# Hammer.net
KiCad netlist of a schematic drawn in Altium Designer
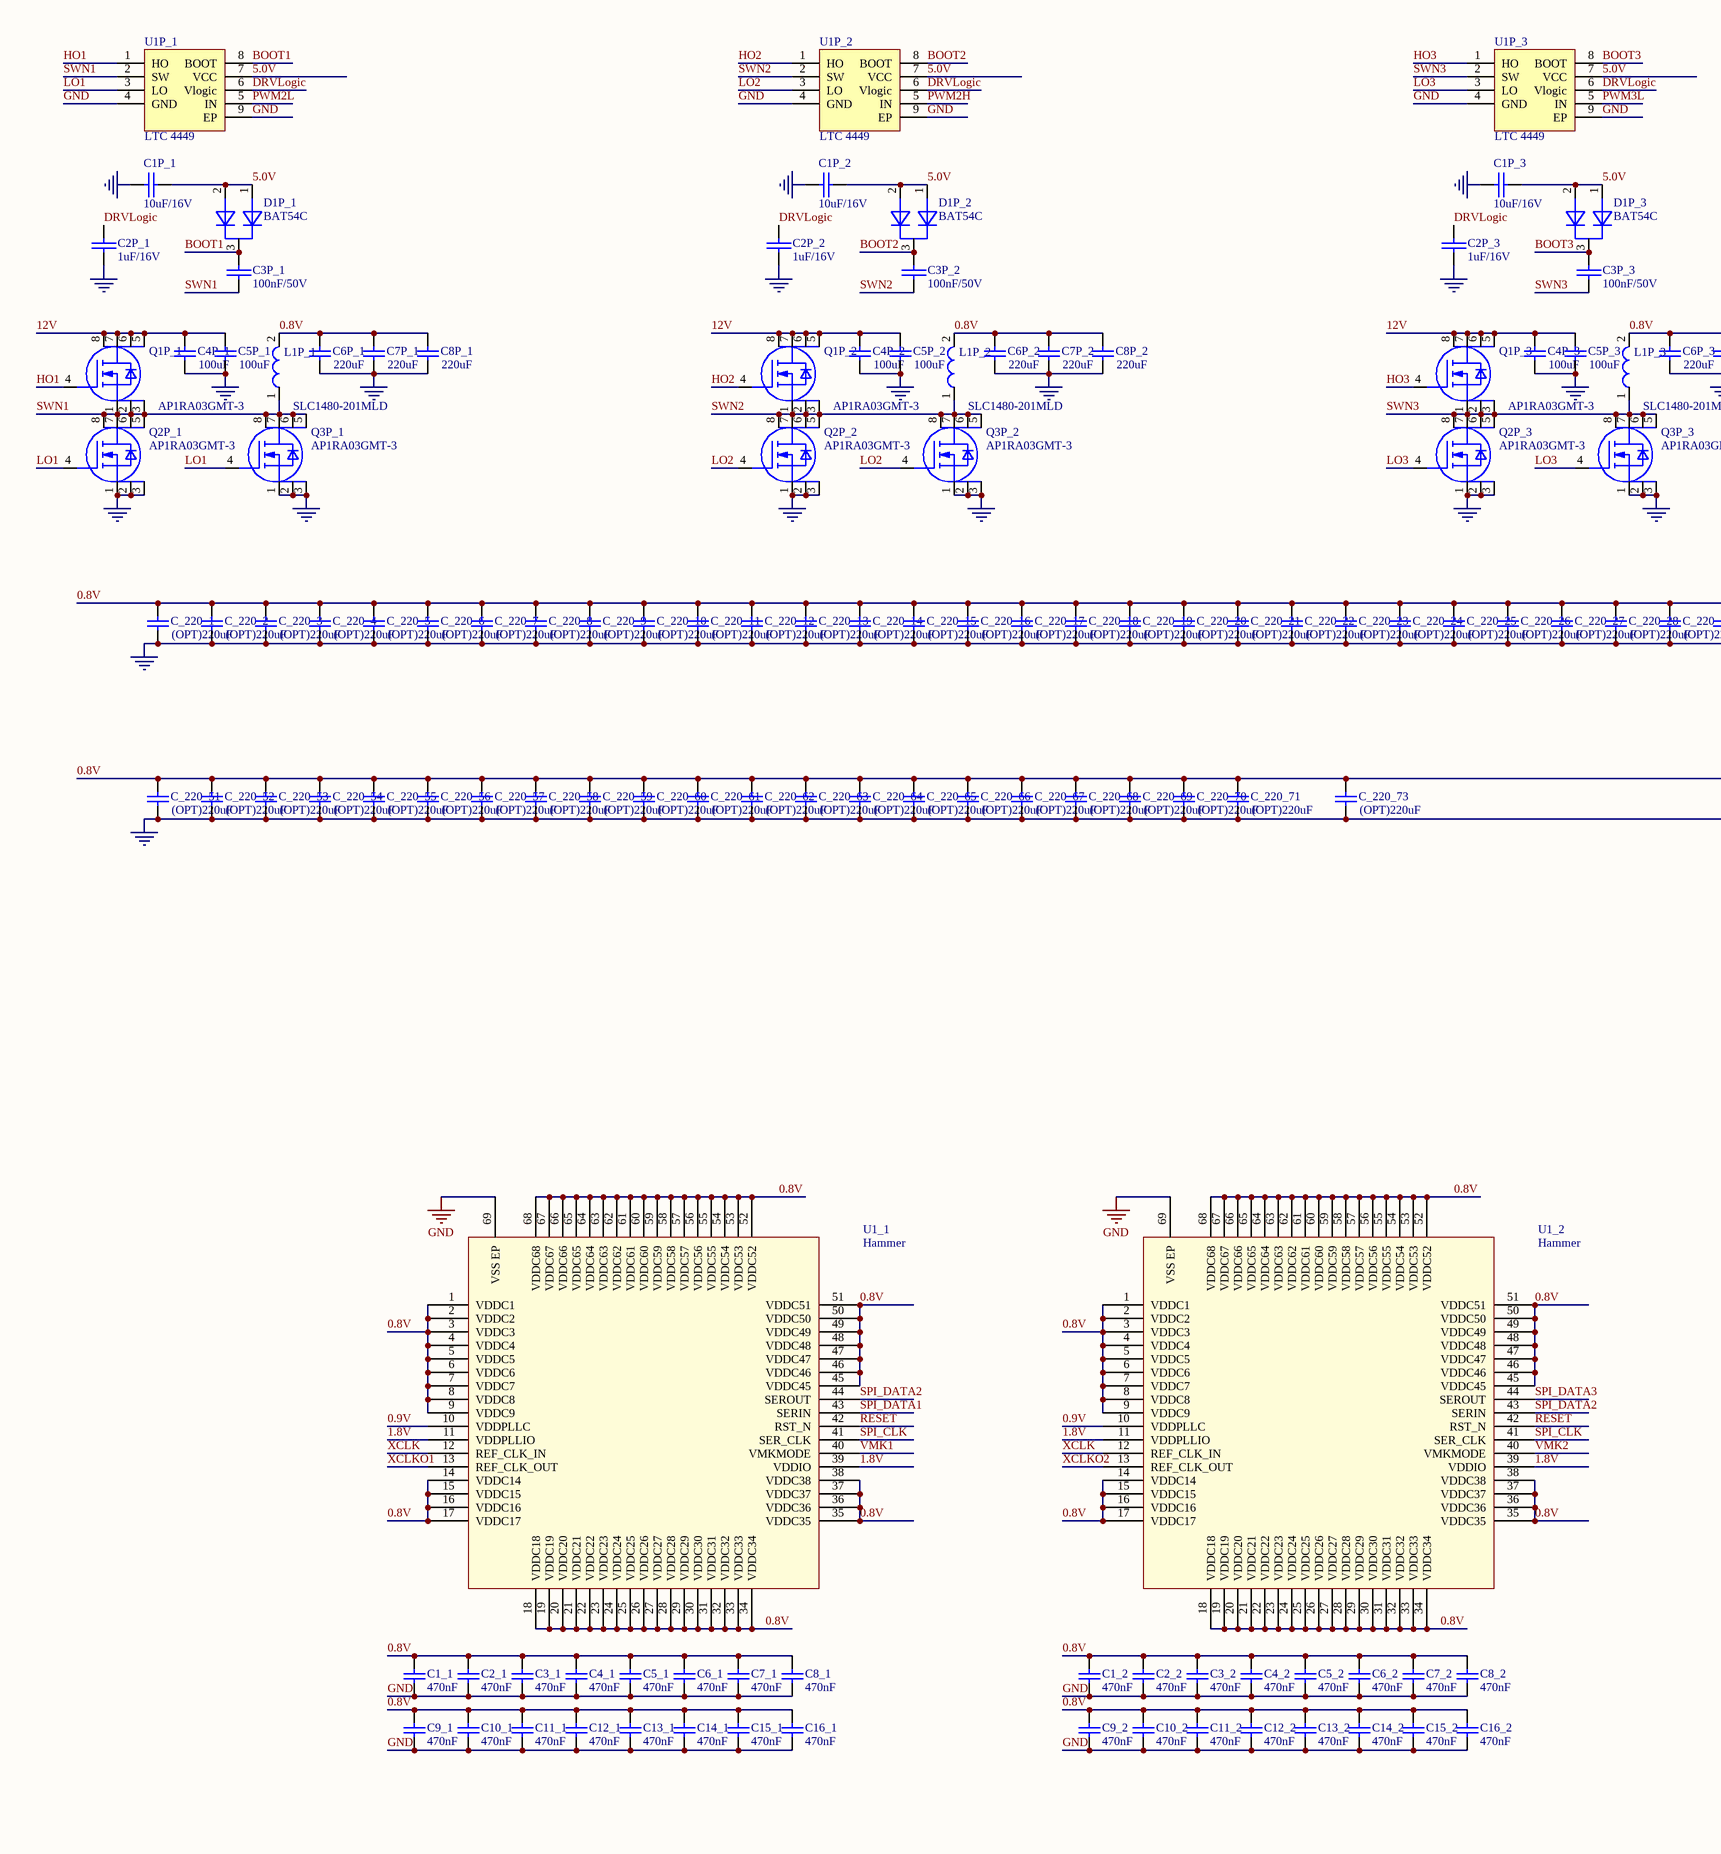
[diagram p0: Hammer.SchDoc, top left]
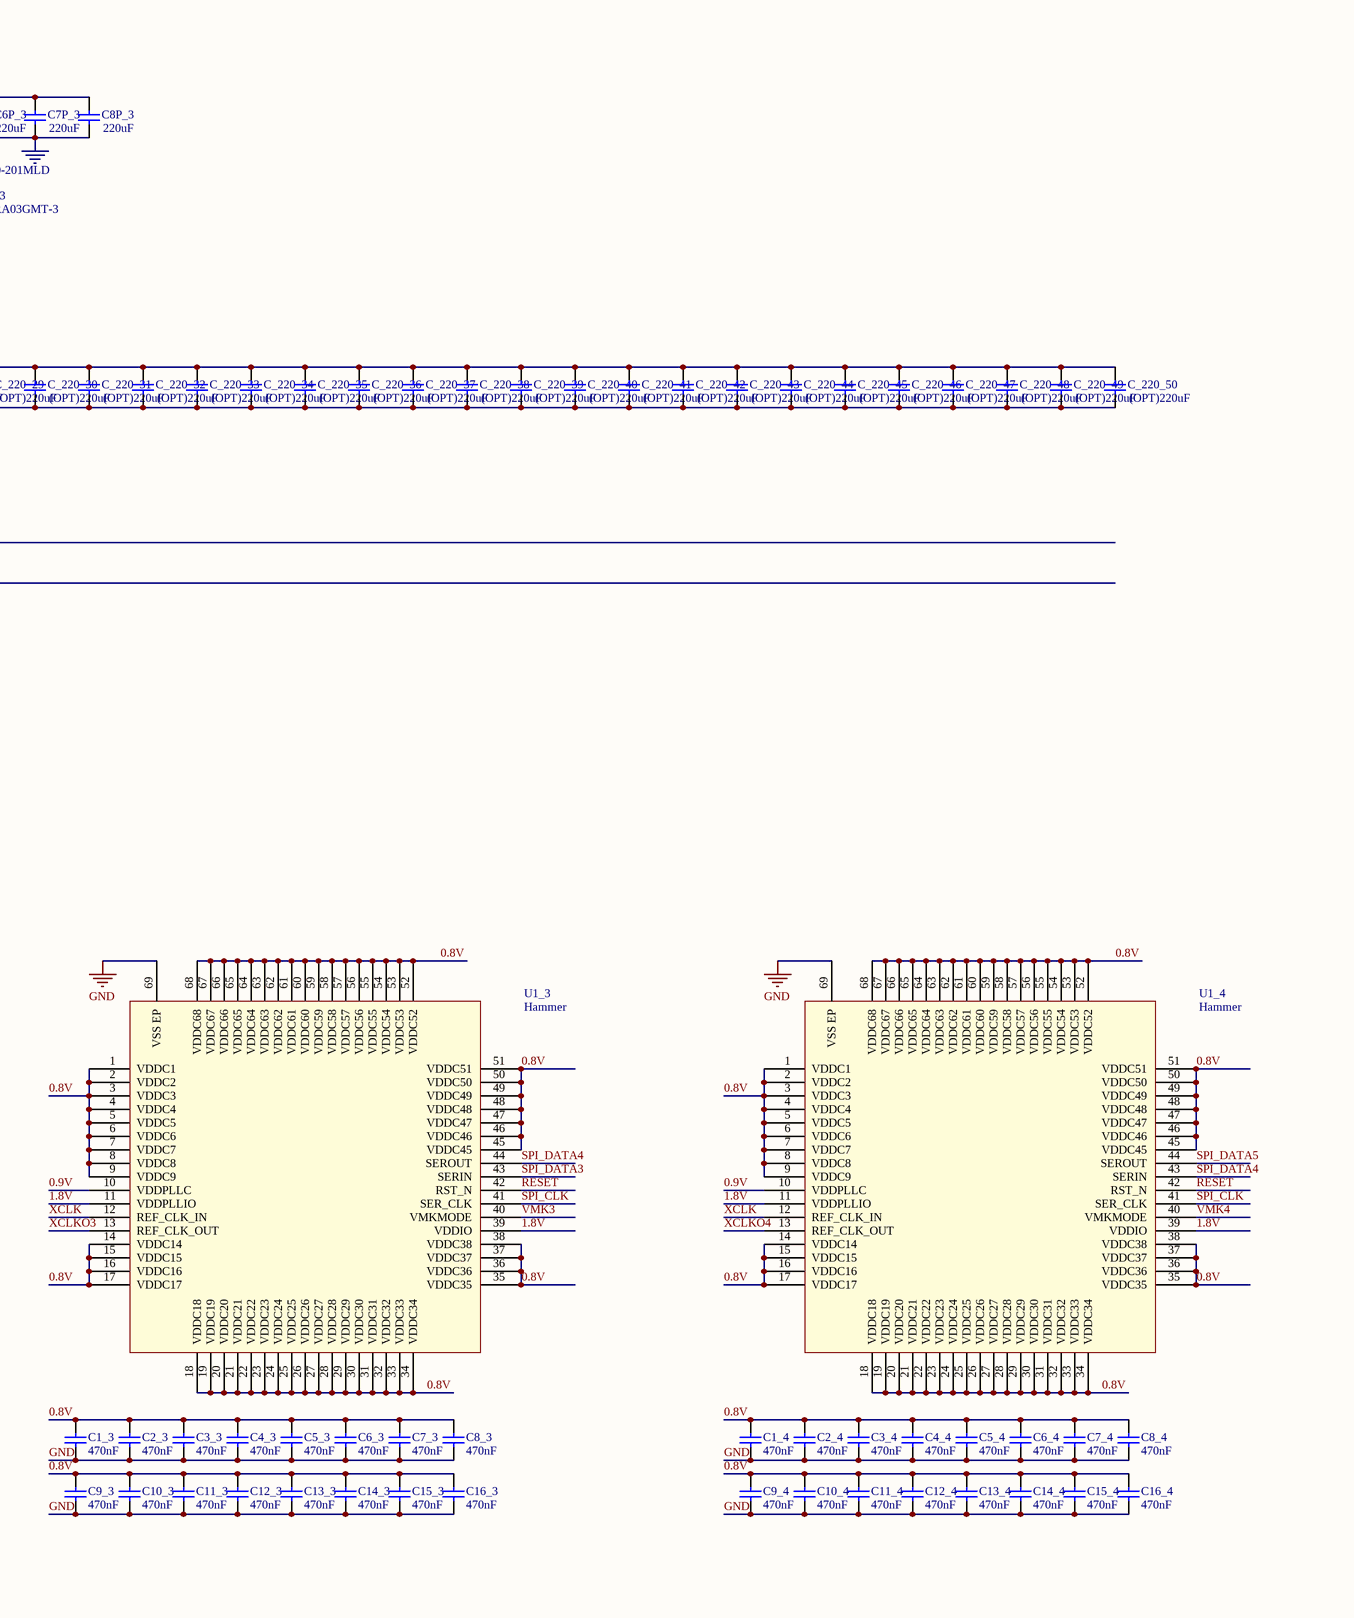
[diagram p1: Hammer.SchDoc, top middle]
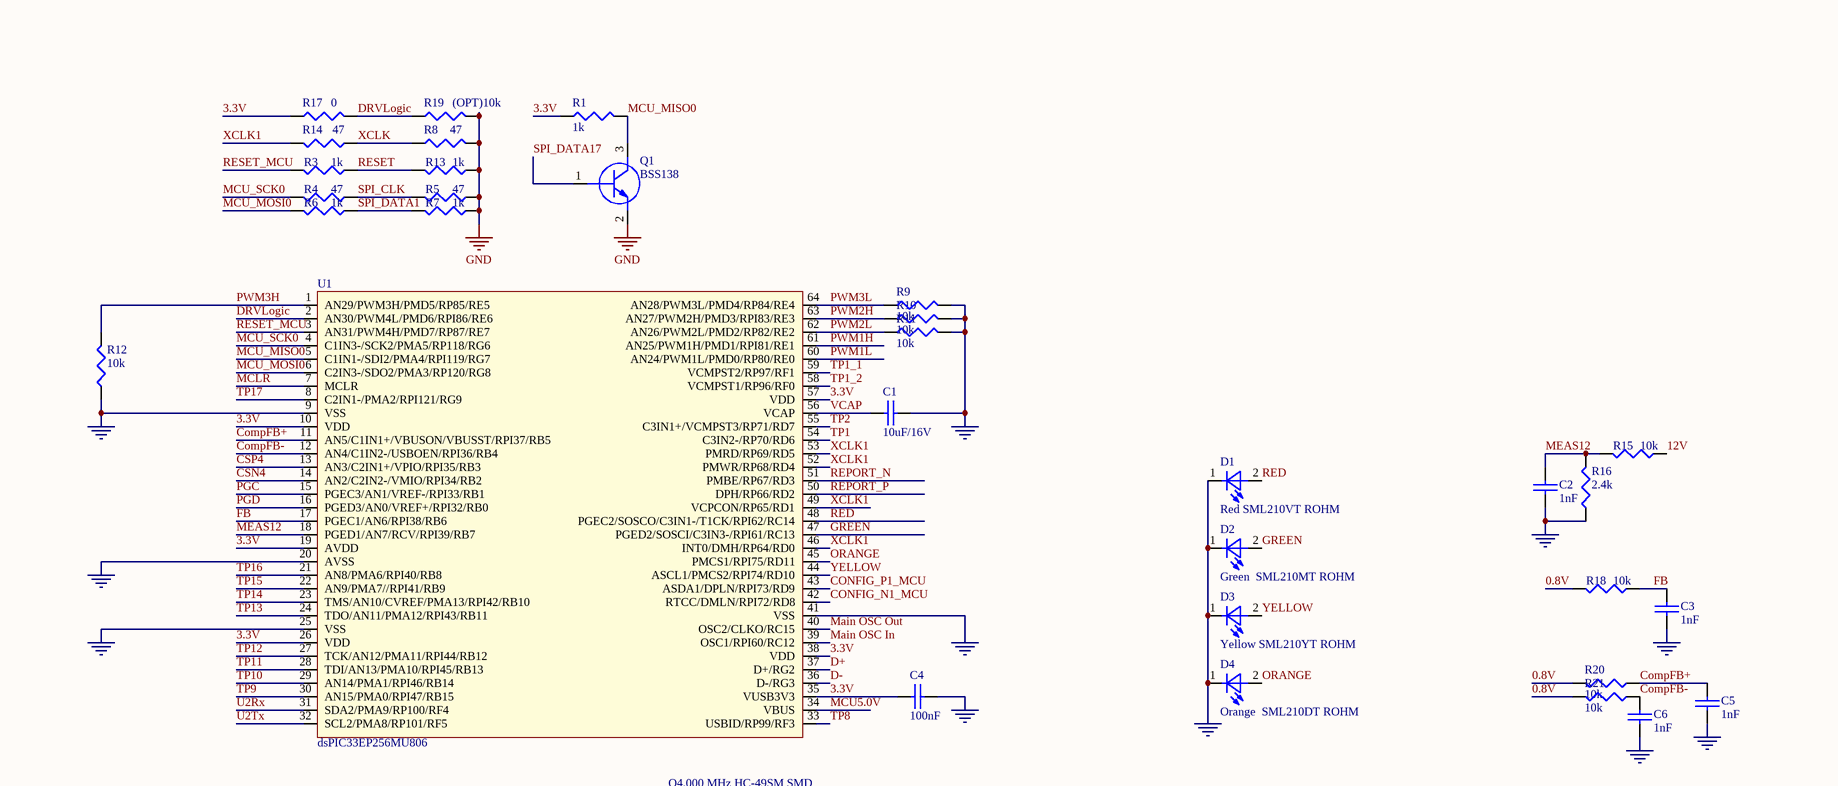
[diagram p2: Hammer.SchDoc, top right]
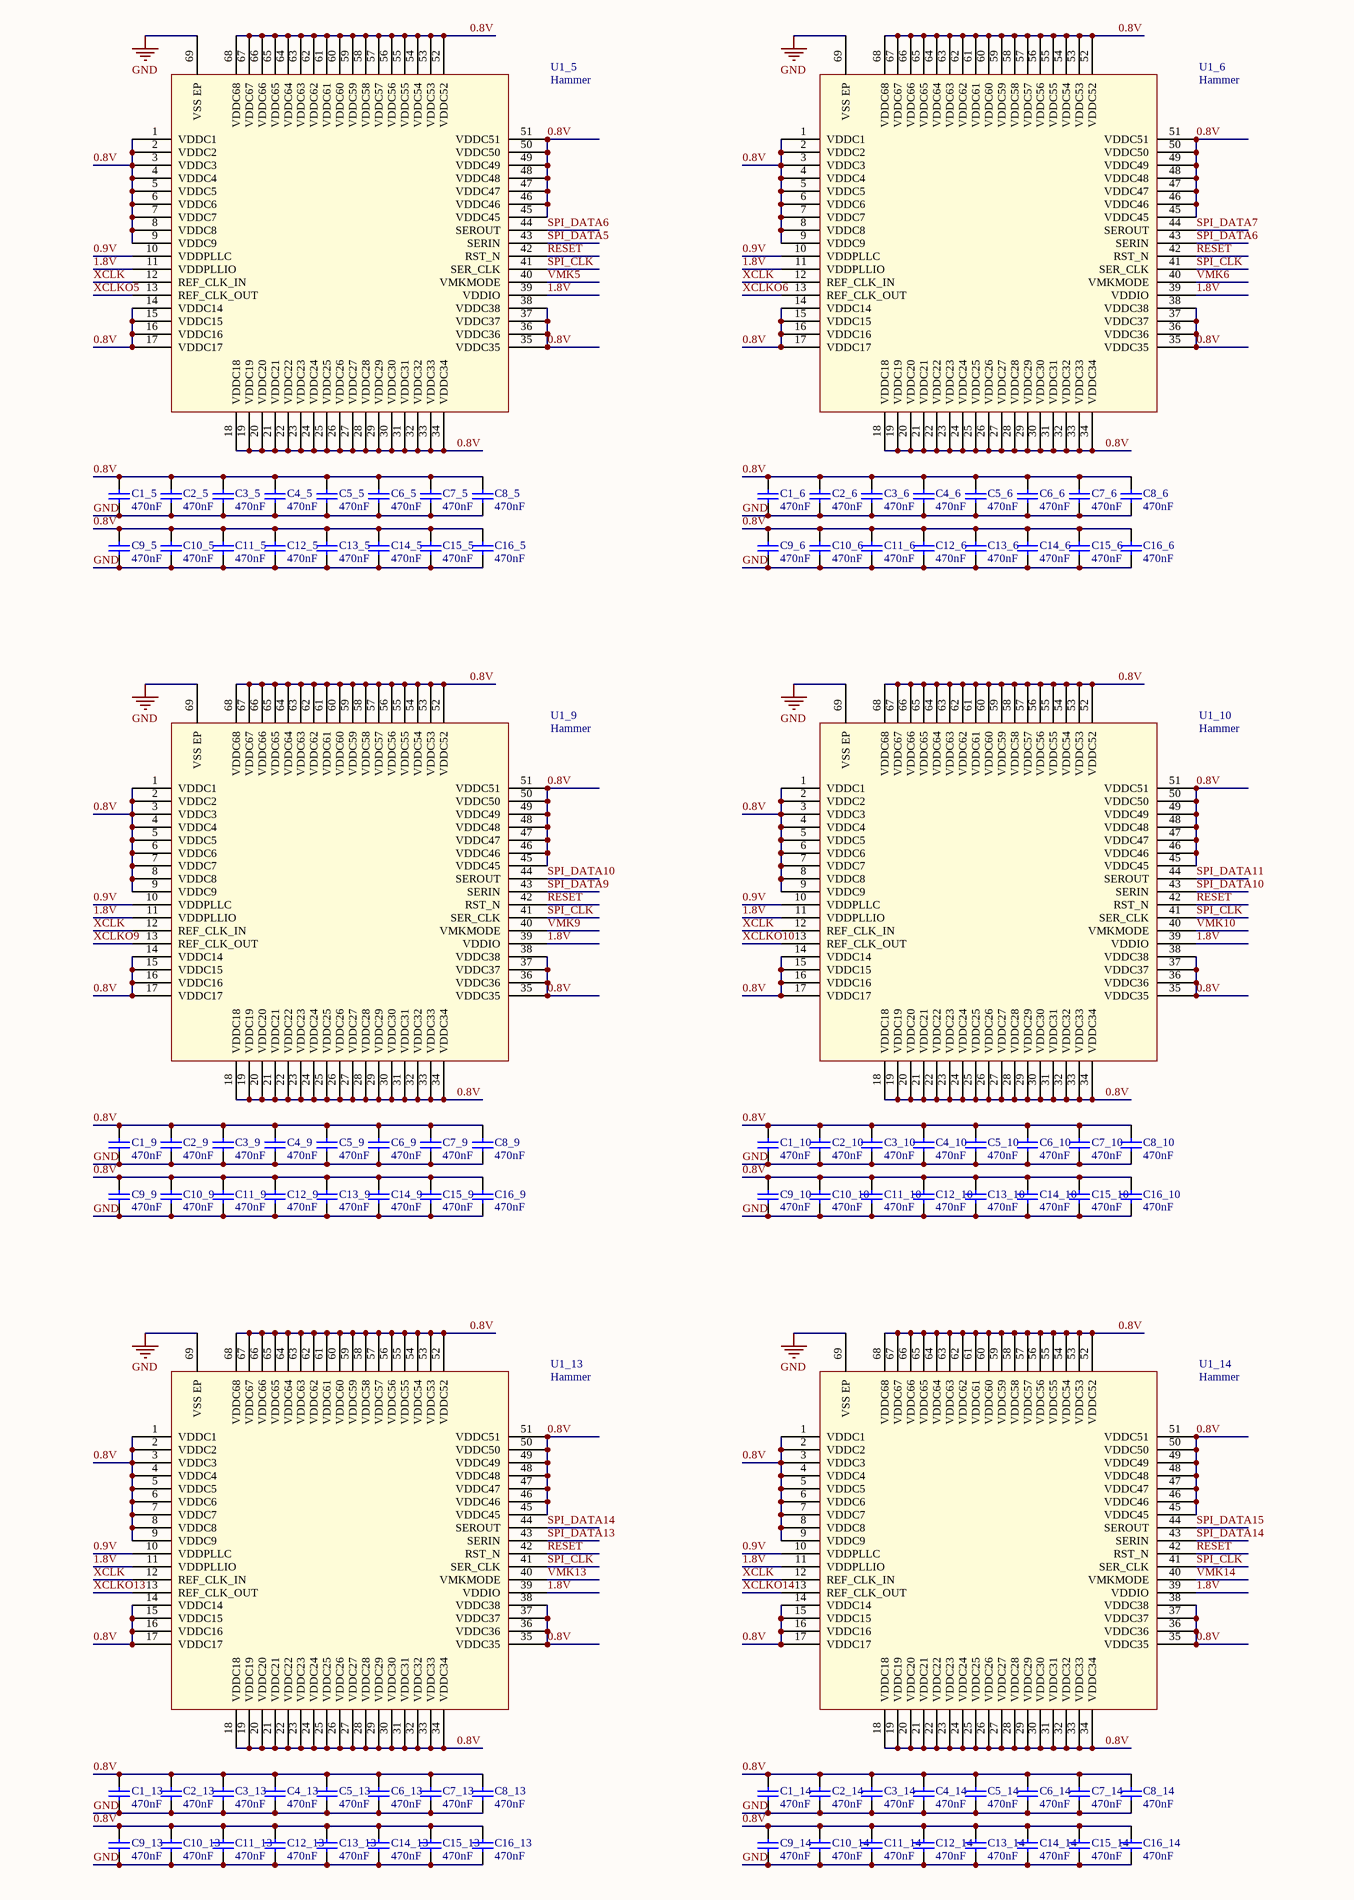
[diagram p3: Hammer.SchDoc, bottom left]
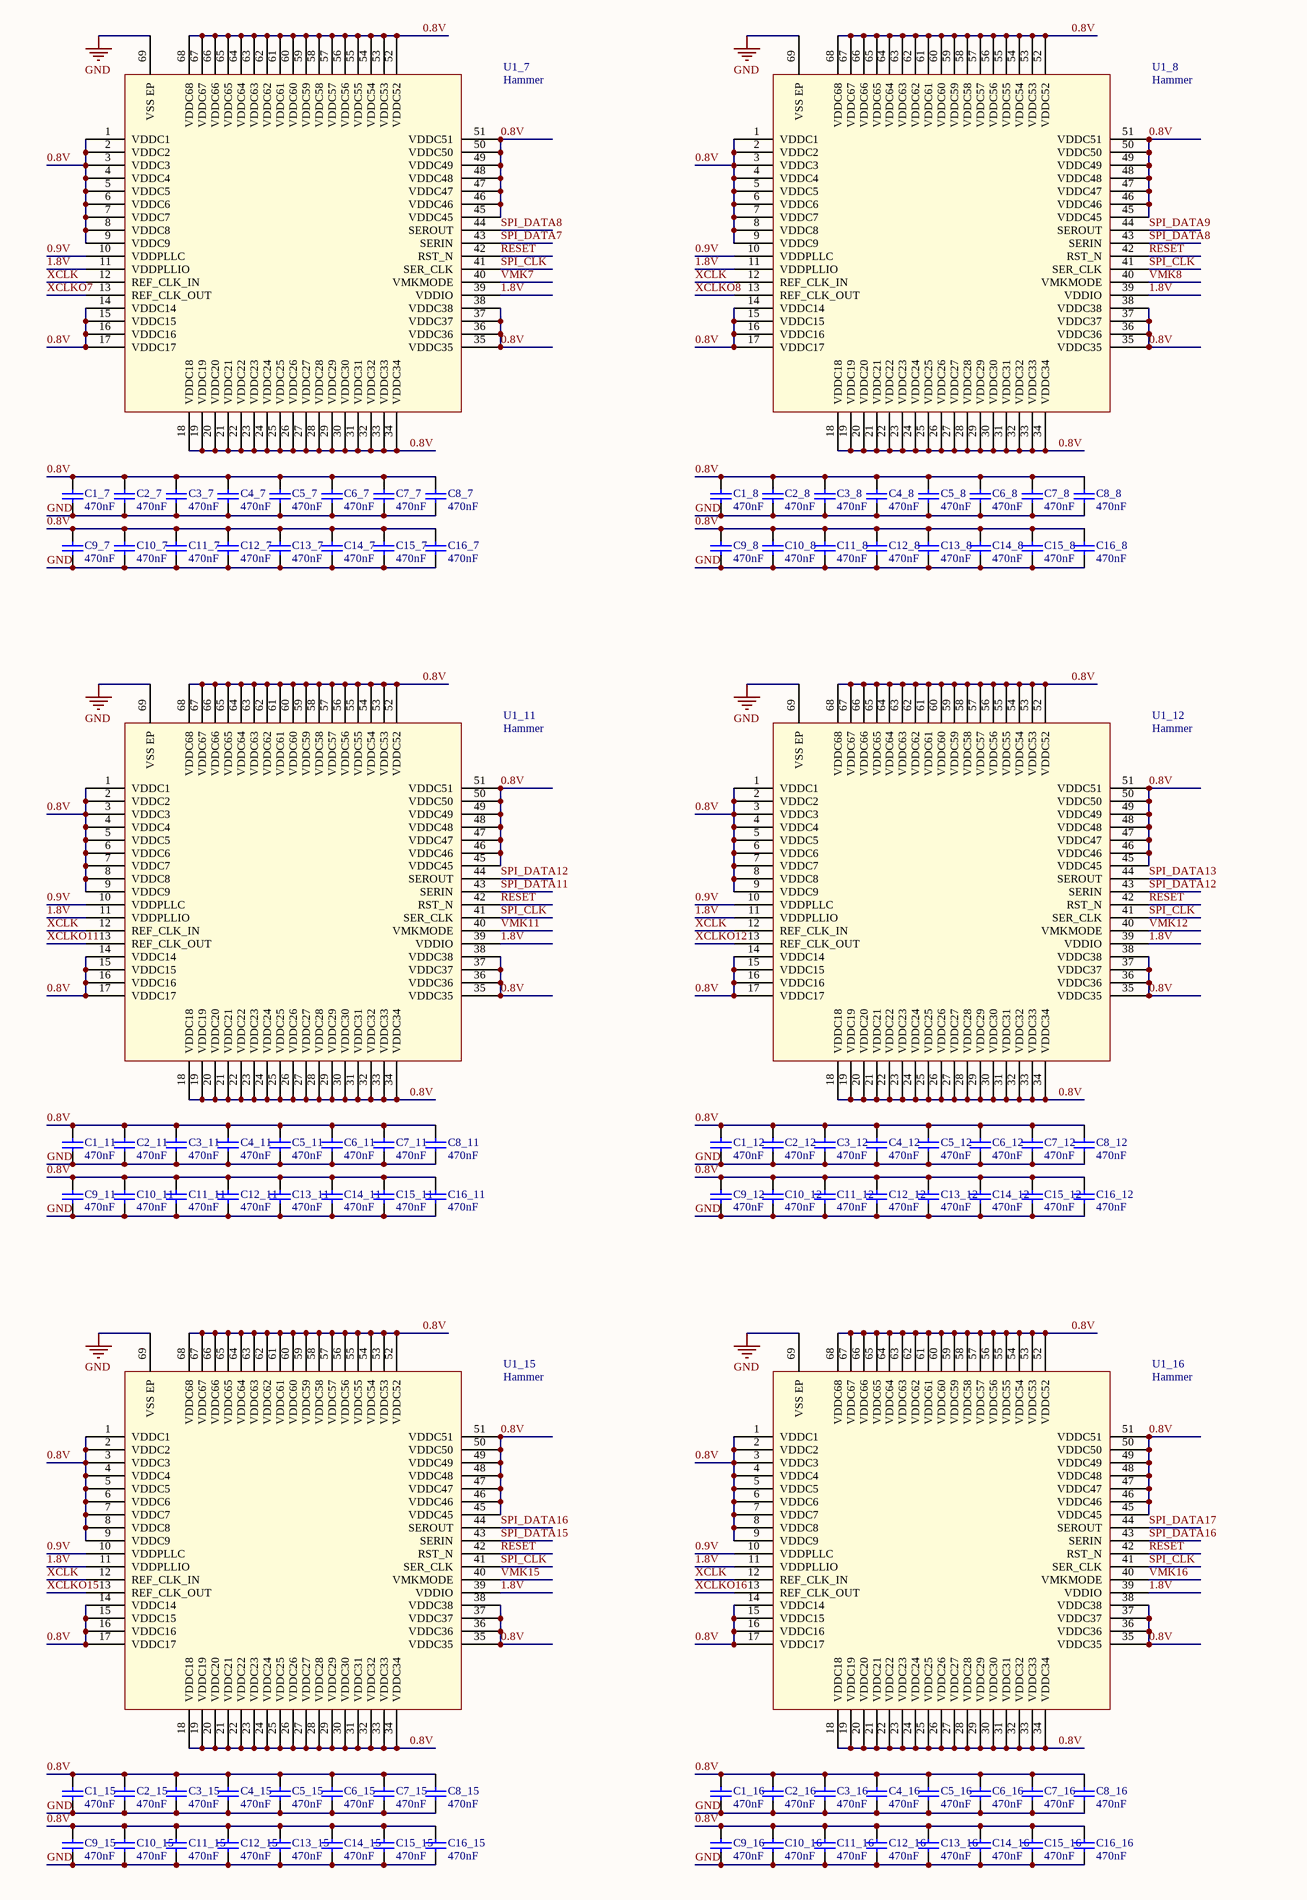
[diagram p4: Hammer.SchDoc, bottom middle]
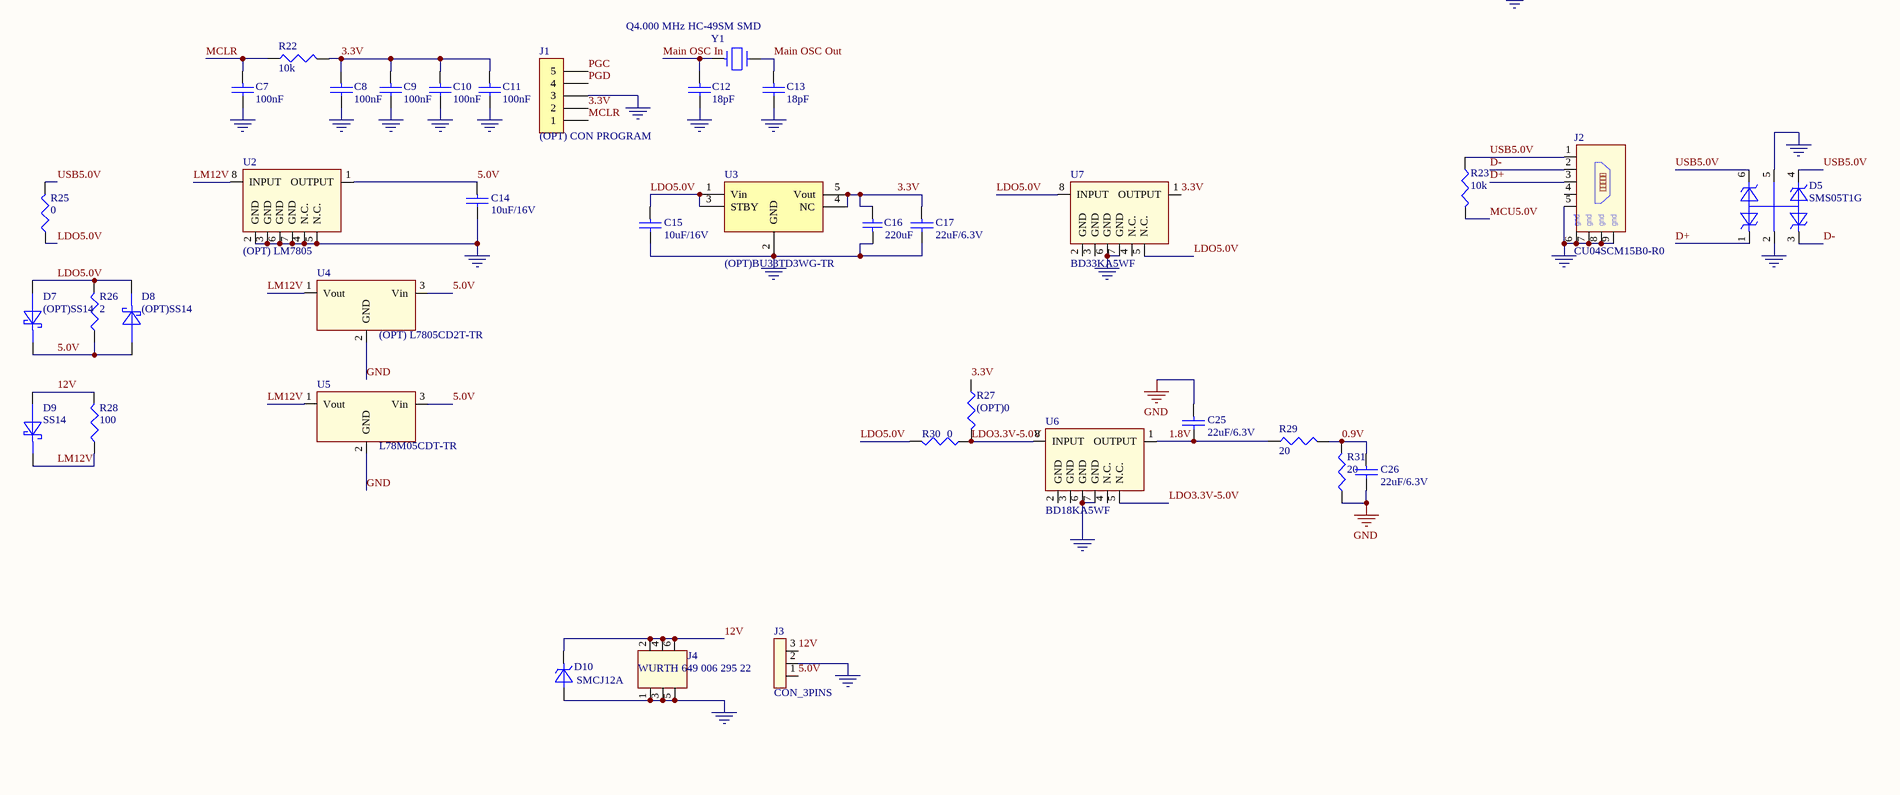
[diagram p5: Hammer.SchDoc, bottom right]

(export (version "E")
  (design (tool "Eeschema 10.0.6"))
  (components
    (comp (ref "C1")
      (value "10uF/16V")
      (footprint "SMD_0805_CAPC2012X145N")
      (description "Capacitor")
      (libsource (lib "*") (part "CAP"))
    )
    (comp (ref "C1P_1")
      (value "10uF/16V")
      (footprint "SMD_0805_CAPC2012X145N")
      (description "Capacitor")
      (libsource (lib "*") (part "CAP"))
    )
    (comp (ref "C1P_2")
      (value "10uF/16V")
      (footprint "SMD_0805_CAPC2012X145N")
      (description "Capacitor")
      (libsource (lib "*") (part "CAP"))
    )
    (comp (ref "C1P_3")
      (value "10uF/16V")
      (footprint "SMD_0805_CAPC2012X145N")
      (description "Capacitor")
      (libsource (lib "*") (part "CAP"))
    )
    (comp (ref "C1_1")
      (value "470nF")
      (footprint "SMD_0603_CAPC1608X80N")
      (description "Capacitor (Semiconductor SIM Model)")
      (fields (field (name "PUBLISHER") "Altium Limited"))
      (libsource (lib "Miscellaneous Devices") (part "Cap Semi"))
    )
    (comp (ref "C1_2")
      (value "470nF")
      (footprint "SMD_0603_CAPC1608X80N")
      (description "Capacitor (Semiconductor SIM Model)")
      (fields (field (name "PUBLISHER") "Altium Limited"))
      (libsource (lib "Miscellaneous Devices") (part "Cap Semi"))
    )
    (comp (ref "C1_3")
      (value "470nF")
      (footprint "SMD_0603_CAPC1608X80N")
      (description "Capacitor (Semiconductor SIM Model)")
      (fields (field (name "PUBLISHER") "Altium Limited"))
      (libsource (lib "Miscellaneous Devices") (part "Cap Semi"))
    )
    (comp (ref "C1_4")
      (value "470nF")
      (footprint "SMD_0603_CAPC1608X80N")
      (description "Capacitor (Semiconductor SIM Model)")
      (fields (field (name "PUBLISHER") "Altium Limited"))
      (libsource (lib "Miscellaneous Devices") (part "Cap Semi"))
    )
    (comp (ref "C1_5")
      (value "470nF")
      (footprint "SMD_0603_CAPC1608X80N")
      (description "Capacitor (Semiconductor SIM Model)")
      (fields (field (name "PUBLISHER") "Altium Limited"))
      (libsource (lib "Miscellaneous Devices") (part "Cap Semi"))
    )
    (comp (ref "C1_6")
      (value "470nF")
      (footprint "SMD_0603_CAPC1608X80N")
      (description "Capacitor (Semiconductor SIM Model)")
      (fields (field (name "PUBLISHER") "Altium Limited"))
      (libsource (lib "Miscellaneous Devices") (part "Cap Semi"))
    )
    (comp (ref "C1_7")
      (value "470nF")
      (footprint "SMD_0603_CAPC1608X80N")
      (description "Capacitor (Semiconductor SIM Model)")
      (fields (field (name "PUBLISHER") "Altium Limited"))
      (libsource (lib "Miscellaneous Devices") (part "Cap Semi"))
    )
    (comp (ref "C1_8")
      (value "470nF")
      (footprint "SMD_0603_CAPC1608X80N")
      (description "Capacitor (Semiconductor SIM Model)")
      (fields (field (name "PUBLISHER") "Altium Limited"))
      (libsource (lib "Miscellaneous Devices") (part "Cap Semi"))
    )
    (comp (ref "C1_9")
      (value "470nF")
      (footprint "SMD_0603_CAPC1608X80N")
      (description "Capacitor (Semiconductor SIM Model)")
      (fields (field (name "PUBLISHER") "Altium Limited"))
      (libsource (lib "Miscellaneous Devices") (part "Cap Semi"))
    )
    (comp (ref "C1_10")
      (value "470nF")
      (footprint "SMD_0603_CAPC1608X80N")
      (description "Capacitor (Semiconductor SIM Model)")
      (fields (field (name "PUBLISHER") "Altium Limited"))
      (libsource (lib "Miscellaneous Devices") (part "Cap Semi"))
    )
    (comp (ref "C1_11")
      (value "470nF")
      (footprint "SMD_0603_CAPC1608X80N")
      (description "Capacitor (Semiconductor SIM Model)")
      (fields (field (name "PUBLISHER") "Altium Limited"))
      (libsource (lib "Miscellaneous Devices") (part "Cap Semi"))
    )
    (comp (ref "C1_12")
      (value "470nF")
      (footprint "SMD_0603_CAPC1608X80N")
      (description "Capacitor (Semiconductor SIM Model)")
      (fields (field (name "PUBLISHER") "Altium Limited"))
      (libsource (lib "Miscellaneous Devices") (part "Cap Semi"))
    )
    (comp (ref "C1_13")
      (value "470nF")
      (footprint "SMD_0603_CAPC1608X80N")
      (description "Capacitor (Semiconductor SIM Model)")
      (fields (field (name "PUBLISHER") "Altium Limited"))
      (libsource (lib "Miscellaneous Devices") (part "Cap Semi"))
    )
    (comp (ref "C1_14")
      (value "470nF")
      (footprint "SMD_0603_CAPC1608X80N")
      (description "Capacitor (Semiconductor SIM Model)")
      (fields (field (name "PUBLISHER") "Altium Limited"))
      (libsource (lib "Miscellaneous Devices") (part "Cap Semi"))
    )
    (comp (ref "C1_15")
      (value "470nF")
      (footprint "SMD_0603_CAPC1608X80N")
      (description "Capacitor (Semiconductor SIM Model)")
      (fields (field (name "PUBLISHER") "Altium Limited"))
      (libsource (lib "Miscellaneous Devices") (part "Cap Semi"))
    )
    (comp (ref "C1_16")
      (value "470nF")
      (footprint "SMD_0603_CAPC1608X80N")
      (description "Capacitor (Semiconductor SIM Model)")
      (fields (field (name "PUBLISHER") "Altium Limited"))
      (libsource (lib "Miscellaneous Devices") (part "Cap Semi"))
    )
    (comp (ref "C2")
      (value "1nF")
      (footprint "SMD_0603_CAPC1608X80N")
      (description "Capacitor")
      (libsource (lib "*") (part "CAP"))
    )
    (comp (ref "C2P_1")
      (value "1uF/16V")
      (footprint "SMD_0805_CAPC2012X145N")
      (description "Capacitor")
      (libsource (lib "*") (part "CAP"))
    )
    (comp (ref "C2P_2")
      (value "1uF/16V")
      (footprint "SMD_0805_CAPC2012X145N")
      (description "Capacitor")
      (libsource (lib "*") (part "CAP"))
    )
    (comp (ref "C2P_3")
      (value "1uF/16V")
      (footprint "SMD_0805_CAPC2012X145N")
      (description "Capacitor")
      (libsource (lib "*") (part "CAP"))
    )
    (comp (ref "C2_1")
      (value "470nF")
      (footprint "SMD_0603_CAPC1608X80N")
      (description "Capacitor (Semiconductor SIM Model)")
      (fields (field (name "PUBLISHER") "Altium Limited"))
      (libsource (lib "Miscellaneous Devices") (part "Cap Semi"))
    )
    (comp (ref "C2_2")
      (value "470nF")
      (footprint "SMD_0603_CAPC1608X80N")
      (description "Capacitor (Semiconductor SIM Model)")
      (fields (field (name "PUBLISHER") "Altium Limited"))
      (libsource (lib "Miscellaneous Devices") (part "Cap Semi"))
    )
    (comp (ref "C2_3")
      (value "470nF")
      (footprint "SMD_0603_CAPC1608X80N")
      (description "Capacitor (Semiconductor SIM Model)")
      (fields (field (name "PUBLISHER") "Altium Limited"))
      (libsource (lib "Miscellaneous Devices") (part "Cap Semi"))
    )
    (comp (ref "C2_4")
      (value "470nF")
      (footprint "SMD_0603_CAPC1608X80N")
      (description "Capacitor (Semiconductor SIM Model)")
      (fields (field (name "PUBLISHER") "Altium Limited"))
      (libsource (lib "Miscellaneous Devices") (part "Cap Semi"))
    )
    (comp (ref "C2_5")
      (value "470nF")
      (footprint "SMD_0603_CAPC1608X80N")
      (description "Capacitor (Semiconductor SIM Model)")
      (fields (field (name "PUBLISHER") "Altium Limited"))
      (libsource (lib "Miscellaneous Devices") (part "Cap Semi"))
    )
    (comp (ref "C2_6")
      (value "470nF")
      (footprint "SMD_0603_CAPC1608X80N")
      (description "Capacitor (Semiconductor SIM Model)")
      (fields (field (name "PUBLISHER") "Altium Limited"))
      (libsource (lib "Miscellaneous Devices") (part "Cap Semi"))
    )
    (comp (ref "C2_7")
      (value "470nF")
      (footprint "SMD_0603_CAPC1608X80N")
      (description "Capacitor (Semiconductor SIM Model)")
      (fields (field (name "PUBLISHER") "Altium Limited"))
      (libsource (lib "Miscellaneous Devices") (part "Cap Semi"))
    )
    (comp (ref "C2_8")
      (value "470nF")
      (footprint "SMD_0603_CAPC1608X80N")
      (description "Capacitor (Semiconductor SIM Model)")
      (fields (field (name "PUBLISHER") "Altium Limited"))
      (libsource (lib "Miscellaneous Devices") (part "Cap Semi"))
    )
    (comp (ref "C2_9")
      (value "470nF")
      (footprint "SMD_0603_CAPC1608X80N")
      (description "Capacitor (Semiconductor SIM Model)")
      (fields (field (name "PUBLISHER") "Altium Limited"))
      (libsource (lib "Miscellaneous Devices") (part "Cap Semi"))
    )
    (comp (ref "C2_10")
      (value "470nF")
      (footprint "SMD_0603_CAPC1608X80N")
      (description "Capacitor (Semiconductor SIM Model)")
      (fields (field (name "PUBLISHER") "Altium Limited"))
      (libsource (lib "Miscellaneous Devices") (part "Cap Semi"))
    )
    (comp (ref "C2_11")
      (value "470nF")
      (footprint "SMD_0603_CAPC1608X80N")
      (description "Capacitor (Semiconductor SIM Model)")
      (fields (field (name "PUBLISHER") "Altium Limited"))
      (libsource (lib "Miscellaneous Devices") (part "Cap Semi"))
    )
    (comp (ref "C2_12")
      (value "470nF")
      (footprint "SMD_0603_CAPC1608X80N")
      (description "Capacitor (Semiconductor SIM Model)")
      (fields (field (name "PUBLISHER") "Altium Limited"))
      (libsource (lib "Miscellaneous Devices") (part "Cap Semi"))
    )
    (comp (ref "C2_13")
      (value "470nF")
      (footprint "SMD_0603_CAPC1608X80N")
      (description "Capacitor (Semiconductor SIM Model)")
      (fields (field (name "PUBLISHER") "Altium Limited"))
      (libsource (lib "Miscellaneous Devices") (part "Cap Semi"))
    )
    (comp (ref "C2_14")
      (value "470nF")
      (footprint "SMD_0603_CAPC1608X80N")
      (description "Capacitor (Semiconductor SIM Model)")
      (fields (field (name "PUBLISHER") "Altium Limited"))
      (libsource (lib "Miscellaneous Devices") (part "Cap Semi"))
    )
    (comp (ref "C2_15")
      (value "470nF")
      (footprint "SMD_0603_CAPC1608X80N")
      (description "Capacitor (Semiconductor SIM Model)")
      (fields (field (name "PUBLISHER") "Altium Limited"))
      (libsource (lib "Miscellaneous Devices") (part "Cap Semi"))
    )
    (comp (ref "C2_16")
      (value "470nF")
      (footprint "SMD_0603_CAPC1608X80N")
      (description "Capacitor (Semiconductor SIM Model)")
      (fields (field (name "PUBLISHER") "Altium Limited"))
      (libsource (lib "Miscellaneous Devices") (part "Cap Semi"))
    )
    (comp (ref "C3")
      (value "1nF")
      (footprint "SMD_0603_CAPC1608X80N")
      (description "Capacitor")
      (libsource (lib "*") (part "CAP"))
    )
    (comp (ref "C3P_1")
      (value "100nF/50V")
      (footprint "SMD_0805_CAPC2012X145N")
      (description "Capacitor")
      (libsource (lib "*") (part "CAP"))
    )
    (comp (ref "C3P_2")
      (value "100nF/50V")
      (footprint "SMD_0805_CAPC2012X145N")
      (description "Capacitor")
      (libsource (lib "*") (part "CAP"))
    )
    (comp (ref "C3P_3")
      (value "100nF/50V")
      (footprint "SMD_0805_CAPC2012X145N")
      (description "Capacitor")
      (libsource (lib "*") (part "CAP"))
    )
    (comp (ref "C3_1")
      (value "470nF")
      (footprint "SMD_0603_CAPC1608X80N")
      (description "Capacitor (Semiconductor SIM Model)")
      (fields (field (name "PUBLISHER") "Altium Limited"))
      (libsource (lib "Miscellaneous Devices") (part "Cap Semi"))
    )
    (comp (ref "C3_2")
      (value "470nF")
      (footprint "SMD_0603_CAPC1608X80N")
      (description "Capacitor (Semiconductor SIM Model)")
      (fields (field (name "PUBLISHER") "Altium Limited"))
      (libsource (lib "Miscellaneous Devices") (part "Cap Semi"))
    )
    (comp (ref "C3_3")
      (value "470nF")
      (footprint "SMD_0603_CAPC1608X80N")
      (description "Capacitor (Semiconductor SIM Model)")
      (fields (field (name "PUBLISHER") "Altium Limited"))
      (libsource (lib "Miscellaneous Devices") (part "Cap Semi"))
    )
    (comp (ref "C3_4")
      (value "470nF")
      (footprint "SMD_0603_CAPC1608X80N")
      (description "Capacitor (Semiconductor SIM Model)")
      (fields (field (name "PUBLISHER") "Altium Limited"))
      (libsource (lib "Miscellaneous Devices") (part "Cap Semi"))
    )
    (comp (ref "C3_5")
      (value "470nF")
      (footprint "SMD_0603_CAPC1608X80N")
      (description "Capacitor (Semiconductor SIM Model)")
      (fields (field (name "PUBLISHER") "Altium Limited"))
      (libsource (lib "Miscellaneous Devices") (part "Cap Semi"))
    )
    (comp (ref "C3_6")
      (value "470nF")
      (footprint "SMD_0603_CAPC1608X80N")
      (description "Capacitor (Semiconductor SIM Model)")
      (fields (field (name "PUBLISHER") "Altium Limited"))
      (libsource (lib "Miscellaneous Devices") (part "Cap Semi"))
    )
    (comp (ref "C3_7")
      (value "470nF")
      (footprint "SMD_0603_CAPC1608X80N")
      (description "Capacitor (Semiconductor SIM Model)")
      (fields (field (name "PUBLISHER") "Altium Limited"))
      (libsource (lib "Miscellaneous Devices") (part "Cap Semi"))
    )
    (comp (ref "C3_8")
      (value "470nF")
      (footprint "SMD_0603_CAPC1608X80N")
      (description "Capacitor (Semiconductor SIM Model)")
      (fields (field (name "PUBLISHER") "Altium Limited"))
      (libsource (lib "Miscellaneous Devices") (part "Cap Semi"))
    )
    (comp (ref "C3_9")
      (value "470nF")
      (footprint "SMD_0603_CAPC1608X80N")
      (description "Capacitor (Semiconductor SIM Model)")
      (fields (field (name "PUBLISHER") "Altium Limited"))
      (libsource (lib "Miscellaneous Devices") (part "Cap Semi"))
    )
    (comp (ref "C3_10")
      (value "470nF")
      (footprint "SMD_0603_CAPC1608X80N")
      (description "Capacitor (Semiconductor SIM Model)")
      (fields (field (name "PUBLISHER") "Altium Limited"))
      (libsource (lib "Miscellaneous Devices") (part "Cap Semi"))
    )
    (comp (ref "C3_11")
      (value "470nF")
      (footprint "SMD_0603_CAPC1608X80N")
      (description "Capacitor (Semiconductor SIM Model)")
      (fields (field (name "PUBLISHER") "Altium Limited"))
      (libsource (lib "Miscellaneous Devices") (part "Cap Semi"))
    )
    (comp (ref "C3_12")
      (value "470nF")
      (footprint "SMD_0603_CAPC1608X80N")
      (description "Capacitor (Semiconductor SIM Model)")
      (fields (field (name "PUBLISHER") "Altium Limited"))
      (libsource (lib "Miscellaneous Devices") (part "Cap Semi"))
    )
    (comp (ref "C3_13")
      (value "470nF")
      (footprint "SMD_0603_CAPC1608X80N")
      (description "Capacitor (Semiconductor SIM Model)")
      (fields (field (name "PUBLISHER") "Altium Limited"))
      (libsource (lib "Miscellaneous Devices") (part "Cap Semi"))
    )
    (comp (ref "C3_14")
      (value "470nF")
      (footprint "SMD_0603_CAPC1608X80N")
      (description "Capacitor (Semiconductor SIM Model)")
      (fields (field (name "PUBLISHER") "Altium Limited"))
      (libsource (lib "Miscellaneous Devices") (part "Cap Semi"))
    )
    (comp (ref "C3_15")
      (value "470nF")
      (footprint "SMD_0603_CAPC1608X80N")
      (description "Capacitor (Semiconductor SIM Model)")
      (fields (field (name "PUBLISHER") "Altium Limited"))
      (libsource (lib "Miscellaneous Devices") (part "Cap Semi"))
    )
    (comp (ref "C3_16")
      (value "470nF")
      (footprint "SMD_0603_CAPC1608X80N")
      (description "Capacitor (Semiconductor SIM Model)")
      (fields (field (name "PUBLISHER") "Altium Limited"))
      (libsource (lib "Miscellaneous Devices") (part "Cap Semi"))
    )
    (comp (ref "C4")
      (value "100nF")
      (footprint "SMD_0603_CAPC1608X80N")
      (description "Capacitor")
      (libsource (lib "*") (part "CAP"))
    )
    (comp (ref "C4P_1")
      (value "100uF")
      (footprint "SMD_1210_CAPC3225X279N")
      (description "CL32A227MQVNNNE 220UF 6.3V 20% X5R 1210")
      (fields (field (name "PUBLISHER") "Altium Limited"))
      (libsource (lib "Miscellaneous Devices") (part "Cap Semi"))
    )
    (comp (ref "C4P_2")
      (value "100uF")
      (footprint "SMD_1210_CAPC3225X279N")
      (description "CL32A227MQVNNNE 220UF 6.3V 20% X5R 1210")
      (fields (field (name "PUBLISHER") "Altium Limited"))
      (libsource (lib "Miscellaneous Devices") (part "Cap Semi"))
    )
    (comp (ref "C4P_3")
      (value "100uF")
      (footprint "SMD_1210_CAPC3225X279N")
      (description "CL32A227MQVNNNE 220UF 6.3V 20% X5R 1210")
      (fields (field (name "PUBLISHER") "Altium Limited"))
      (libsource (lib "Miscellaneous Devices") (part "Cap Semi"))
    )
    (comp (ref "C4_1")
      (value "470nF")
      (footprint "SMD_0603_CAPC1608X80N")
      (description "Capacitor (Semiconductor SIM Model)")
      (fields (field (name "PUBLISHER") "Altium Limited"))
      (libsource (lib "Miscellaneous Devices") (part "Cap Semi"))
    )
    (comp (ref "C4_2")
      (value "470nF")
      (footprint "SMD_0603_CAPC1608X80N")
      (description "Capacitor (Semiconductor SIM Model)")
      (fields (field (name "PUBLISHER") "Altium Limited"))
      (libsource (lib "Miscellaneous Devices") (part "Cap Semi"))
    )
    (comp (ref "C4_3")
      (value "470nF")
      (footprint "SMD_0603_CAPC1608X80N")
      (description "Capacitor (Semiconductor SIM Model)")
      (fields (field (name "PUBLISHER") "Altium Limited"))
      (libsource (lib "Miscellaneous Devices") (part "Cap Semi"))
    )
    (comp (ref "C4_4")
      (value "470nF")
      (footprint "SMD_0603_CAPC1608X80N")
      (description "Capacitor (Semiconductor SIM Model)")
      (fields (field (name "PUBLISHER") "Altium Limited"))
      (libsource (lib "Miscellaneous Devices") (part "Cap Semi"))
    )
    (comp (ref "C4_5")
      (value "470nF")
      (footprint "SMD_0603_CAPC1608X80N")
      (description "Capacitor (Semiconductor SIM Model)")
      (fields (field (name "PUBLISHER") "Altium Limited"))
      (libsource (lib "Miscellaneous Devices") (part "Cap Semi"))
    )
    (comp (ref "C4_6")
      (value "470nF")
      (footprint "SMD_0603_CAPC1608X80N")
      (description "Capacitor (Semiconductor SIM Model)")
      (fields (field (name "PUBLISHER") "Altium Limited"))
      (libsource (lib "Miscellaneous Devices") (part "Cap Semi"))
    )
    (comp (ref "C4_7")
      (value "470nF")
      (footprint "SMD_0603_CAPC1608X80N")
      (description "Capacitor (Semiconductor SIM Model)")
      (fields (field (name "PUBLISHER") "Altium Limited"))
      (libsource (lib "Miscellaneous Devices") (part "Cap Semi"))
    )
    (comp (ref "C4_8")
      (value "470nF")
      (footprint "SMD_0603_CAPC1608X80N")
      (description "Capacitor (Semiconductor SIM Model)")
      (fields (field (name "PUBLISHER") "Altium Limited"))
      (libsource (lib "Miscellaneous Devices") (part "Cap Semi"))
    )
    (comp (ref "C4_9")
      (value "470nF")
      (footprint "SMD_0603_CAPC1608X80N")
      (description "Capacitor (Semiconductor SIM Model)")
      (fields (field (name "PUBLISHER") "Altium Limited"))
      (libsource (lib "Miscellaneous Devices") (part "Cap Semi"))
    )
    (comp (ref "C4_10")
      (value "470nF")
      (footprint "SMD_0603_CAPC1608X80N")
      (description "Capacitor (Semiconductor SIM Model)")
      (fields (field (name "PUBLISHER") "Altium Limited"))
      (libsource (lib "Miscellaneous Devices") (part "Cap Semi"))
    )
    (comp (ref "C4_11")
      (value "470nF")
      (footprint "SMD_0603_CAPC1608X80N")
      (description "Capacitor (Semiconductor SIM Model)")
      (fields (field (name "PUBLISHER") "Altium Limited"))
      (libsource (lib "Miscellaneous Devices") (part "Cap Semi"))
    )
    (comp (ref "C4_12")
      (value "470nF")
      (footprint "SMD_0603_CAPC1608X80N")
      (description "Capacitor (Semiconductor SIM Model)")
      (fields (field (name "PUBLISHER") "Altium Limited"))
      (libsource (lib "Miscellaneous Devices") (part "Cap Semi"))
    )
    (comp (ref "C4_13")
      (value "470nF")
      (footprint "SMD_0603_CAPC1608X80N")
      (description "Capacitor (Semiconductor SIM Model)")
      (fields (field (name "PUBLISHER") "Altium Limited"))
      (libsource (lib "Miscellaneous Devices") (part "Cap Semi"))
    )
    (comp (ref "C4_14")
      (value "470nF")
      (footprint "SMD_0603_CAPC1608X80N")
      (description "Capacitor (Semiconductor SIM Model)")
      (fields (field (name "PUBLISHER") "Altium Limited"))
      (libsource (lib "Miscellaneous Devices") (part "Cap Semi"))
    )
    (comp (ref "C4_15")
      (value "470nF")
      (footprint "SMD_0603_CAPC1608X80N")
      (description "Capacitor (Semiconductor SIM Model)")
      (fields (field (name "PUBLISHER") "Altium Limited"))
      (libsource (lib "Miscellaneous Devices") (part "Cap Semi"))
    )
    (comp (ref "C4_16")
      (value "470nF")
      (footprint "SMD_0603_CAPC1608X80N")
      (description "Capacitor (Semiconductor SIM Model)")
      (fields (field (name "PUBLISHER") "Altium Limited"))
      (libsource (lib "Miscellaneous Devices") (part "Cap Semi"))
    )
    (comp (ref "C5")
      (value "1nF")
      (footprint "SMD_0603_CAPC1608X80N")
      (description "Capacitor")
      (libsource (lib "*") (part "CAP"))
    )
    (comp (ref "C5P_1")
      (value "100uF")
      (footprint "SMD_1210_CAPC3225X279N")
      (description "CL32A227MQVNNNE 220UF 6.3V 20% X5R 1210")
      (fields (field (name "PUBLISHER") "Altium Limited"))
      (libsource (lib "Miscellaneous Devices") (part "Cap Semi"))
    )
    (comp (ref "C5P_2")
      (value "100uF")
      (footprint "SMD_1210_CAPC3225X279N")
      (description "CL32A227MQVNNNE 220UF 6.3V 20% X5R 1210")
      (fields (field (name "PUBLISHER") "Altium Limited"))
      (libsource (lib "Miscellaneous Devices") (part "Cap Semi"))
    )
    (comp (ref "C5P_3")
      (value "100uF")
      (footprint "SMD_1210_CAPC3225X279N")
      (description "CL32A227MQVNNNE 220UF 6.3V 20% X5R 1210")
      (fields (field (name "PUBLISHER") "Altium Limited"))
      (libsource (lib "Miscellaneous Devices") (part "Cap Semi"))
    )
    (comp (ref "C5_1")
      (value "470nF")
      (footprint "SMD_0603_CAPC1608X80N")
      (description "Capacitor (Semiconductor SIM Model)")
      (fields (field (name "PUBLISHER") "Altium Limited"))
      (libsource (lib "Miscellaneous Devices") (part "Cap Semi"))
    )
    (comp (ref "C5_2")
      (value "470nF")
      (footprint "SMD_0603_CAPC1608X80N")
      (description "Capacitor (Semiconductor SIM Model)")
      (fields (field (name "PUBLISHER") "Altium Limited"))
      (libsource (lib "Miscellaneous Devices") (part "Cap Semi"))
    )
    (comp (ref "C5_3")
      (value "470nF")
      (footprint "SMD_0603_CAPC1608X80N")
      (description "Capacitor (Semiconductor SIM Model)")
      (fields (field (name "PUBLISHER") "Altium Limited"))
      (libsource (lib "Miscellaneous Devices") (part "Cap Semi"))
    )
    (comp (ref "C5_4")
      (value "470nF")
      (footprint "SMD_0603_CAPC1608X80N")
      (description "Capacitor (Semiconductor SIM Model)")
      (fields (field (name "PUBLISHER") "Altium Limited"))
      (libsource (lib "Miscellaneous Devices") (part "Cap Semi"))
    )
    (comp (ref "C5_5")
      (value "470nF")
      (footprint "SMD_0603_CAPC1608X80N")
      (description "Capacitor (Semiconductor SIM Model)")
      (fields (field (name "PUBLISHER") "Altium Limited"))
      (libsource (lib "Miscellaneous Devices") (part "Cap Semi"))
    )
    (comp (ref "C5_6")
      (value "470nF")
      (footprint "SMD_0603_CAPC1608X80N")
      (description "Capacitor (Semiconductor SIM Model)")
      (fields (field (name "PUBLISHER") "Altium Limited"))
      (libsource (lib "Miscellaneous Devices") (part "Cap Semi"))
    )
    (comp (ref "C5_7")
      (value "470nF")
      (footprint "SMD_0603_CAPC1608X80N")
      (description "Capacitor (Semiconductor SIM Model)")
      (fields (field (name "PUBLISHER") "Altium Limited"))
      (libsource (lib "Miscellaneous Devices") (part "Cap Semi"))
    )
    (comp (ref "C5_8")
      (value "470nF")
      (footprint "SMD_0603_CAPC1608X80N")
      (description "Capacitor (Semiconductor SIM Model)")
      (fields (field (name "PUBLISHER") "Altium Limited"))
      (libsource (lib "Miscellaneous Devices") (part "Cap Semi"))
    )
    (comp (ref "C5_9")
      (value "470nF")
      (footprint "SMD_0603_CAPC1608X80N")
      (description "Capacitor (Semiconductor SIM Model)")
      (fields (field (name "PUBLISHER") "Altium Limited"))
      (libsource (lib "Miscellaneous Devices") (part "Cap Semi"))
    )
    (comp (ref "C5_10")
      (value "470nF")
      (footprint "SMD_0603_CAPC1608X80N")
      (description "Capacitor (Semiconductor SIM Model)")
      (fields (field (name "PUBLISHER") "Altium Limited"))
      (libsource (lib "Miscellaneous Devices") (part "Cap Semi"))
    )
    (comp (ref "C5_11")
      (value "470nF")
      (footprint "SMD_0603_CAPC1608X80N")
      (description "Capacitor (Semiconductor SIM Model)")
      (fields (field (name "PUBLISHER") "Altium Limited"))
      (libsource (lib "Miscellaneous Devices") (part "Cap Semi"))
    )
    (comp (ref "C5_12")
      (value "470nF")
      (footprint "SMD_0603_CAPC1608X80N")
      (description "Capacitor (Semiconductor SIM Model)")
      (fields (field (name "PUBLISHER") "Altium Limited"))
      (libsource (lib "Miscellaneous Devices") (part "Cap Semi"))
    )
    (comp (ref "C5_13")
      (value "470nF")
      (footprint "SMD_0603_CAPC1608X80N")
      (description "Capacitor (Semiconductor SIM Model)")
      (fields (field (name "PUBLISHER") "Altium Limited"))
      (libsource (lib "Miscellaneous Devices") (part "Cap Semi"))
    )
    (comp (ref "C5_14")
      (value "470nF")
      (footprint "SMD_0603_CAPC1608X80N")
      (description "Capacitor (Semiconductor SIM Model)")
      (fields (field (name "PUBLISHER") "Altium Limited"))
      (libsource (lib "Miscellaneous Devices") (part "Cap Semi"))
    )
    (comp (ref "C5_15")
      (value "470nF")
      (footprint "SMD_0603_CAPC1608X80N")
      (description "Capacitor (Semiconductor SIM Model)")
      (fields (field (name "PUBLISHER") "Altium Limited"))
      (libsource (lib "Miscellaneous Devices") (part "Cap Semi"))
    )
    (comp (ref "C5_16")
      (value "470nF")
      (footprint "SMD_0603_CAPC1608X80N")
      (description "Capacitor (Semiconductor SIM Model)")
      (fields (field (name "PUBLISHER") "Altium Limited"))
      (libsource (lib "Miscellaneous Devices") (part "Cap Semi"))
    )
    (comp (ref "C6")
      (value "1nF")
      (footprint "SMD_0603_CAPC1608X80N")
      (description "Capacitor")
      (libsource (lib "*") (part "CAP"))
    )
    (comp (ref "C6P_1")
      (value "220uF")
      (footprint "SMD_1210_CAPC3225X279N")
      (description "CL32A227MQVNNNE 220UF 6.3V 20% X5R 1210")
      (fields (field (name "PUBLISHER") "Altium Limited"))
      (libsource (lib "Miscellaneous Devices") (part "Cap Semi"))
    )
    (comp (ref "C6P_2")
      (value "220uF")
      (footprint "SMD_1210_CAPC3225X279N")
      (description "CL32A227MQVNNNE 220UF 6.3V 20% X5R 1210")
      (fields (field (name "PUBLISHER") "Altium Limited"))
      (libsource (lib "Miscellaneous Devices") (part "Cap Semi"))
    )
    (comp (ref "C6P_3")
      (value "220uF")
      (footprint "SMD_1210_CAPC3225X279N")
      (description "CL32A227MQVNNNE 220UF 6.3V 20% X5R 1210")
      (fields (field (name "PUBLISHER") "Altium Limited"))
      (libsource (lib "Miscellaneous Devices") (part "Cap Semi"))
    )
    (comp (ref "C6_1")
      (value "470nF")
      (footprint "SMD_0603_CAPC1608X80N")
      (description "Capacitor (Semiconductor SIM Model)")
      (fields (field (name "PUBLISHER") "Altium Limited"))
      (libsource (lib "Miscellaneous Devices") (part "Cap Semi"))
    )
    (comp (ref "C6_2")
      (value "470nF")
      (footprint "SMD_0603_CAPC1608X80N")
      (description "Capacitor (Semiconductor SIM Model)")
      (fields (field (name "PUBLISHER") "Altium Limited"))
      (libsource (lib "Miscellaneous Devices") (part "Cap Semi"))
    )
    (comp (ref "C6_3")
      (value "470nF")
      (footprint "SMD_0603_CAPC1608X80N")
      (description "Capacitor (Semiconductor SIM Model)")
      (fields (field (name "PUBLISHER") "Altium Limited"))
      (libsource (lib "Miscellaneous Devices") (part "Cap Semi"))
    )
    (comp (ref "C6_4")
      (value "470nF")
      (footprint "SMD_0603_CAPC1608X80N")
      (description "Capacitor (Semiconductor SIM Model)")
      (fields (field (name "PUBLISHER") "Altium Limited"))
      (libsource (lib "Miscellaneous Devices") (part "Cap Semi"))
    )
    (comp (ref "C6_5")
      (value "470nF")
      (footprint "SMD_0603_CAPC1608X80N")
      (description "Capacitor (Semiconductor SIM Model)")
      (fields (field (name "PUBLISHER") "Altium Limited"))
      (libsource (lib "Miscellaneous Devices") (part "Cap Semi"))
    )
    (comp (ref "C6_6")
      (value "470nF")
      (footprint "SMD_0603_CAPC1608X80N")
      (description "Capacitor (Semiconductor SIM Model)")
      (fields (field (name "PUBLISHER") "Altium Limited"))
      (libsource (lib "Miscellaneous Devices") (part "Cap Semi"))
    )
    (comp (ref "C6_7")
      (value "470nF")
      (footprint "SMD_0603_CAPC1608X80N")
      (description "Capacitor (Semiconductor SIM Model)")
      (fields (field (name "PUBLISHER") "Altium Limited"))
      (libsource (lib "Miscellaneous Devices") (part "Cap Semi"))
    )
    (comp (ref "C6_8")
      (value "470nF")
      (footprint "SMD_0603_CAPC1608X80N")
      (description "Capacitor (Semiconductor SIM Model)")
      (fields (field (name "PUBLISHER") "Altium Limited"))
      (libsource (lib "Miscellaneous Devices") (part "Cap Semi"))
    )
    (comp (ref "C6_9")
      (value "470nF")
      (footprint "SMD_0603_CAPC1608X80N")
      (description "Capacitor (Semiconductor SIM Model)")
      (fields (field (name "PUBLISHER") "Altium Limited"))
      (libsource (lib "Miscellaneous Devices") (part "Cap Semi"))
    )
    (comp (ref "C6_10")
      (value "470nF")
      (footprint "SMD_0603_CAPC1608X80N")
      (description "Capacitor (Semiconductor SIM Model)")
      (fields (field (name "PUBLISHER") "Altium Limited"))
      (libsource (lib "Miscellaneous Devices") (part "Cap Semi"))
    )
    (comp (ref "C6_11")
      (value "470nF")
      (footprint "SMD_0603_CAPC1608X80N")
      (description "Capacitor (Semiconductor SIM Model)")
      (fields (field (name "PUBLISHER") "Altium Limited"))
      (libsource (lib "Miscellaneous Devices") (part "Cap Semi"))
    )
    (comp (ref "C6_12")
      (value "470nF")
      (footprint "SMD_0603_CAPC1608X80N")
      (description "Capacitor (Semiconductor SIM Model)")
      (fields (field (name "PUBLISHER") "Altium Limited"))
      (libsource (lib "Miscellaneous Devices") (part "Cap Semi"))
    )
    (comp (ref "C6_13")
      (value "470nF")
      (footprint "SMD_0603_CAPC1608X80N")
      (description "Capacitor (Semiconductor SIM Model)")
      (fields (field (name "PUBLISHER") "Altium Limited"))
      (libsource (lib "Miscellaneous Devices") (part "Cap Semi"))
    )
    (comp (ref "C6_14")
      (value "470nF")
      (footprint "SMD_0603_CAPC1608X80N")
      (description "Capacitor (Semiconductor SIM Model)")
      (fields (field (name "PUBLISHER") "Altium Limited"))
      (libsource (lib "Miscellaneous Devices") (part "Cap Semi"))
    )
    (comp (ref "C6_15")
      (value "470nF")
      (footprint "SMD_0603_CAPC1608X80N")
      (description "Capacitor (Semiconductor SIM Model)")
      (fields (field (name "PUBLISHER") "Altium Limited"))
      (libsource (lib "Miscellaneous Devices") (part "Cap Semi"))
    )
    (comp (ref "C6_16")
      (value "470nF")
      (footprint "SMD_0603_CAPC1608X80N")
      (description "Capacitor (Semiconductor SIM Model)")
      (fields (field (name "PUBLISHER") "Altium Limited"))
      (libsource (lib "Miscellaneous Devices") (part "Cap Semi"))
    )
    (comp (ref "C7")
      (value "100nF")
      (footprint "SMD_0603_CAPC1608X80N")
      (description "Capacitor")
      (libsource (lib "*") (part "CAP"))
    )
    (comp (ref "C7P_1")
      (value "220uF")
      (footprint "SMD_1210_CAPC3225X279N")
      (description "CL32A227MQVNNNE 220UF 6.3V 20% X5R 1210")
      (fields (field (name "PUBLISHER") "Altium Limited"))
      (libsource (lib "Miscellaneous Devices") (part "Cap Semi"))
    )
    (comp (ref "C7P_2")
      (value "220uF")
      (footprint "SMD_1210_CAPC3225X279N")
      (description "CL32A227MQVNNNE 220UF 6.3V 20% X5R 1210")
      (fields (field (name "PUBLISHER") "Altium Limited"))
      (libsource (lib "Miscellaneous Devices") (part "Cap Semi"))
    )
    (comp (ref "C7P_3")
      (value "220uF")
      (footprint "SMD_1210_CAPC3225X279N")
      (description "CL32A227MQVNNNE 220UF 6.3V 20% X5R 1210")
      (fields (field (name "PUBLISHER") "Altium Limited"))
      (libsource (lib "Miscellaneous Devices") (part "Cap Semi"))
    )
    (comp (ref "C7_1")
      (value "470nF")
      (footprint "SMD_0603_CAPC1608X80N")
      (description "Capacitor (Semiconductor SIM Model)")
      (fields (field (name "PUBLISHER") "Altium Limited"))
      (libsource (lib "Miscellaneous Devices") (part "Cap Semi"))
    )
    (comp (ref "C7_2")
      (value "470nF")
      (footprint "SMD_0603_CAPC1608X80N")
      (description "Capacitor (Semiconductor SIM Model)")
      (fields (field (name "PUBLISHER") "Altium Limited"))
      (libsource (lib "Miscellaneous Devices") (part "Cap Semi"))
    )
    (comp (ref "C7_3")
      (value "470nF")
      (footprint "SMD_0603_CAPC1608X80N")
      (description "Capacitor (Semiconductor SIM Model)")
      (fields (field (name "PUBLISHER") "Altium Limited"))
      (libsource (lib "Miscellaneous Devices") (part "Cap Semi"))
    )
    (comp (ref "C7_4")
      (value "470nF")
      (footprint "SMD_0603_CAPC1608X80N")
      (description "Capacitor (Semiconductor SIM Model)")
      (fields (field (name "PUBLISHER") "Altium Limited"))
      (libsource (lib "Miscellaneous Devices") (part "Cap Semi"))
    )
    (comp (ref "C7_5")
      (value "470nF")
      (footprint "SMD_0603_CAPC1608X80N")
      (description "Capacitor (Semiconductor SIM Model)")
      (fields (field (name "PUBLISHER") "Altium Limited"))
      (libsource (lib "Miscellaneous Devices") (part "Cap Semi"))
    )
    (comp (ref "C7_6")
      (value "470nF")
      (footprint "SMD_0603_CAPC1608X80N")
      (description "Capacitor (Semiconductor SIM Model)")
      (fields (field (name "PUBLISHER") "Altium Limited"))
      (libsource (lib "Miscellaneous Devices") (part "Cap Semi"))
    )
    (comp (ref "C7_7")
      (value "470nF")
      (footprint "SMD_0603_CAPC1608X80N")
      (description "Capacitor (Semiconductor SIM Model)")
      (fields (field (name "PUBLISHER") "Altium Limited"))
      (libsource (lib "Miscellaneous Devices") (part "Cap Semi"))
    )
    (comp (ref "C7_8")
      (value "470nF")
      (footprint "SMD_0603_CAPC1608X80N")
      (description "Capacitor (Semiconductor SIM Model)")
      (fields (field (name "PUBLISHER") "Altium Limited"))
      (libsource (lib "Miscellaneous Devices") (part "Cap Semi"))
    )
    (comp (ref "C7_9")
      (value "470nF")
      (footprint "SMD_0603_CAPC1608X80N")
      (description "Capacitor (Semiconductor SIM Model)")
      (fields (field (name "PUBLISHER") "Altium Limited"))
      (libsource (lib "Miscellaneous Devices") (part "Cap Semi"))
    )
    (comp (ref "C7_10")
      (value "470nF")
      (footprint "SMD_0603_CAPC1608X80N")
      (description "Capacitor (Semiconductor SIM Model)")
      (fields (field (name "PUBLISHER") "Altium Limited"))
      (libsource (lib "Miscellaneous Devices") (part "Cap Semi"))
    )
    (comp (ref "C7_11")
      (value "470nF")
      (footprint "SMD_0603_CAPC1608X80N")
      (description "Capacitor (Semiconductor SIM Model)")
      (fields (field (name "PUBLISHER") "Altium Limited"))
      (libsource (lib "Miscellaneous Devices") (part "Cap Semi"))
    )
    (comp (ref "C7_12")
      (value "470nF")
      (footprint "SMD_0603_CAPC1608X80N")
      (description "Capacitor (Semiconductor SIM Model)")
      (fields (field (name "PUBLISHER") "Altium Limited"))
      (libsource (lib "Miscellaneous Devices") (part "Cap Semi"))
    )
    (comp (ref "C7_13")
      (value "470nF")
      (footprint "SMD_0603_CAPC1608X80N")
      (description "Capacitor (Semiconductor SIM Model)")
      (fields (field (name "PUBLISHER") "Altium Limited"))
      (libsource (lib "Miscellaneous Devices") (part "Cap Semi"))
    )
    (comp (ref "C7_14")
      (value "470nF")
      (footprint "SMD_0603_CAPC1608X80N")
      (description "Capacitor (Semiconductor SIM Model)")
      (fields (field (name "PUBLISHER") "Altium Limited"))
      (libsource (lib "Miscellaneous Devices") (part "Cap Semi"))
    )
    (comp (ref "C7_15")
      (value "470nF")
      (footprint "SMD_0603_CAPC1608X80N")
      (description "Capacitor (Semiconductor SIM Model)")
      (fields (field (name "PUBLISHER") "Altium Limited"))
      (libsource (lib "Miscellaneous Devices") (part "Cap Semi"))
    )
    (comp (ref "C7_16")
      (value "470nF")
      (footprint "SMD_0603_CAPC1608X80N")
      (description "Capacitor (Semiconductor SIM Model)")
      (fields (field (name "PUBLISHER") "Altium Limited"))
      (libsource (lib "Miscellaneous Devices") (part "Cap Semi"))
    )
    (comp (ref "C8")
      (value "100nF")
      (footprint "SMD_0603_CAPC1608X80N")
      (description "Capacitor")
      (libsource (lib "*") (part "CAP"))
    )
    (comp (ref "C8P_1")
      (value "220uF")
      (footprint "SMD_1210_CAPC3225X279N")
      (description "CL32A227MQVNNNE 220UF 6.3V 20% X5R 1210")
      (fields (field (name "PUBLISHER") "Altium Limited"))
      (libsource (lib "Miscellaneous Devices") (part "Cap Semi"))
    )
    (comp (ref "C8P_2")
      (value "220uF")
      (footprint "SMD_1210_CAPC3225X279N")
      (description "CL32A227MQVNNNE 220UF 6.3V 20% X5R 1210")
      (fields (field (name "PUBLISHER") "Altium Limited"))
      (libsource (lib "Miscellaneous Devices") (part "Cap Semi"))
    )
    (comp (ref "C8P_3")
      (value "220uF")
      (footprint "SMD_1210_CAPC3225X279N")
      (description "CL32A227MQVNNNE 220UF 6.3V 20% X5R 1210")
      (fields (field (name "PUBLISHER") "Altium Limited"))
      (libsource (lib "Miscellaneous Devices") (part "Cap Semi"))
    )
    (comp (ref "C8_1")
      (value "470nF")
      (footprint "SMD_0603_CAPC1608X80N")
      (description "Capacitor (Semiconductor SIM Model)")
      (fields (field (name "PUBLISHER") "Altium Limited"))
      (libsource (lib "Miscellaneous Devices") (part "Cap Semi"))
    )
    (comp (ref "C8_2")
      (value "470nF")
      (footprint "SMD_0603_CAPC1608X80N")
      (description "Capacitor (Semiconductor SIM Model)")
      (fields (field (name "PUBLISHER") "Altium Limited"))
      (libsource (lib "Miscellaneous Devices") (part "Cap Semi"))
    )
    (comp (ref "C8_3")
      (value "470nF")
      (footprint "SMD_0603_CAPC1608X80N")
      (description "Capacitor (Semiconductor SIM Model)")
      (fields (field (name "PUBLISHER") "Altium Limited"))
      (libsource (lib "Miscellaneous Devices") (part "Cap Semi"))
    )
    (comp (ref "C8_4")
      (value "470nF")
      (footprint "SMD_0603_CAPC1608X80N")
      (description "Capacitor (Semiconductor SIM Model)")
      (fields (field (name "PUBLISHER") "Altium Limited"))
      (libsource (lib "Miscellaneous Devices") (part "Cap Semi"))
    )
    (comp (ref "C8_5")
      (value "470nF")
      (footprint "SMD_0603_CAPC1608X80N")
      (description "Capacitor (Semiconductor SIM Model)")
      (fields (field (name "PUBLISHER") "Altium Limited"))
      (libsource (lib "Miscellaneous Devices") (part "Cap Semi"))
    )
    (comp (ref "C8_6")
      (value "470nF")
      (footprint "SMD_0603_CAPC1608X80N")
      (description "Capacitor (Semiconductor SIM Model)")
      (fields (field (name "PUBLISHER") "Altium Limited"))
      (libsource (lib "Miscellaneous Devices") (part "Cap Semi"))
    )
    (comp (ref "C8_7")
      (value "470nF")
      (footprint "SMD_0603_CAPC1608X80N")
      (description "Capacitor (Semiconductor SIM Model)")
      (fields (field (name "PUBLISHER") "Altium Limited"))
      (libsource (lib "Miscellaneous Devices") (part "Cap Semi"))
    )
    (comp (ref "C8_8")
      (value "470nF")
      (footprint "SMD_0603_CAPC1608X80N")
      (description "Capacitor (Semiconductor SIM Model)")
      (fields (field (name "PUBLISHER") "Altium Limited"))
      (libsource (lib "Miscellaneous Devices") (part "Cap Semi"))
    )
    (comp (ref "C8_9")
      (value "470nF")
      (footprint "SMD_0603_CAPC1608X80N")
      (description "Capacitor (Semiconductor SIM Model)")
      (fields (field (name "PUBLISHER") "Altium Limited"))
      (libsource (lib "Miscellaneous Devices") (part "Cap Semi"))
    )
    (comp (ref "C8_10")
      (value "470nF")
      (footprint "SMD_0603_CAPC1608X80N")
      (description "Capacitor (Semiconductor SIM Model)")
      (fields (field (name "PUBLISHER") "Altium Limited"))
      (libsource (lib "Miscellaneous Devices") (part "Cap Semi"))
    )
    (comp (ref "C8_11")
      (value "470nF")
      (footprint "SMD_0603_CAPC1608X80N")
      (description "Capacitor (Semiconductor SIM Model)")
      (fields (field (name "PUBLISHER") "Altium Limited"))
      (libsource (lib "Miscellaneous Devices") (part "Cap Semi"))
    )
    (comp (ref "C8_12")
      (value "470nF")
      (footprint "SMD_0603_CAPC1608X80N")
      (description "Capacitor (Semiconductor SIM Model)")
      (fields (field (name "PUBLISHER") "Altium Limited"))
      (libsource (lib "Miscellaneous Devices") (part "Cap Semi"))
    )
    (comp (ref "C8_13")
      (value "470nF")
      (footprint "SMD_0603_CAPC1608X80N")
      (description "Capacitor (Semiconductor SIM Model)")
      (fields (field (name "PUBLISHER") "Altium Limited"))
      (libsource (lib "Miscellaneous Devices") (part "Cap Semi"))
    )
    (comp (ref "C8_14")
      (value "470nF")
      (footprint "SMD_0603_CAPC1608X80N")
      (description "Capacitor (Semiconductor SIM Model)")
      (fields (field (name "PUBLISHER") "Altium Limited"))
      (libsource (lib "Miscellaneous Devices") (part "Cap Semi"))
    )
    (comp (ref "C8_15")
      (value "470nF")
      (footprint "SMD_0603_CAPC1608X80N")
      (description "Capacitor (Semiconductor SIM Model)")
      (fields (field (name "PUBLISHER") "Altium Limited"))
      (libsource (lib "Miscellaneous Devices") (part "Cap Semi"))
    )
    (comp (ref "C8_16")
      (value "470nF")
      (footprint "SMD_0603_CAPC1608X80N")
      (description "Capacitor (Semiconductor SIM Model)")
      (fields (field (name "PUBLISHER") "Altium Limited"))
      (libsource (lib "Miscellaneous Devices") (part "Cap Semi"))
    )
    (comp (ref "C9")
      (value "100nF")
      (footprint "SMD_0603_CAPC1608X80N")
      (description "Capacitor")
      (libsource (lib "*") (part "CAP"))
    )
    (comp (ref "C9_1")
      (value "470nF")
      (footprint "SMD_0603_CAPC1608X80N")
      (description "Capacitor (Semiconductor SIM Model)")
      (fields (field (name "PUBLISHER") "Altium Limited"))
      (libsource (lib "Miscellaneous Devices") (part "Cap Semi"))
    )
    (comp (ref "C9_2")
      (value "470nF")
      (footprint "SMD_0603_CAPC1608X80N")
      (description "Capacitor (Semiconductor SIM Model)")
      (fields (field (name "PUBLISHER") "Altium Limited"))
      (libsource (lib "Miscellaneous Devices") (part "Cap Semi"))
    )
    (comp (ref "C9_3")
      (value "470nF")
      (footprint "SMD_0603_CAPC1608X80N")
      (description "Capacitor (Semiconductor SIM Model)")
      (fields (field (name "PUBLISHER") "Altium Limited"))
      (libsource (lib "Miscellaneous Devices") (part "Cap Semi"))
    )
    (comp (ref "C9_4")
      (value "470nF")
      (footprint "SMD_0603_CAPC1608X80N")
      (description "Capacitor (Semiconductor SIM Model)")
      (fields (field (name "PUBLISHER") "Altium Limited"))
      (libsource (lib "Miscellaneous Devices") (part "Cap Semi"))
    )
    (comp (ref "C9_5")
      (value "470nF")
      (footprint "SMD_0603_CAPC1608X80N")
      (description "Capacitor (Semiconductor SIM Model)")
      (fields (field (name "PUBLISHER") "Altium Limited"))
      (libsource (lib "Miscellaneous Devices") (part "Cap Semi"))
    )
    (comp (ref "C9_6")
      (value "470nF")
      (footprint "SMD_0603_CAPC1608X80N")
      (description "Capacitor (Semiconductor SIM Model)")
      (fields (field (name "PUBLISHER") "Altium Limited"))
      (libsource (lib "Miscellaneous Devices") (part "Cap Semi"))
    )
    (comp (ref "C9_7")
      (value "470nF")
      (footprint "SMD_0603_CAPC1608X80N")
      (description "Capacitor (Semiconductor SIM Model)")
      (fields (field (name "PUBLISHER") "Altium Limited"))
      (libsource (lib "Miscellaneous Devices") (part "Cap Semi"))
    )
    (comp (ref "C9_8")
      (value "470nF")
      (footprint "SMD_0603_CAPC1608X80N")
      (description "Capacitor (Semiconductor SIM Model)")
      (fields (field (name "PUBLISHER") "Altium Limited"))
      (libsource (lib "Miscellaneous Devices") (part "Cap Semi"))
    )
    (comp (ref "C9_9")
      (value "470nF")
      (footprint "SMD_0603_CAPC1608X80N")
      (description "Capacitor (Semiconductor SIM Model)")
      (fields (field (name "PUBLISHER") "Altium Limited"))
      (libsource (lib "Miscellaneous Devices") (part "Cap Semi"))
    )
    (comp (ref "C9_10")
      (value "470nF")
      (footprint "SMD_0603_CAPC1608X80N")
      (description "Capacitor (Semiconductor SIM Model)")
      (fields (field (name "PUBLISHER") "Altium Limited"))
      (libsource (lib "Miscellaneous Devices") (part "Cap Semi"))
    )
    (comp (ref "C9_11")
      (value "470nF")
      (footprint "SMD_0603_CAPC1608X80N")
      (description "Capacitor (Semiconductor SIM Model)")
      (fields (field (name "PUBLISHER") "Altium Limited"))
      (libsource (lib "Miscellaneous Devices") (part "Cap Semi"))
    )
    (comp (ref "C9_12")
      (value "470nF")
      (footprint "SMD_0603_CAPC1608X80N")
      (description "Capacitor (Semiconductor SIM Model)")
      (fields (field (name "PUBLISHER") "Altium Limited"))
      (libsource (lib "Miscellaneous Devices") (part "Cap Semi"))
    )
    (comp (ref "C9_13")
      (value "470nF")
      (footprint "SMD_0603_CAPC1608X80N")
      (description "Capacitor (Semiconductor SIM Model)")
      (fields (field (name "PUBLISHER") "Altium Limited"))
      (libsource (lib "Miscellaneous Devices") (part "Cap Semi"))
    )
    (comp (ref "C9_14")
      (value "470nF")
      (footprint "SMD_0603_CAPC1608X80N")
      (description "Capacitor (Semiconductor SIM Model)")
      (fields (field (name "PUBLISHER") "Altium Limited"))
      (libsource (lib "Miscellaneous Devices") (part "Cap Semi"))
    )
    (comp (ref "C9_15")
      (value "470nF")
      (footprint "SMD_0603_CAPC1608X80N")
      (description "Capacitor (Semiconductor SIM Model)")
      (fields (field (name "PUBLISHER") "Altium Limited"))
      (libsource (lib "Miscellaneous Devices") (part "Cap Semi"))
    )
    (comp (ref "C9_16")
      (value "470nF")
      (footprint "SMD_0603_CAPC1608X80N")
      (description "Capacitor (Semiconductor SIM Model)")
      (fields (field (name "PUBLISHER") "Altium Limited"))
      (libsource (lib "Miscellaneous Devices") (part "Cap Semi"))
    )
    (comp (ref "C10")
      (value "100nF")
      (footprint "SMD_0603_CAPC1608X80N")
      (description "Capacitor")
      (libsource (lib "*") (part "CAP"))
    )
    (comp (ref "C10_1")
      (value "470nF")
      (footprint "SMD_0603_CAPC1608X80N")
      (description "Capacitor (Semiconductor SIM Model)")
      (fields (field (name "PUBLISHER") "Altium Limited"))
      (libsource (lib "Miscellaneous Devices") (part "Cap Semi"))
    )
    (comp (ref "C10_2")
      (value "470nF")
      (footprint "SMD_0603_CAPC1608X80N")
      (description "Capacitor (Semiconductor SIM Model)")
      (fields (field (name "PUBLISHER") "Altium Limited"))
      (libsource (lib "Miscellaneous Devices") (part "Cap Semi"))
    )
    (comp (ref "C10_3")
      (value "470nF")
      (footprint "SMD_0603_CAPC1608X80N")
      (description "Capacitor (Semiconductor SIM Model)")
      (fields (field (name "PUBLISHER") "Altium Limited"))
      (libsource (lib "Miscellaneous Devices") (part "Cap Semi"))
    )
    (comp (ref "C10_4")
      (value "470nF")
      (footprint "SMD_0603_CAPC1608X80N")
      (description "Capacitor (Semiconductor SIM Model)")
      (fields (field (name "PUBLISHER") "Altium Limited"))
      (libsource (lib "Miscellaneous Devices") (part "Cap Semi"))
    )
    (comp (ref "C10_5")
      (value "470nF")
      (footprint "SMD_0603_CAPC1608X80N")
      (description "Capacitor (Semiconductor SIM Model)")
      (fields (field (name "PUBLISHER") "Altium Limited"))
      (libsource (lib "Miscellaneous Devices") (part "Cap Semi"))
    )
    (comp (ref "C10_6")
      (value "470nF")
      (footprint "SMD_0603_CAPC1608X80N")
      (description "Capacitor (Semiconductor SIM Model)")
      (fields (field (name "PUBLISHER") "Altium Limited"))
      (libsource (lib "Miscellaneous Devices") (part "Cap Semi"))
    )
    (comp (ref "C10_7")
      (value "470nF")
      (footprint "SMD_0603_CAPC1608X80N")
      (description "Capacitor (Semiconductor SIM Model)")
      (fields (field (name "PUBLISHER") "Altium Limited"))
      (libsource (lib "Miscellaneous Devices") (part "Cap Semi"))
    )
    (comp (ref "C10_8")
      (value "470nF")
      (footprint "SMD_0603_CAPC1608X80N")
      (description "Capacitor (Semiconductor SIM Model)")
      (fields (field (name "PUBLISHER") "Altium Limited"))
      (libsource (lib "Miscellaneous Devices") (part "Cap Semi"))
    )
    (comp (ref "C10_9")
      (value "470nF")
      (footprint "SMD_0603_CAPC1608X80N")
      (description "Capacitor (Semiconductor SIM Model)")
      (fields (field (name "PUBLISHER") "Altium Limited"))
      (libsource (lib "Miscellaneous Devices") (part "Cap Semi"))
    )
    (comp (ref "C10_10")
      (value "470nF")
      (footprint "SMD_0603_CAPC1608X80N")
      (description "Capacitor (Semiconductor SIM Model)")
      (fields (field (name "PUBLISHER") "Altium Limited"))
      (libsource (lib "Miscellaneous Devices") (part "Cap Semi"))
    )
    (comp (ref "C10_11")
      (value "470nF")
      (footprint "SMD_0603_CAPC1608X80N")
      (description "Capacitor (Semiconductor SIM Model)")
      (fields (field (name "PUBLISHER") "Altium Limited"))
      (libsource (lib "Miscellaneous Devices") (part "Cap Semi"))
    )
    (comp (ref "C10_12")
      (value "470nF")
      (footprint "SMD_0603_CAPC1608X80N")
      (description "Capacitor (Semiconductor SIM Model)")
      (fields (field (name "PUBLISHER") "Altium Limited"))
      (libsource (lib "Miscellaneous Devices") (part "Cap Semi"))
    )
    (comp (ref "C10_13")
      (value "470nF")
      (footprint "SMD_0603_CAPC1608X80N")
      (description "Capacitor (Semiconductor SIM Model)")
      (fields (field (name "PUBLISHER") "Altium Limited"))
      (libsource (lib "Miscellaneous Devices") (part "Cap Semi"))
    )
    (comp (ref "C10_14")
      (value "470nF")
      (footprint "SMD_0603_CAPC1608X80N")
      (description "Capacitor (Semiconductor SIM Model)")
      (fields (field (name "PUBLISHER") "Altium Limited"))
      (libsource (lib "Miscellaneous Devices") (part "Cap Semi"))
    )
    (comp (ref "C10_15")
      (value "470nF")
      (footprint "SMD_0603_CAPC1608X80N")
      (description "Capacitor (Semiconductor SIM Model)")
      (fields (field (name "PUBLISHER") "Altium Limited"))
      (libsource (lib "Miscellaneous Devices") (part "Cap Semi"))
    )
    (comp (ref "C10_16")
      (value "470nF")
      (footprint "SMD_0603_CAPC1608X80N")
      (description "Capacitor (Semiconductor SIM Model)")
      (fields (field (name "PUBLISHER") "Altium Limited"))
      (libsource (lib "Miscellaneous Devices") (part "Cap Semi"))
    )
    (comp (ref "C11")
      (value "100nF")
      (footprint "SMD_0603_CAPC1608X80N")
      (description "Capacitor")
      (libsource (lib "*") (part "CAP"))
    )
    (comp (ref "C11_1")
      (value "470nF")
      (footprint "SMD_0603_CAPC1608X80N")
      (description "Capacitor (Semiconductor SIM Model)")
      (fields (field (name "PUBLISHER") "Altium Limited"))
      (libsource (lib "Miscellaneous Devices") (part "Cap Semi"))
    )
    (comp (ref "C11_2")
      (value "470nF")
      (footprint "SMD_0603_CAPC1608X80N")
      (description "Capacitor (Semiconductor SIM Model)")
      (fields (field (name "PUBLISHER") "Altium Limited"))
      (libsource (lib "Miscellaneous Devices") (part "Cap Semi"))
    )
    (comp (ref "C11_3")
      (value "470nF")
      (footprint "SMD_0603_CAPC1608X80N")
      (description "Capacitor (Semiconductor SIM Model)")
      (fields (field (name "PUBLISHER") "Altium Limited"))
      (libsource (lib "Miscellaneous Devices") (part "Cap Semi"))
    )
    (comp (ref "C11_4")
      (value "470nF")
      (footprint "SMD_0603_CAPC1608X80N")
      (description "Capacitor (Semiconductor SIM Model)")
      (fields (field (name "PUBLISHER") "Altium Limited"))
      (libsource (lib "Miscellaneous Devices") (part "Cap Semi"))
    )
    (comp (ref "C11_5")
      (value "470nF")
      (footprint "SMD_0603_CAPC1608X80N")
      (description "Capacitor (Semiconductor SIM Model)")
      (fields (field (name "PUBLISHER") "Altium Limited"))
      (libsource (lib "Miscellaneous Devices") (part "Cap Semi"))
    )
    (comp (ref "C11_6")
      (value "470nF")
      (footprint "SMD_0603_CAPC1608X80N")
      (description "Capacitor (Semiconductor SIM Model)")
      (fields (field (name "PUBLISHER") "Altium Limited"))
      (libsource (lib "Miscellaneous Devices") (part "Cap Semi"))
    )
    (comp (ref "C11_7")
      (value "470nF")
      (footprint "SMD_0603_CAPC1608X80N")
      (description "Capacitor (Semiconductor SIM Model)")
      (fields (field (name "PUBLISHER") "Altium Limited"))
      (libsource (lib "Miscellaneous Devices") (part "Cap Semi"))
    )
    (comp (ref "C11_8")
      (value "470nF")
      (footprint "SMD_0603_CAPC1608X80N")
      (description "Capacitor (Semiconductor SIM Model)")
      (fields (field (name "PUBLISHER") "Altium Limited"))
      (libsource (lib "Miscellaneous Devices") (part "Cap Semi"))
    )
    (comp (ref "C11_9")
      (value "470nF")
      (footprint "SMD_0603_CAPC1608X80N")
      (description "Capacitor (Semiconductor SIM Model)")
      (fields (field (name "PUBLISHER") "Altium Limited"))
      (libsource (lib "Miscellaneous Devices") (part "Cap Semi"))
    )
    (comp (ref "C11_10")
      (value "470nF")
      (footprint "SMD_0603_CAPC1608X80N")
      (description "Capacitor (Semiconductor SIM Model)")
      (fields (field (name "PUBLISHER") "Altium Limited"))
      (libsource (lib "Miscellaneous Devices") (part "Cap Semi"))
    )
    (comp (ref "C11_11")
      (value "470nF")
      (footprint "SMD_0603_CAPC1608X80N")
      (description "Capacitor (Semiconductor SIM Model)")
      (fields (field (name "PUBLISHER") "Altium Limited"))
      (libsource (lib "Miscellaneous Devices") (part "Cap Semi"))
    )
    (comp (ref "C11_12")
      (value "470nF")
      (footprint "SMD_0603_CAPC1608X80N")
      (description "Capacitor (Semiconductor SIM Model)")
      (fields (field (name "PUBLISHER") "Altium Limited"))
      (libsource (lib "Miscellaneous Devices") (part "Cap Semi"))
    )
    (comp (ref "C11_13")
      (value "470nF")
      (footprint "SMD_0603_CAPC1608X80N")
      (description "Capacitor (Semiconductor SIM Model)")
      (fields (field (name "PUBLISHER") "Altium Limited"))
      (libsource (lib "Miscellaneous Devices") (part "Cap Semi"))
    )
    (comp (ref "C11_14")
      (value "470nF")
      (footprint "SMD_0603_CAPC1608X80N")
      (description "Capacitor (Semiconductor SIM Model)")
      (fields (field (name "PUBLISHER") "Altium Limited"))
      (libsource (lib "Miscellaneous Devices") (part "Cap Semi"))
    )
    (comp (ref "C11_15")
      (value "470nF")
      (footprint "SMD_0603_CAPC1608X80N")
      (description "Capacitor (Semiconductor SIM Model)")
      (fields (field (name "PUBLISHER") "Altium Limited"))
      (libsource (lib "Miscellaneous Devices") (part "Cap Semi"))
    )
    (comp (ref "C11_16")
      (value "470nF")
      (footprint "SMD_0603_CAPC1608X80N")
      (description "Capacitor (Semiconductor SIM Model)")
      (fields (field (name "PUBLISHER") "Altium Limited"))
      (libsource (lib "Miscellaneous Devices") (part "Cap Semi"))
    )
    (comp (ref "C12")
      (value "18pF")
      (footprint "SMD_0603_CAPC1608X80N")
      (description "Capacitor")
      (libsource (lib "*") (part "CAP"))
    )
    (comp (ref "C12_1")
      (value "470nF")
      (footprint "SMD_0603_CAPC1608X80N")
      (description "Capacitor (Semiconductor SIM Model)")
      (fields (field (name "PUBLISHER") "Altium Limited"))
      (libsource (lib "Miscellaneous Devices") (part "Cap Semi"))
    )
    (comp (ref "C12_2")
      (value "470nF")
      (footprint "SMD_0603_CAPC1608X80N")
      (description "Capacitor (Semiconductor SIM Model)")
      (fields (field (name "PUBLISHER") "Altium Limited"))
      (libsource (lib "Miscellaneous Devices") (part "Cap Semi"))
    )
    (comp (ref "C12_3")
      (value "470nF")
      (footprint "SMD_0603_CAPC1608X80N")
      (description "Capacitor (Semiconductor SIM Model)")
      (fields (field (name "PUBLISHER") "Altium Limited"))
      (libsource (lib "Miscellaneous Devices") (part "Cap Semi"))
    )
    (comp (ref "C12_4")
      (value "470nF")
      (footprint "SMD_0603_CAPC1608X80N")
      (description "Capacitor (Semiconductor SIM Model)")
      (fields (field (name "PUBLISHER") "Altium Limited"))
      (libsource (lib "Miscellaneous Devices") (part "Cap Semi"))
    )
    (comp (ref "C12_5")
      (value "470nF")
      (footprint "SMD_0603_CAPC1608X80N")
      (description "Capacitor (Semiconductor SIM Model)")
      (fields (field (name "PUBLISHER") "Altium Limited"))
      (libsource (lib "Miscellaneous Devices") (part "Cap Semi"))
    )
    (comp (ref "C12_6")
      (value "470nF")
      (footprint "SMD_0603_CAPC1608X80N")
      (description "Capacitor (Semiconductor SIM Model)")
      (fields (field (name "PUBLISHER") "Altium Limited"))
      (libsource (lib "Miscellaneous Devices") (part "Cap Semi"))
    )
    (comp (ref "C12_7")
      (value "470nF")
      (footprint "SMD_0603_CAPC1608X80N")
      (description "Capacitor (Semiconductor SIM Model)")
      (fields (field (name "PUBLISHER") "Altium Limited"))
      (libsource (lib "Miscellaneous Devices") (part "Cap Semi"))
    )
    (comp (ref "C12_8")
      (value "470nF")
      (footprint "SMD_0603_CAPC1608X80N")
      (description "Capacitor (Semiconductor SIM Model)")
      (fields (field (name "PUBLISHER") "Altium Limited"))
      (libsource (lib "Miscellaneous Devices") (part "Cap Semi"))
    )
    (comp (ref "C12_9")
      (value "470nF")
      (footprint "SMD_0603_CAPC1608X80N")
      (description "Capacitor (Semiconductor SIM Model)")
      (fields (field (name "PUBLISHER") "Altium Limited"))
      (libsource (lib "Miscellaneous Devices") (part "Cap Semi"))
    )
    (comp (ref "C12_10")
      (value "470nF")
      (footprint "SMD_0603_CAPC1608X80N")
      (description "Capacitor (Semiconductor SIM Model)")
      (fields (field (name "PUBLISHER") "Altium Limited"))
      (libsource (lib "Miscellaneous Devices") (part "Cap Semi"))
    )
    (comp (ref "C12_11")
      (value "470nF")
      (footprint "SMD_0603_CAPC1608X80N")
      (description "Capacitor (Semiconductor SIM Model)")
      (fields (field (name "PUBLISHER") "Altium Limited"))
      (libsource (lib "Miscellaneous Devices") (part "Cap Semi"))
    )
    (comp (ref "C12_12")
      (value "470nF")
      (footprint "SMD_0603_CAPC1608X80N")
      (description "Capacitor (Semiconductor SIM Model)")
      (fields (field (name "PUBLISHER") "Altium Limited"))
      (libsource (lib "Miscellaneous Devices") (part "Cap Semi"))
    )
    (comp (ref "C12_13")
      (value "470nF")
      (footprint "SMD_0603_CAPC1608X80N")
      (description "Capacitor (Semiconductor SIM Model)")
      (fields (field (name "PUBLISHER") "Altium Limited"))
      (libsource (lib "Miscellaneous Devices") (part "Cap Semi"))
    )
    (comp (ref "C12_14")
      (value "470nF")
      (footprint "SMD_0603_CAPC1608X80N")
      (description "Capacitor (Semiconductor SIM Model)")
      (fields (field (name "PUBLISHER") "Altium Limited"))
      (libsource (lib "Miscellaneous Devices") (part "Cap Semi"))
    )
    (comp (ref "C12_15")
      (value "470nF")
      (footprint "SMD_0603_CAPC1608X80N")
      (description "Capacitor (Semiconductor SIM Model)")
      (fields (field (name "PUBLISHER") "Altium Limited"))
      (libsource (lib "Miscellaneous Devices") (part "Cap Semi"))
    )
    (comp (ref "C12_16")
      (value "470nF")
      (footprint "SMD_0603_CAPC1608X80N")
      (description "Capacitor (Semiconductor SIM Model)")
      (fields (field (name "PUBLISHER") "Altium Limited"))
      (libsource (lib "Miscellaneous Devices") (part "Cap Semi"))
    )
    (comp (ref "C13")
      (value "18pF")
      (footprint "SMD_0603_CAPC1608X80N")
      (description "Capacitor")
      (libsource (lib "*") (part "CAP"))
    )
    (comp (ref "C13_1")
      (value "470nF")
      (footprint "SMD_0603_CAPC1608X80N")
      (description "Capacitor (Semiconductor SIM Model)")
      (fields (field (name "PUBLISHER") "Altium Limited"))
      (libsource (lib "Miscellaneous Devices") (part "Cap Semi"))
    )
    (comp (ref "C13_2")
      (value "470nF")
      (footprint "SMD_0603_CAPC1608X80N")
      (description "Capacitor (Semiconductor SIM Model)")
      (fields (field (name "PUBLISHER") "Altium Limited"))
      (libsource (lib "Miscellaneous Devices") (part "Cap Semi"))
    )
    (comp (ref "C13_3")
      (value "470nF")
      (footprint "SMD_0603_CAPC1608X80N")
      (description "Capacitor (Semiconductor SIM Model)")
      (fields (field (name "PUBLISHER") "Altium Limited"))
      (libsource (lib "Miscellaneous Devices") (part "Cap Semi"))
    )
    (comp (ref "C13_4")
      (value "470nF")
      (footprint "SMD_0603_CAPC1608X80N")
      (description "Capacitor (Semiconductor SIM Model)")
      (fields (field (name "PUBLISHER") "Altium Limited"))
      (libsource (lib "Miscellaneous Devices") (part "Cap Semi"))
    )
    (comp (ref "C13_5")
      (value "470nF")
      (footprint "SMD_0603_CAPC1608X80N")
      (description "Capacitor (Semiconductor SIM Model)")
      (fields (field (name "PUBLISHER") "Altium Limited"))
      (libsource (lib "Miscellaneous Devices") (part "Cap Semi"))
    )
    (comp (ref "C13_6")
      (value "470nF")
      (footprint "SMD_0603_CAPC1608X80N")
      (description "Capacitor (Semiconductor SIM Model)")
      (fields (field (name "PUBLISHER") "Altium Limited"))
      (libsource (lib "Miscellaneous Devices") (part "Cap Semi"))
    )
    (comp (ref "C13_7")
      (value "470nF")
      (footprint "SMD_0603_CAPC1608X80N")
      (description "Capacitor (Semiconductor SIM Model)")
      (fields (field (name "PUBLISHER") "Altium Limited"))
      (libsource (lib "Miscellaneous Devices") (part "Cap Semi"))
    )
    (comp (ref "C13_8")
      (value "470nF")
      (footprint "SMD_0603_CAPC1608X80N")
      (description "Capacitor (Semiconductor SIM Model)")
      (fields (field (name "PUBLISHER") "Altium Limited"))
      (libsource (lib "Miscellaneous Devices") (part "Cap Semi"))
    )
    (comp (ref "C13_9")
      (value "470nF")
      (footprint "SMD_0603_CAPC1608X80N")
      (description "Capacitor (Semiconductor SIM Model)")
      (fields (field (name "PUBLISHER") "Altium Limited"))
      (libsource (lib "Miscellaneous Devices") (part "Cap Semi"))
    )
    (comp (ref "C13_10")
      (value "470nF")
      (footprint "SMD_0603_CAPC1608X80N")
      (description "Capacitor (Semiconductor SIM Model)")
      (fields (field (name "PUBLISHER") "Altium Limited"))
      (libsource (lib "Miscellaneous Devices") (part "Cap Semi"))
    )
    (comp (ref "C13_11")
      (value "470nF")
      (footprint "SMD_0603_CAPC1608X80N")
      (description "Capacitor (Semiconductor SIM Model)")
      (fields (field (name "PUBLISHER") "Altium Limited"))
      (libsource (lib "Miscellaneous Devices") (part "Cap Semi"))
    )
    (comp (ref "C13_12")
      (value "470nF")
      (footprint "SMD_0603_CAPC1608X80N")
      (description "Capacitor (Semiconductor SIM Model)")
      (fields (field (name "PUBLISHER") "Altium Limited"))
      (libsource (lib "Miscellaneous Devices") (part "Cap Semi"))
    )
    (comp (ref "C13_13")
      (value "470nF")
      (footprint "SMD_0603_CAPC1608X80N")
      (description "Capacitor (Semiconductor SIM Model)")
      (fields (field (name "PUBLISHER") "Altium Limited"))
      (libsource (lib "Miscellaneous Devices") (part "Cap Semi"))
    )
    (comp (ref "C13_14")
      (value "470nF")
      (footprint "SMD_0603_CAPC1608X80N")
      (description "Capacitor (Semiconductor SIM Model)")
      (fields (field (name "PUBLISHER") "Altium Limited"))
      (libsource (lib "Miscellaneous Devices") (part "Cap Semi"))
    )
    (comp (ref "C13_15")
      (value "470nF")
      (footprint "SMD_0603_CAPC1608X80N")
      (description "Capacitor (Semiconductor SIM Model)")
      (fields (field (name "PUBLISHER") "Altium Limited"))
      (libsource (lib "Miscellaneous Devices") (part "Cap Semi"))
    )
    (comp (ref "C13_16")
      (value "470nF")
      (footprint "SMD_0603_CAPC1608X80N")
      (description "Capacitor (Semiconductor SIM Model)")
      (fields (field (name "PUBLISHER") "Altium Limited"))
      (libsource (lib "Miscellaneous Devices") (part "Cap Semi"))
    )
    (comp (ref "C14")
      (value "10uF/16V")
      (footprint "SMD_0805_CAPC2012X145N")
      (description "Capacitor")
      (libsource (lib "*") (part "CAP"))
    )
    (comp (ref "C14_1")
      (value "470nF")
      (footprint "SMD_0603_CAPC1608X80N")
      (description "Capacitor (Semiconductor SIM Model)")
      (fields (field (name "PUBLISHER") "Altium Limited"))
      (libsource (lib "Miscellaneous Devices") (part "Cap Semi"))
    )
    (comp (ref "C14_2")
      (value "470nF")
      (footprint "SMD_0603_CAPC1608X80N")
      (description "Capacitor (Semiconductor SIM Model)")
      (fields (field (name "PUBLISHER") "Altium Limited"))
      (libsource (lib "Miscellaneous Devices") (part "Cap Semi"))
    )
    (comp (ref "C14_3")
      (value "470nF")
      (footprint "SMD_0603_CAPC1608X80N")
      (description "Capacitor (Semiconductor SIM Model)")
      (fields (field (name "PUBLISHER") "Altium Limited"))
      (libsource (lib "Miscellaneous Devices") (part "Cap Semi"))
    )
    (comp (ref "C14_4")
      (value "470nF")
      (footprint "SMD_0603_CAPC1608X80N")
      (description "Capacitor (Semiconductor SIM Model)")
      (fields (field (name "PUBLISHER") "Altium Limited"))
      (libsource (lib "Miscellaneous Devices") (part "Cap Semi"))
    )
    (comp (ref "C14_5")
      (value "470nF")
      (footprint "SMD_0603_CAPC1608X80N")
      (description "Capacitor (Semiconductor SIM Model)")
      (fields (field (name "PUBLISHER") "Altium Limited"))
      (libsource (lib "Miscellaneous Devices") (part "Cap Semi"))
    )
    (comp (ref "C14_6")
      (value "470nF")
      (footprint "SMD_0603_CAPC1608X80N")
      (description "Capacitor (Semiconductor SIM Model)")
      (fields (field (name "PUBLISHER") "Altium Limited"))
      (libsource (lib "Miscellaneous Devices") (part "Cap Semi"))
    )
    (comp (ref "C14_7")
      (value "470nF")
      (footprint "SMD_0603_CAPC1608X80N")
      (description "Capacitor (Semiconductor SIM Model)")
      (fields (field (name "PUBLISHER") "Altium Limited"))
      (libsource (lib "Miscellaneous Devices") (part "Cap Semi"))
    )
    (comp (ref "C14_8")
      (value "470nF")
      (footprint "SMD_0603_CAPC1608X80N")
      (description "Capacitor (Semiconductor SIM Model)")
      (fields (field (name "PUBLISHER") "Altium Limited"))
      (libsource (lib "Miscellaneous Devices") (part "Cap Semi"))
    )
    (comp (ref "C14_9")
      (value "470nF")
      (footprint "SMD_0603_CAPC1608X80N")
      (description "Capacitor (Semiconductor SIM Model)")
      (fields (field (name "PUBLISHER") "Altium Limited"))
      (libsource (lib "Miscellaneous Devices") (part "Cap Semi"))
    )
    (comp (ref "C14_10")
      (value "470nF")
      (footprint "SMD_0603_CAPC1608X80N")
      (description "Capacitor (Semiconductor SIM Model)")
      (fields (field (name "PUBLISHER") "Altium Limited"))
      (libsource (lib "Miscellaneous Devices") (part "Cap Semi"))
    )
    (comp (ref "C14_11")
      (value "470nF")
      (footprint "SMD_0603_CAPC1608X80N")
      (description "Capacitor (Semiconductor SIM Model)")
      (fields (field (name "PUBLISHER") "Altium Limited"))
      (libsource (lib "Miscellaneous Devices") (part "Cap Semi"))
    )
    (comp (ref "C14_12")
      (value "470nF")
      (footprint "SMD_0603_CAPC1608X80N")
      (description "Capacitor (Semiconductor SIM Model)")
      (fields (field (name "PUBLISHER") "Altium Limited"))
      (libsource (lib "Miscellaneous Devices") (part "Cap Semi"))
    )
    (comp (ref "C14_13")
      (value "470nF")
      (footprint "SMD_0603_CAPC1608X80N")
      (description "Capacitor (Semiconductor SIM Model)")
      (fields (field (name "PUBLISHER") "Altium Limited"))
      (libsource (lib "Miscellaneous Devices") (part "Cap Semi"))
    )
    (comp (ref "C14_14")
      (value "470nF")
      (footprint "SMD_0603_CAPC1608X80N")
      (description "Capacitor (Semiconductor SIM Model)")
      (fields (field (name "PUBLISHER") "Altium Limited"))
      (libsource (lib "Miscellaneous Devices") (part "Cap Semi"))
    )
    (comp (ref "C14_15")
      (value "470nF")
      (footprint "SMD_0603_CAPC1608X80N")
      (description "Capacitor (Semiconductor SIM Model)")
      (fields (field (name "PUBLISHER") "Altium Limited"))
      (libsource (lib "Miscellaneous Devices") (part "Cap Semi"))
    )
    (comp (ref "C14_16")
      (value "470nF")
      (footprint "SMD_0603_CAPC1608X80N")
      (description "Capacitor (Semiconductor SIM Model)")
      (fields (field (name "PUBLISHER") "Altium Limited"))
      (libsource (lib "Miscellaneous Devices") (part "Cap Semi"))
    )
    (comp (ref "C15")
      (value "10uF/16V")
      (footprint "SMD_0805_CAPC2012X145N")
      (description "Capacitor")
      (libsource (lib "*") (part "CAP"))
    )
    (comp (ref "C15_1")
      (value "470nF")
      (footprint "SMD_0603_CAPC1608X80N")
      (description "Capacitor (Semiconductor SIM Model)")
      (fields (field (name "PUBLISHER") "Altium Limited"))
      (libsource (lib "Miscellaneous Devices") (part "Cap Semi"))
    )
    (comp (ref "C15_2")
      (value "470nF")
      (footprint "SMD_0603_CAPC1608X80N")
      (description "Capacitor (Semiconductor SIM Model)")
      (fields (field (name "PUBLISHER") "Altium Limited"))
      (libsource (lib "Miscellaneous Devices") (part "Cap Semi"))
    )
    (comp (ref "C15_3")
      (value "470nF")
      (footprint "SMD_0603_CAPC1608X80N")
      (description "Capacitor (Semiconductor SIM Model)")
      (fields (field (name "PUBLISHER") "Altium Limited"))
      (libsource (lib "Miscellaneous Devices") (part "Cap Semi"))
    )
    (comp (ref "C15_4")
      (value "470nF")
      (footprint "SMD_0603_CAPC1608X80N")
      (description "Capacitor (Semiconductor SIM Model)")
      (fields (field (name "PUBLISHER") "Altium Limited"))
      (libsource (lib "Miscellaneous Devices") (part "Cap Semi"))
    )
    (comp (ref "C15_5")
      (value "470nF")
      (footprint "SMD_0603_CAPC1608X80N")
      (description "Capacitor (Semiconductor SIM Model)")
      (fields (field (name "PUBLISHER") "Altium Limited"))
      (libsource (lib "Miscellaneous Devices") (part "Cap Semi"))
    )
    (comp (ref "C15_6")
      (value "470nF")
      (footprint "SMD_0603_CAPC1608X80N")
      (description "Capacitor (Semiconductor SIM Model)")
      (fields (field (name "PUBLISHER") "Altium Limited"))
      (libsource (lib "Miscellaneous Devices") (part "Cap Semi"))
    )
    (comp (ref "C15_7")
      (value "470nF")
      (footprint "SMD_0603_CAPC1608X80N")
      (description "Capacitor (Semiconductor SIM Model)")
      (fields (field (name "PUBLISHER") "Altium Limited"))
      (libsource (lib "Miscellaneous Devices") (part "Cap Semi"))
    )
    (comp (ref "C15_8")
      (value "470nF")
      (footprint "SMD_0603_CAPC1608X80N")
      (description "Capacitor (Semiconductor SIM Model)")
      (fields (field (name "PUBLISHER") "Altium Limited"))
      (libsource (lib "Miscellaneous Devices") (part "Cap Semi"))
    )
    (comp (ref "C15_9")
      (value "470nF")
      (footprint "SMD_0603_CAPC1608X80N")
      (description "Capacitor (Semiconductor SIM Model)")
      (fields (field (name "PUBLISHER") "Altium Limited"))
      (libsource (lib "Miscellaneous Devices") (part "Cap Semi"))
    )
    (comp (ref "C15_10")
      (value "470nF")
      (footprint "SMD_0603_CAPC1608X80N")
      (description "Capacitor (Semiconductor SIM Model)")
      (fields (field (name "PUBLISHER") "Altium Limited"))
      (libsource (lib "Miscellaneous Devices") (part "Cap Semi"))
    )
    (comp (ref "C15_11")
      (value "470nF")
      (footprint "SMD_0603_CAPC1608X80N")
      (description "Capacitor (Semiconductor SIM Model)")
      (fields (field (name "PUBLISHER") "Altium Limited"))
      (libsource (lib "Miscellaneous Devices") (part "Cap Semi"))
    )
    (comp (ref "C15_12")
      (value "470nF")
      (footprint "SMD_0603_CAPC1608X80N")
      (description "Capacitor (Semiconductor SIM Model)")
      (fields (field (name "PUBLISHER") "Altium Limited"))
      (libsource (lib "Miscellaneous Devices") (part "Cap Semi"))
    )
    (comp (ref "C15_13")
      (value "470nF")
      (footprint "SMD_0603_CAPC1608X80N")
      (description "Capacitor (Semiconductor SIM Model)")
      (fields (field (name "PUBLISHER") "Altium Limited"))
      (libsource (lib "Miscellaneous Devices") (part "Cap Semi"))
    )
    (comp (ref "C15_14")
      (value "470nF")
      (footprint "SMD_0603_CAPC1608X80N")
      (description "Capacitor (Semiconductor SIM Model)")
      (fields (field (name "PUBLISHER") "Altium Limited"))
      (libsource (lib "Miscellaneous Devices") (part "Cap Semi"))
    )
    (comp (ref "C15_15")
      (value "470nF")
      (footprint "SMD_0603_CAPC1608X80N")
      (description "Capacitor (Semiconductor SIM Model)")
      (fields (field (name "PUBLISHER") "Altium Limited"))
      (libsource (lib "Miscellaneous Devices") (part "Cap Semi"))
    )
    (comp (ref "C15_16")
      (value "470nF")
      (footprint "SMD_0603_CAPC1608X80N")
      (description "Capacitor (Semiconductor SIM Model)")
      (fields (field (name "PUBLISHER") "Altium Limited"))
      (libsource (lib "Miscellaneous Devices") (part "Cap Semi"))
    )
    (comp (ref "C16")
      (value "220uF")
      (footprint "SMD_1210_CAPC3225X279N")
      (description "CL32A227MQVNNNE 220UF 6.3V 20% X5R 1210")
      (fields (field (name "PUBLISHER") "Altium Limited"))
      (libsource (lib "Miscellaneous Devices") (part "Cap Semi"))
    )
    (comp (ref "C16_1")
      (value "470nF")
      (footprint "SMD_0603_CAPC1608X80N")
      (description "Capacitor (Semiconductor SIM Model)")
      (fields (field (name "PUBLISHER") "Altium Limited"))
      (libsource (lib "Miscellaneous Devices") (part "Cap Semi"))
    )
    (comp (ref "C16_2")
      (value "470nF")
      (footprint "SMD_0603_CAPC1608X80N")
      (description "Capacitor (Semiconductor SIM Model)")
      (fields (field (name "PUBLISHER") "Altium Limited"))
      (libsource (lib "Miscellaneous Devices") (part "Cap Semi"))
    )
    (comp (ref "C16_3")
      (value "470nF")
      (footprint "SMD_0603_CAPC1608X80N")
      (description "Capacitor (Semiconductor SIM Model)")
      (fields (field (name "PUBLISHER") "Altium Limited"))
      (libsource (lib "Miscellaneous Devices") (part "Cap Semi"))
    )
    (comp (ref "C16_4")
      (value "470nF")
      (footprint "SMD_0603_CAPC1608X80N")
      (description "Capacitor (Semiconductor SIM Model)")
      (fields (field (name "PUBLISHER") "Altium Limited"))
      (libsource (lib "Miscellaneous Devices") (part "Cap Semi"))
    )
    (comp (ref "C16_5")
      (value "470nF")
      (footprint "SMD_0603_CAPC1608X80N")
      (description "Capacitor (Semiconductor SIM Model)")
      (fields (field (name "PUBLISHER") "Altium Limited"))
      (libsource (lib "Miscellaneous Devices") (part "Cap Semi"))
    )
    (comp (ref "C16_6")
      (value "470nF")
      (footprint "SMD_0603_CAPC1608X80N")
      (description "Capacitor (Semiconductor SIM Model)")
      (fields (field (name "PUBLISHER") "Altium Limited"))
      (libsource (lib "Miscellaneous Devices") (part "Cap Semi"))
    )
    (comp (ref "C16_7")
      (value "470nF")
      (footprint "SMD_0603_CAPC1608X80N")
      (description "Capacitor (Semiconductor SIM Model)")
      (fields (field (name "PUBLISHER") "Altium Limited"))
      (libsource (lib "Miscellaneous Devices") (part "Cap Semi"))
    )
    (comp (ref "C16_8")
      (value "470nF")
      (footprint "SMD_0603_CAPC1608X80N")
      (description "Capacitor (Semiconductor SIM Model)")
      (fields (field (name "PUBLISHER") "Altium Limited"))
      (libsource (lib "Miscellaneous Devices") (part "Cap Semi"))
    )
    (comp (ref "C16_9")
      (value "470nF")
      (footprint "SMD_0603_CAPC1608X80N")
      (description "Capacitor (Semiconductor SIM Model)")
      (fields (field (name "PUBLISHER") "Altium Limited"))
      (libsource (lib "Miscellaneous Devices") (part "Cap Semi"))
    )
    (comp (ref "C16_10")
      (value "470nF")
      (footprint "SMD_0603_CAPC1608X80N")
      (description "Capacitor (Semiconductor SIM Model)")
      (fields (field (name "PUBLISHER") "Altium Limited"))
      (libsource (lib "Miscellaneous Devices") (part "Cap Semi"))
    )
    (comp (ref "C16_11")
      (value "470nF")
      (footprint "SMD_0603_CAPC1608X80N")
      (description "Capacitor (Semiconductor SIM Model)")
      (fields (field (name "PUBLISHER") "Altium Limited"))
      (libsource (lib "Miscellaneous Devices") (part "Cap Semi"))
    )
    (comp (ref "C16_12")
      (value "470nF")
      (footprint "SMD_0603_CAPC1608X80N")
      (description "Capacitor (Semiconductor SIM Model)")
      (fields (field (name "PUBLISHER") "Altium Limited"))
      (libsource (lib "Miscellaneous Devices") (part "Cap Semi"))
    )
    (comp (ref "C16_13")
      (value "470nF")
      (footprint "SMD_0603_CAPC1608X80N")
      (description "Capacitor (Semiconductor SIM Model)")
      (fields (field (name "PUBLISHER") "Altium Limited"))
      (libsource (lib "Miscellaneous Devices") (part "Cap Semi"))
    )
    (comp (ref "C16_14")
      (value "470nF")
      (footprint "SMD_0603_CAPC1608X80N")
      (description "Capacitor (Semiconductor SIM Model)")
      (fields (field (name "PUBLISHER") "Altium Limited"))
      (libsource (lib "Miscellaneous Devices") (part "Cap Semi"))
    )
    (comp (ref "C16_15")
      (value "470nF")
      (footprint "SMD_0603_CAPC1608X80N")
      (description "Capacitor (Semiconductor SIM Model)")
      (fields (field (name "PUBLISHER") "Altium Limited"))
      (libsource (lib "Miscellaneous Devices") (part "Cap Semi"))
    )
    (comp (ref "C16_16")
      (value "470nF")
      (footprint "SMD_0603_CAPC1608X80N")
      (description "Capacitor (Semiconductor SIM Model)")
      (fields (field (name "PUBLISHER") "Altium Limited"))
      (libsource (lib "Miscellaneous Devices") (part "Cap Semi"))
    )
    (comp (ref "C17")
      (value "22uF/6.3V")
      (footprint "SMD_0805_CAPC2012X145N")
      (description "Capacitor")
      (libsource (lib "*") (part "CAP"))
    )
    (comp (ref "C25")
      (value "22uF/6.3V")
      (footprint "SMD_0805_CAPC2012X145N")
      (description "Capacitor")
      (libsource (lib "*") (part "CAP"))
    )
    (comp (ref "C26")
      (value "22uF/6.3V")
      (footprint "SMD_0805_CAPC2012X145N")
      (description "Capacitor")
      (libsource (lib "*") (part "CAP"))
    )
    (comp (ref "C_220_1")
      (value "(OPT)220uF")
      (footprint "SMD_1210_CAPC3225X279N")
      (description "CL32A227MQVNNNE 220UF 6.3V 20% X5R 1210")
      (fields (field (name "PUBLISHER") "Altium Limited"))
      (libsource (lib "Miscellaneous Devices") (part "Cap Semi"))
    )
    (comp (ref "C_220_2")
      (value "(OPT)220uF")
      (footprint "SMD_1210_CAPC3225X279N")
      (description "CL32A227MQVNNNE 220UF 6.3V 20% X5R 1210")
      (fields (field (name "PUBLISHER") "Altium Limited"))
      (libsource (lib "Miscellaneous Devices") (part "Cap Semi"))
    )
    (comp (ref "C_220_3")
      (value "(OPT)220uF")
      (footprint "SMD_1210_CAPC3225X279N")
      (description "CL32A227MQVNNNE 220UF 6.3V 20% X5R 1210")
      (fields (field (name "PUBLISHER") "Altium Limited"))
      (libsource (lib "Miscellaneous Devices") (part "Cap Semi"))
    )
    (comp (ref "C_220_4")
      (value "(OPT)220uF")
      (footprint "SMD_1210_CAPC3225X279N")
      (description "CL32A227MQVNNNE 220UF 6.3V 20% X5R 1210")
      (fields (field (name "PUBLISHER") "Altium Limited"))
      (libsource (lib "Miscellaneous Devices") (part "Cap Semi"))
    )
    (comp (ref "C_220_5")
      (value "(OPT)220uF")
      (footprint "SMD_1210_CAPC3225X279N")
      (description "CL32A227MQVNNNE 220UF 6.3V 20% X5R 1210")
      (fields (field (name "PUBLISHER") "Altium Limited"))
      (libsource (lib "Miscellaneous Devices") (part "Cap Semi"))
    )
    (comp (ref "C_220_6")
      (value "(OPT)220uF")
      (footprint "SMD_1210_CAPC3225X279N")
      (description "CL32A227MQVNNNE 220UF 6.3V 20% X5R 1210")
      (fields (field (name "PUBLISHER") "Altium Limited"))
      (libsource (lib "Miscellaneous Devices") (part "Cap Semi"))
    )
    (comp (ref "C_220_7")
      (value "(OPT)220uF")
      (footprint "SMD_1210_CAPC3225X279N")
      (description "CL32A227MQVNNNE 220UF 6.3V 20% X5R 1210")
      (fields (field (name "PUBLISHER") "Altium Limited"))
      (libsource (lib "Miscellaneous Devices") (part "Cap Semi"))
    )
    (comp (ref "C_220_8")
      (value "(OPT)220uF")
      (footprint "SMD_1210_CAPC3225X279N")
      (description "CL32A227MQVNNNE 220UF 6.3V 20% X5R 1210")
      (fields (field (name "PUBLISHER") "Altium Limited"))
      (libsource (lib "Miscellaneous Devices") (part "Cap Semi"))
    )
    (comp (ref "C_220_9")
      (value "(OPT)220uF")
      (footprint "SMD_1210_CAPC3225X279N")
      (description "CL32A227MQVNNNE 220UF 6.3V 20% X5R 1210")
      (fields (field (name "PUBLISHER") "Altium Limited"))
      (libsource (lib "Miscellaneous Devices") (part "Cap Semi"))
    )
    (comp (ref "C_220_10")
      (value "(OPT)220uF")
      (footprint "SMD_1210_CAPC3225X279N")
      (description "CL32A227MQVNNNE 220UF 6.3V 20% X5R 1210")
      (fields (field (name "PUBLISHER") "Altium Limited"))
      (libsource (lib "Miscellaneous Devices") (part "Cap Semi"))
    )
    (comp (ref "C_220_11")
      (value "(OPT)220uF")
      (footprint "SMD_1210_CAPC3225X279N")
      (description "CL32A227MQVNNNE 220UF 6.3V 20% X5R 1210")
      (fields (field (name "PUBLISHER") "Altium Limited"))
      (libsource (lib "Miscellaneous Devices") (part "Cap Semi"))
    )
    (comp (ref "C_220_12")
      (value "(OPT)220uF")
      (footprint "SMD_1210_CAPC3225X279N")
      (description "CL32A227MQVNNNE 220UF 6.3V 20% X5R 1210")
      (fields (field (name "PUBLISHER") "Altium Limited"))
      (libsource (lib "Miscellaneous Devices") (part "Cap Semi"))
    )
    (comp (ref "C_220_13")
      (value "(OPT)220uF")
      (footprint "SMD_1210_CAPC3225X279N")
      (description "CL32A227MQVNNNE 220UF 6.3V 20% X5R 1210")
      (fields (field (name "PUBLISHER") "Altium Limited"))
      (libsource (lib "Miscellaneous Devices") (part "Cap Semi"))
    )
    (comp (ref "C_220_14")
      (value "(OPT)220uF")
      (footprint "SMD_1210_CAPC3225X279N")
      (description "CL32A227MQVNNNE 220UF 6.3V 20% X5R 1210")
      (fields (field (name "PUBLISHER") "Altium Limited"))
      (libsource (lib "Miscellaneous Devices") (part "Cap Semi"))
    )
    (comp (ref "C_220_15")
      (value "(OPT)220uF")
      (footprint "SMD_1210_CAPC3225X279N")
      (description "CL32A227MQVNNNE 220UF 6.3V 20% X5R 1210")
      (fields (field (name "PUBLISHER") "Altium Limited"))
      (libsource (lib "Miscellaneous Devices") (part "Cap Semi"))
    )
    (comp (ref "C_220_16")
      (value "(OPT)220uF")
      (footprint "SMD_1210_CAPC3225X279N")
      (description "CL32A227MQVNNNE 220UF 6.3V 20% X5R 1210")
      (fields (field (name "PUBLISHER") "Altium Limited"))
      (libsource (lib "Miscellaneous Devices") (part "Cap Semi"))
    )
    (comp (ref "C_220_17")
      (value "(OPT)220uF")
      (footprint "SMD_1210_CAPC3225X279N")
      (description "CL32A227MQVNNNE 220UF 6.3V 20% X5R 1210")
      (fields (field (name "PUBLISHER") "Altium Limited"))
      (libsource (lib "Miscellaneous Devices") (part "Cap Semi"))
    )
    (comp (ref "C_220_18")
      (value "(OPT)220uF")
      (footprint "SMD_1210_CAPC3225X279N")
      (description "CL32A227MQVNNNE 220UF 6.3V 20% X5R 1210")
      (fields (field (name "PUBLISHER") "Altium Limited"))
      (libsource (lib "Miscellaneous Devices") (part "Cap Semi"))
    )
    (comp (ref "C_220_19")
      (value "(OPT)220uF")
      (footprint "SMD_1210_CAPC3225X279N")
      (description "CL32A227MQVNNNE 220UF 6.3V 20% X5R 1210")
      (fields (field (name "PUBLISHER") "Altium Limited"))
      (libsource (lib "Miscellaneous Devices") (part "Cap Semi"))
    )
    (comp (ref "C_220_20")
      (value "(OPT)220uF")
      (footprint "SMD_1210_CAPC3225X279N")
      (description "CL32A227MQVNNNE 220UF 6.3V 20% X5R 1210")
      (fields (field (name "PUBLISHER") "Altium Limited"))
      (libsource (lib "Miscellaneous Devices") (part "Cap Semi"))
    )
    (comp (ref "C_220_21")
      (value "(OPT)220uF")
      (footprint "SMD_1210_CAPC3225X279N")
      (description "CL32A227MQVNNNE 220UF 6.3V 20% X5R 1210")
      (fields (field (name "PUBLISHER") "Altium Limited"))
      (libsource (lib "Miscellaneous Devices") (part "Cap Semi"))
    )
    (comp (ref "C_220_22")
      (value "(OPT)220uF")
      (footprint "SMD_1210_CAPC3225X279N")
      (description "CL32A227MQVNNNE 220UF 6.3V 20% X5R 1210")
      (fields (field (name "PUBLISHER") "Altium Limited"))
      (libsource (lib "Miscellaneous Devices") (part "Cap Semi"))
    )
    (comp (ref "C_220_23")
      (value "(OPT)220uF")
      (footprint "SMD_1210_CAPC3225X279N")
      (description "CL32A227MQVNNNE 220UF 6.3V 20% X5R 1210")
      (fields (field (name "PUBLISHER") "Altium Limited"))
      (libsource (lib "Miscellaneous Devices") (part "Cap Semi"))
    )
    (comp (ref "C_220_24")
      (value "(OPT)220uF")
      (footprint "SMD_1210_CAPC3225X279N")
      (description "CL32A227MQVNNNE 220UF 6.3V 20% X5R 1210")
      (fields (field (name "PUBLISHER") "Altium Limited"))
      (libsource (lib "Miscellaneous Devices") (part "Cap Semi"))
    )
    (comp (ref "C_220_25")
      (value "(OPT)220uF")
      (footprint "SMD_1210_CAPC3225X279N")
      (description "CL32A227MQVNNNE 220UF 6.3V 20% X5R 1210")
      (fields (field (name "PUBLISHER") "Altium Limited"))
      (libsource (lib "Miscellaneous Devices") (part "Cap Semi"))
    )
    (comp (ref "C_220_26")
      (value "(OPT)220uF")
      (footprint "SMD_1210_CAPC3225X279N")
      (description "CL32A227MQVNNNE 220UF 6.3V 20% X5R 1210")
      (fields (field (name "PUBLISHER") "Altium Limited"))
      (libsource (lib "Miscellaneous Devices") (part "Cap Semi"))
    )
    (comp (ref "C_220_27")
      (value "(OPT)220uF")
      (footprint "SMD_1210_CAPC3225X279N")
      (description "CL32A227MQVNNNE 220UF 6.3V 20% X5R 1210")
      (fields (field (name "PUBLISHER") "Altium Limited"))
      (libsource (lib "Miscellaneous Devices") (part "Cap Semi"))
    )
    (comp (ref "C_220_28")
      (value "(OPT)220uF")
      (footprint "SMD_1210_CAPC3225X279N")
      (description "CL32A227MQVNNNE 220UF 6.3V 20% X5R 1210")
      (fields (field (name "PUBLISHER") "Altium Limited"))
      (libsource (lib "Miscellaneous Devices") (part "Cap Semi"))
    )
    (comp (ref "C_220_29")
      (value "(OPT)220uF")
      (footprint "SMD_1210_CAPC3225X279N")
      (description "CL32A227MQVNNNE 220UF 6.3V 20% X5R 1210")
      (fields (field (name "PUBLISHER") "Altium Limited"))
      (libsource (lib "Miscellaneous Devices") (part "Cap Semi"))
    )
    (comp (ref "C_220_30")
      (value "(OPT)220uF")
      (footprint "SMD_1210_CAPC3225X279N")
      (description "CL32A227MQVNNNE 220UF 6.3V 20% X5R 1210")
      (fields (field (name "PUBLISHER") "Altium Limited"))
      (libsource (lib "Miscellaneous Devices") (part "Cap Semi"))
    )
    (comp (ref "C_220_31")
      (value "(OPT)220uF")
      (footprint "SMD_1210_CAPC3225X279N")
      (description "CL32A227MQVNNNE 220UF 6.3V 20% X5R 1210")
      (fields (field (name "PUBLISHER") "Altium Limited"))
      (libsource (lib "Miscellaneous Devices") (part "Cap Semi"))
    )
    (comp (ref "C_220_32")
      (value "(OPT)220uF")
      (footprint "SMD_1210_CAPC3225X279N")
      (description "CL32A227MQVNNNE 220UF 6.3V 20% X5R 1210")
      (fields (field (name "PUBLISHER") "Altium Limited"))
      (libsource (lib "Miscellaneous Devices") (part "Cap Semi"))
    )
    (comp (ref "C_220_33")
      (value "(OPT)220uF")
      (footprint "SMD_1210_CAPC3225X279N")
      (description "CL32A227MQVNNNE 220UF 6.3V 20% X5R 1210")
      (fields (field (name "PUBLISHER") "Altium Limited"))
      (libsource (lib "Miscellaneous Devices") (part "Cap Semi"))
    )
    (comp (ref "C_220_34")
      (value "(OPT)220uF")
      (footprint "SMD_1210_CAPC3225X279N")
      (description "CL32A227MQVNNNE 220UF 6.3V 20% X5R 1210")
      (fields (field (name "PUBLISHER") "Altium Limited"))
      (libsource (lib "Miscellaneous Devices") (part "Cap Semi"))
    )
    (comp (ref "C_220_35")
      (value "(OPT)220uF")
      (footprint "SMD_1210_CAPC3225X279N")
      (description "CL32A227MQVNNNE 220UF 6.3V 20% X5R 1210")
      (fields (field (name "PUBLISHER") "Altium Limited"))
      (libsource (lib "Miscellaneous Devices") (part "Cap Semi"))
    )
    (comp (ref "C_220_36")
      (value "(OPT)220uF")
      (footprint "SMD_1210_CAPC3225X279N")
      (description "CL32A227MQVNNNE 220UF 6.3V 20% X5R 1210")
      (fields (field (name "PUBLISHER") "Altium Limited"))
      (libsource (lib "Miscellaneous Devices") (part "Cap Semi"))
    )
    (comp (ref "C_220_37")
      (value "(OPT)220uF")
      (footprint "SMD_1210_CAPC3225X279N")
      (description "CL32A227MQVNNNE 220UF 6.3V 20% X5R 1210")
      (fields (field (name "PUBLISHER") "Altium Limited"))
      (libsource (lib "Miscellaneous Devices") (part "Cap Semi"))
    )
    (comp (ref "C_220_38")
      (value "(OPT)220uF")
      (footprint "SMD_1210_CAPC3225X279N")
      (description "CL32A227MQVNNNE 220UF 6.3V 20% X5R 1210")
      (fields (field (name "PUBLISHER") "Altium Limited"))
      (libsource (lib "Miscellaneous Devices") (part "Cap Semi"))
    )
    (comp (ref "C_220_39")
      (value "(OPT)220uF")
      (footprint "SMD_1210_CAPC3225X279N")
      (description "CL32A227MQVNNNE 220UF 6.3V 20% X5R 1210")
      (fields (field (name "PUBLISHER") "Altium Limited"))
      (libsource (lib "Miscellaneous Devices") (part "Cap Semi"))
    )
    (comp (ref "C_220_40")
      (value "(OPT)220uF")
      (footprint "SMD_1210_CAPC3225X279N")
      (description "CL32A227MQVNNNE 220UF 6.3V 20% X5R 1210")
      (fields (field (name "PUBLISHER") "Altium Limited"))
      (libsource (lib "Miscellaneous Devices") (part "Cap Semi"))
    )
    (comp (ref "C_220_41")
      (value "(OPT)220uF")
      (footprint "SMD_1210_CAPC3225X279N")
      (description "CL32A227MQVNNNE 220UF 6.3V 20% X5R 1210")
      (fields (field (name "PUBLISHER") "Altium Limited"))
      (libsource (lib "Miscellaneous Devices") (part "Cap Semi"))
    )
    (comp (ref "C_220_42")
      (value "(OPT)220uF")
      (footprint "SMD_1210_CAPC3225X279N")
      (description "CL32A227MQVNNNE 220UF 6.3V 20% X5R 1210")
      (fields (field (name "PUBLISHER") "Altium Limited"))
      (libsource (lib "Miscellaneous Devices") (part "Cap Semi"))
    )
    (comp (ref "C_220_43")
      (value "(OPT)220uF")
      (footprint "SMD_1210_CAPC3225X279N")
      (description "CL32A227MQVNNNE 220UF 6.3V 20% X5R 1210")
      (fields (field (name "PUBLISHER") "Altium Limited"))
      (libsource (lib "Miscellaneous Devices") (part "Cap Semi"))
    )
    (comp (ref "C_220_44")
      (value "(OPT)220uF")
      (footprint "SMD_1210_CAPC3225X279N")
      (description "CL32A227MQVNNNE 220UF 6.3V 20% X5R 1210")
      (fields (field (name "PUBLISHER") "Altium Limited"))
      (libsource (lib "Miscellaneous Devices") (part "Cap Semi"))
    )
    (comp (ref "C_220_45")
      (value "(OPT)220uF")
      (footprint "SMD_1210_CAPC3225X279N")
      (description "CL32A227MQVNNNE 220UF 6.3V 20% X5R 1210")
      (fields (field (name "PUBLISHER") "Altium Limited"))
      (libsource (lib "Miscellaneous Devices") (part "Cap Semi"))
    )
    (comp (ref "C_220_46")
      (value "(OPT)220uF")
      (footprint "SMD_1210_CAPC3225X279N")
      (description "CL32A227MQVNNNE 220UF 6.3V 20% X5R 1210")
      (fields (field (name "PUBLISHER") "Altium Limited"))
      (libsource (lib "Miscellaneous Devices") (part "Cap Semi"))
    )
    (comp (ref "C_220_47")
      (value "(OPT)220uF")
      (footprint "SMD_1210_CAPC3225X279N")
      (description "CL32A227MQVNNNE 220UF 6.3V 20% X5R 1210")
      (fields (field (name "PUBLISHER") "Altium Limited"))
      (libsource (lib "Miscellaneous Devices") (part "Cap Semi"))
    )
    (comp (ref "C_220_48")
      (value "(OPT)220uF")
      (footprint "SMD_1210_CAPC3225X279N")
      (description "CL32A227MQVNNNE 220UF 6.3V 20% X5R 1210")
      (fields (field (name "PUBLISHER") "Altium Limited"))
      (libsource (lib "Miscellaneous Devices") (part "Cap Semi"))
    )
    (comp (ref "C_220_49")
      (value "(OPT)220uF")
      (footprint "SMD_1210_CAPC3225X279N")
      (description "CL32A227MQVNNNE 220UF 6.3V 20% X5R 1210")
      (fields (field (name "PUBLISHER") "Altium Limited"))
      (libsource (lib "Miscellaneous Devices") (part "Cap Semi"))
    )
    (comp (ref "C_220_50")
      (value "(OPT)220uF")
      (footprint "SMD_1210_CAPC3225X279N")
      (description "CL32A227MQVNNNE 220UF 6.3V 20% X5R 1210")
      (fields (field (name "PUBLISHER") "Altium Limited"))
      (libsource (lib "Miscellaneous Devices") (part "Cap Semi"))
    )
    (comp (ref "C_220_51")
      (value "(OPT)220uF")
      (footprint "SMD_1210_CAPC3225X279N")
      (description "CL32A227MQVNNNE 220UF 6.3V 20% X5R 1210")
      (fields (field (name "PUBLISHER") "Altium Limited"))
      (libsource (lib "Miscellaneous Devices") (part "Cap Semi"))
    )
    (comp (ref "C_220_52")
      (value "(OPT)220uF")
      (footprint "SMD_1210_CAPC3225X279N")
      (description "CL32A227MQVNNNE 220UF 6.3V 20% X5R 1210")
      (fields (field (name "PUBLISHER") "Altium Limited"))
      (libsource (lib "Miscellaneous Devices") (part "Cap Semi"))
    )
    (comp (ref "C_220_53")
      (value "(OPT)220uF")
      (footprint "SMD_1210_CAPC3225X279N")
      (description "CL32A227MQVNNNE 220UF 6.3V 20% X5R 1210")
      (fields (field (name "PUBLISHER") "Altium Limited"))
      (libsource (lib "Miscellaneous Devices") (part "Cap Semi"))
    )
    (comp (ref "C_220_54")
      (value "(OPT)220uF")
      (footprint "SMD_1210_CAPC3225X279N")
      (description "CL32A227MQVNNNE 220UF 6.3V 20% X5R 1210")
      (fields (field (name "PUBLISHER") "Altium Limited"))
      (libsource (lib "Miscellaneous Devices") (part "Cap Semi"))
    )
    (comp (ref "C_220_55")
      (value "(OPT)220uF")
      (footprint "SMD_1210_CAPC3225X279N")
      (description "CL32A227MQVNNNE 220UF 6.3V 20% X5R 1210")
      (fields (field (name "PUBLISHER") "Altium Limited"))
      (libsource (lib "Miscellaneous Devices") (part "Cap Semi"))
    )
    (comp (ref "C_220_56")
      (value "(OPT)220uF")
      (footprint "SMD_1210_CAPC3225X279N")
      (description "CL32A227MQVNNNE 220UF 6.3V 20% X5R 1210")
      (fields (field (name "PUBLISHER") "Altium Limited"))
      (libsource (lib "Miscellaneous Devices") (part "Cap Semi"))
    )
    (comp (ref "C_220_57")
      (value "(OPT)220uF")
      (footprint "SMD_1210_CAPC3225X279N")
      (description "CL32A227MQVNNNE 220UF 6.3V 20% X5R 1210")
      (fields (field (name "PUBLISHER") "Altium Limited"))
      (libsource (lib "Miscellaneous Devices") (part "Cap Semi"))
    )
    (comp (ref "C_220_58")
      (value "(OPT)220uF")
      (footprint "SMD_1210_CAPC3225X279N")
      (description "CL32A227MQVNNNE 220UF 6.3V 20% X5R 1210")
      (fields (field (name "PUBLISHER") "Altium Limited"))
      (libsource (lib "Miscellaneous Devices") (part "Cap Semi"))
    )
    (comp (ref "C_220_59")
      (value "(OPT)220uF")
      (footprint "SMD_1210_CAPC3225X279N")
      (description "CL32A227MQVNNNE 220UF 6.3V 20% X5R 1210")
      (fields (field (name "PUBLISHER") "Altium Limited"))
      (libsource (lib "Miscellaneous Devices") (part "Cap Semi"))
    )
    (comp (ref "C_220_60")
      (value "(OPT)220uF")
      (footprint "SMD_1210_CAPC3225X279N")
      (description "CL32A227MQVNNNE 220UF 6.3V 20% X5R 1210")
      (fields (field (name "PUBLISHER") "Altium Limited"))
      (libsource (lib "Miscellaneous Devices") (part "Cap Semi"))
    )
    (comp (ref "C_220_61")
      (value "(OPT)220uF")
      (footprint "SMD_1210_CAPC3225X279N")
      (description "CL32A227MQVNNNE 220UF 6.3V 20% X5R 1210")
      (fields (field (name "PUBLISHER") "Altium Limited"))
      (libsource (lib "Miscellaneous Devices") (part "Cap Semi"))
    )
    (comp (ref "C_220_62")
      (value "(OPT)220uF")
      (footprint "SMD_1210_CAPC3225X279N")
      (description "CL32A227MQVNNNE 220UF 6.3V 20% X5R 1210")
      (fields (field (name "PUBLISHER") "Altium Limited"))
      (libsource (lib "Miscellaneous Devices") (part "Cap Semi"))
    )
    (comp (ref "C_220_63")
      (value "(OPT)220uF")
      (footprint "SMD_1210_CAPC3225X279N")
      (description "CL32A227MQVNNNE 220UF 6.3V 20% X5R 1210")
      (fields (field (name "PUBLISHER") "Altium Limited"))
      (libsource (lib "Miscellaneous Devices") (part "Cap Semi"))
    )
    (comp (ref "C_220_64")
      (value "(OPT)220uF")
      (footprint "SMD_1210_CAPC3225X279N")
      (description "CL32A227MQVNNNE 220UF 6.3V 20% X5R 1210")
      (fields (field (name "PUBLISHER") "Altium Limited"))
      (libsource (lib "Miscellaneous Devices") (part "Cap Semi"))
    )
    (comp (ref "C_220_65")
      (value "(OPT)220uF")
      (footprint "SMD_1210_CAPC3225X279N")
      (description "CL32A227MQVNNNE 220UF 6.3V 20% X5R 1210")
      (fields (field (name "PUBLISHER") "Altium Limited"))
      (libsource (lib "Miscellaneous Devices") (part "Cap Semi"))
    )
    (comp (ref "C_220_66")
      (value "(OPT)220uF")
      (footprint "SMD_1210_CAPC3225X279N")
      (description "CL32A227MQVNNNE 220UF 6.3V 20% X5R 1210")
      (fields (field (name "PUBLISHER") "Altium Limited"))
      (libsource (lib "Miscellaneous Devices") (part "Cap Semi"))
    )
    (comp (ref "C_220_67")
      (value "(OPT)220uF")
      (footprint "SMD_1210_CAPC3225X279N")
      (description "CL32A227MQVNNNE 220UF 6.3V 20% X5R 1210")
      (fields (field (name "PUBLISHER") "Altium Limited"))
      (libsource (lib "Miscellaneous Devices") (part "Cap Semi"))
    )
    (comp (ref "C_220_68")
      (value "(OPT)220uF")
      (footprint "SMD_1210_CAPC3225X279N")
      (description "CL32A227MQVNNNE 220UF 6.3V 20% X5R 1210")
      (fields (field (name "PUBLISHER") "Altium Limited"))
      (libsource (lib "Miscellaneous Devices") (part "Cap Semi"))
    )
    (comp (ref "C_220_69")
      (value "(OPT)220uF")
      (footprint "SMD_1210_CAPC3225X279N")
      (description "CL32A227MQVNNNE 220UF 6.3V 20% X5R 1210")
      (fields (field (name "PUBLISHER") "Altium Limited"))
      (libsource (lib "Miscellaneous Devices") (part "Cap Semi"))
    )
    (comp (ref "C_220_70")
      (value "(OPT)220uF")
      (footprint "SMD_1210_CAPC3225X279N")
      (description "CL32A227MQVNNNE 220UF 6.3V 20% X5R 1210")
      (fields (field (name "PUBLISHER") "Altium Limited"))
      (libsource (lib "Miscellaneous Devices") (part "Cap Semi"))
    )
    (comp (ref "C_220_71")
      (value "(OPT)220uF")
      (footprint "SMD_1210_CAPC3225X279N")
      (description "CL32A227MQVNNNE 220UF 6.3V 20% X5R 1210")
      (fields (field (name "PUBLISHER") "Altium Limited"))
      (libsource (lib "Miscellaneous Devices") (part "Cap Semi"))
    )
    (comp (ref "C_220_73")
      (value "(OPT)220uF")
      (footprint "SMD_1210_CAPC3225X279N")
      (description "CL32A227MQVNNNE 220UF 6.3V 20% X5R 1210")
      (fields (field (name "PUBLISHER") "Altium Limited"))
      (libsource (lib "Miscellaneous Devices") (part "Cap Semi"))
    )
    (comp (ref "D1")
      (value "Red SML210VT ROHM")
      (footprint "SMD_0805_LED2012X100N")
      (libsource (lib "EPIQ_DND_CIS_Library") (part "LED_2"))
    )
    (comp (ref "D1P_1")
      (value "BAT54C")
      (footprint "SMD_SOT23_SOT95P240X120-3N")
      (libsource (lib "EPIQ_DND_CIS_Library") (part "D_DUAL_A1A2CC3"))
    )
    (comp (ref "D1P_2")
      (value "BAT54C")
      (footprint "SMD_SOT23_SOT95P240X120-3N")
      (libsource (lib "EPIQ_DND_CIS_Library") (part "D_DUAL_A1A2CC3"))
    )
    (comp (ref "D1P_3")
      (value "BAT54C")
      (footprint "SMD_SOT23_SOT95P240X120-3N")
      (libsource (lib "EPIQ_DND_CIS_Library") (part "D_DUAL_A1A2CC3"))
    )
    (comp (ref "D2")
      (value "Green 	SML210MT ROHM")
      (footprint "SMD_0805_LED2012X100N")
      (libsource (lib "EPIQ_DND_CIS_Library") (part "LED_2"))
    )
    (comp (ref "D3")
      (value "Yellow SML210YT ROHM")
      (footprint "SMD_0805_LED2012X100N")
      (libsource (lib "EPIQ_DND_CIS_Library") (part "LED_2"))
    )
    (comp (ref "D4")
      (value "Orange 	SML210DT ROHM")
      (footprint "SMD_0805_LED2012X100N")
      (libsource (lib "EPIQ_DND_CIS_Library") (part "LED_2"))
    )
    (comp (ref "D5")
      (value "SMS05T1G")
      (footprint "SMD_SOT95P280X145-6N-W")
      (description "4 IO lines TVS")
      (libsource (lib "BitCoin") (part "D_TVS_QUAD_C1AA2AA5C3C4C6"))
    )
    (comp (ref "D7")
      (value "(OPT)SS14")
      (footprint "SMD_DO214AC_SMA")
      (libsource (lib "BitCoin") (part "D_STKY"))
    )
    (comp (ref "D8")
      (value "(OPT)SS14")
      (footprint "SMD_DO214AC_SMA")
      (libsource (lib "BitCoin") (part "D_STKY"))
    )
    (comp (ref "D9") (value "SS14") (footprint "SMD_DO214AC_SMA") (libsource (lib "BitCoin") (part "D_STKY")))
    (comp (ref "D10")
      (value "SMCJ12A")
      (footprint "SMD_DO214AC_SMC")
      (description "Еднопосочен трансил, 600W, UBRmin13.3V@1mA")
      (libsource (lib "BitCoin") (part "D_TVS_UNI"))
    )
    (comp (ref "J1")
      (value "(OPT) CON PROGRAM")
      (footprint "SIP5 PGM TOP")
      (description "Connector")
      (libsource (lib "Miscellaneous Devices") (part "CON5"))
    )
    (comp (ref "J2")
      (value "CU04SCM15B0-R0")
      (footprint "SMD_CON-CVILUX-CU04-SCM15B0")
      (libsource (lib "EPIQ_DND_CIS_Library") (part "CON_USB_MINI_1"))
    )
    (comp (ref "J3")
      (value "CON_3PINS")
      (footprint "PTH_CON_3.5mm_3PINs")
      (libsource (lib "EPIQ_DND_CIS_Library") (part "CON_3PINS"))
    )
    (comp (ref "J4")
      (value "WURTH 649 006 295 22")
      (footprint "PTH_CON_PCI-E")
      (description "4.20mm Male Dual Row Angled Header WR-MPC4")
      (libsource (lib "BitCoin") (part "CON_PCI-E"))
    )
    (comp (ref "L1P_1")
      (value "SLC1480-201MLD")
      (footprint "SMD_INDM12501250X800A - Coilcraft SLC1480")
      (libsource (lib "EPIQ_DND_CIS_Library") (part "L"))
    )
    (comp (ref "L1P_2")
      (value "SLC1480-201MLD")
      (footprint "SMD_INDM12501250X800A - Coilcraft SLC1480")
      (libsource (lib "EPIQ_DND_CIS_Library") (part "L"))
    )
    (comp (ref "L1P_3")
      (value "SLC1480-201MLD")
      (footprint "SMD_INDM12501250X800A - Coilcraft SLC1480")
      (libsource (lib "EPIQ_DND_CIS_Library") (part "L"))
    )
    (comp (ref "Q1")
      (value "BSS138")
      (footprint "SMD_SOT23_SOT95P240X120-3N")
      (libsource (lib "EPIQ_DND_CIS_Library") (part "BJT_NPN_B1E2C3"))
    )
    (comp (ref "Q1P_1")
      (value "AP1RA03GMT-3")
      (footprint "SMD_SON127P615X520X100-8N")
      (libsource (lib "EPIQ_DND_CIS_Library") (part "MOS_N_D1_S1S2S3G4D5D6D7D8"))
    )
    (comp (ref "Q1P_2")
      (value "AP1RA03GMT-3")
      (footprint "SMD_SON127P615X520X100-8N")
      (libsource (lib "EPIQ_DND_CIS_Library") (part "MOS_N_D1_S1S2S3G4D5D6D7D8"))
    )
    (comp (ref "Q1P_3")
      (value "AP1RA03GMT-3")
      (footprint "SMD_SON127P615X520X100-8N")
      (libsource (lib "EPIQ_DND_CIS_Library") (part "MOS_N_D1_S1S2S3G4D5D6D7D8"))
    )
    (comp (ref "Q2P_1")
      (value "AP1RA03GMT-3")
      (footprint "SMD_SON127P615X520X100-8N")
      (libsource (lib "EPIQ_DND_CIS_Library") (part "MOS_N_D1_S1S2S3G4D5D6D7D8"))
    )
    (comp (ref "Q2P_2")
      (value "AP1RA03GMT-3")
      (footprint "SMD_SON127P615X520X100-8N")
      (libsource (lib "EPIQ_DND_CIS_Library") (part "MOS_N_D1_S1S2S3G4D5D6D7D8"))
    )
    (comp (ref "Q2P_3")
      (value "AP1RA03GMT-3")
      (footprint "SMD_SON127P615X520X100-8N")
      (libsource (lib "EPIQ_DND_CIS_Library") (part "MOS_N_D1_S1S2S3G4D5D6D7D8"))
    )
    (comp (ref "Q3P_1")
      (value "AP1RA03GMT-3")
      (footprint "SMD_SON127P615X520X100-8N")
      (libsource (lib "EPIQ_DND_CIS_Library") (part "MOS_N_D1_S1S2S3G4D5D6D7D8"))
    )
    (comp (ref "Q3P_2")
      (value "AP1RA03GMT-3")
      (footprint "SMD_SON127P615X520X100-8N")
      (libsource (lib "EPIQ_DND_CIS_Library") (part "MOS_N_D1_S1S2S3G4D5D6D7D8"))
    )
    (comp (ref "Q3P_3")
      (value "AP1RA03GMT-3")
      (footprint "SMD_SON127P615X520X100-8N")
      (libsource (lib "EPIQ_DND_CIS_Library") (part "MOS_N_D1_S1S2S3G4D5D6D7D8"))
    )
    (comp (ref "R1")
      (value "1k")
      (footprint "SMD_0603_RESC1608X55N")
      (description "Resistor")
      (fields (field (name "PUBLISHER") "Altium Limited"))
      (libsource (lib "Miscellaneous Devices") (part "Res3"))
    )
    (comp (ref "R3")
      (value "1k")
      (footprint "SMD_0603_RESC1608X55N")
      (description "Resistor")
      (fields (field (name "PUBLISHER") "Altium Limited"))
      (libsource (lib "Miscellaneous Devices") (part "Res3"))
    )
    (comp (ref "R4")
      (value "47")
      (footprint "SMD_0603_RESC1608X55N")
      (description "Resistor")
      (fields (field (name "PUBLISHER") "Altium Limited"))
      (libsource (lib "Miscellaneous Devices") (part "Res3"))
    )
    (comp (ref "R5")
      (value "47")
      (footprint "SMD_0603_RESC1608X55N")
      (description "Resistor")
      (fields (field (name "PUBLISHER") "Altium Limited"))
      (libsource (lib "Miscellaneous Devices") (part "Res3"))
    )
    (comp (ref "R6")
      (value "1k")
      (footprint "SMD_0603_RESC1608X55N")
      (description "Resistor")
      (fields (field (name "PUBLISHER") "Altium Limited"))
      (libsource (lib "Miscellaneous Devices") (part "Res3"))
    )
    (comp (ref "R7")
      (value "1k")
      (footprint "SMD_0603_RESC1608X55N")
      (description "Resistor")
      (fields (field (name "PUBLISHER") "Altium Limited"))
      (libsource (lib "Miscellaneous Devices") (part "Res3"))
    )
    (comp (ref "R8")
      (value "47")
      (footprint "SMD_0603_RESC1608X55N")
      (description "Resistor")
      (fields (field (name "PUBLISHER") "Altium Limited"))
      (libsource (lib "Miscellaneous Devices") (part "Res3"))
    )
    (comp (ref "R9")
      (value "10k")
      (footprint "SMD_0603_RESC1608X55N")
      (description "Resistor")
      (fields (field (name "PUBLISHER") "Altium Limited"))
      (libsource (lib "Miscellaneous Devices") (part "Res3"))
    )
    (comp (ref "R10")
      (value "10k")
      (footprint "SMD_0603_RESC1608X55N")
      (description "Resistor")
      (fields (field (name "PUBLISHER") "Altium Limited"))
      (libsource (lib "Miscellaneous Devices") (part "Res3"))
    )
    (comp (ref "R11")
      (value "10k")
      (footprint "SMD_0603_RESC1608X55N")
      (description "Resistor")
      (fields (field (name "PUBLISHER") "Altium Limited"))
      (libsource (lib "Miscellaneous Devices") (part "Res3"))
    )
    (comp (ref "R12")
      (value "10k")
      (footprint "SMD_0603_RESC1608X55N")
      (description "Resistor")
      (fields (field (name "PUBLISHER") "Altium Limited"))
      (libsource (lib "Miscellaneous Devices") (part "Res3"))
    )
    (comp (ref "R13")
      (value "1k")
      (footprint "SMD_0603_RESC1608X55N")
      (description "Resistor")
      (fields (field (name "PUBLISHER") "Altium Limited"))
      (libsource (lib "Miscellaneous Devices") (part "Res3"))
    )
    (comp (ref "R14")
      (value "47")
      (footprint "SMD_0603_RESC1608X55N")
      (description "Resistor")
      (fields (field (name "PUBLISHER") "Altium Limited"))
      (libsource (lib "Miscellaneous Devices") (part "Res3"))
    )
    (comp (ref "R15")
      (value "10k")
      (footprint "SMD_0603_RESC1608X55N")
      (description "Resistor")
      (fields (field (name "PUBLISHER") "Altium Limited"))
      (libsource (lib "Miscellaneous Devices") (part "Res3"))
    )
    (comp (ref "R16")
      (value "2.4k")
      (footprint "SMD_0603_RESC1608X55N")
      (description "Resistor")
      (fields (field (name "PUBLISHER") "Altium Limited"))
      (libsource (lib "Miscellaneous Devices") (part "Res3"))
    )
    (comp (ref "R17")
      (value "0")
      (footprint "SMD_0603_RESC1608X55N")
      (description "Resistor")
      (fields (field (name "PUBLISHER") "Altium Limited"))
      (libsource (lib "Miscellaneous Devices") (part "Res3"))
    )
    (comp (ref "R18")
      (value "10k")
      (footprint "SMD_0603_RESC1608X55N")
      (description "Resistor")
      (fields (field (name "PUBLISHER") "Altium Limited"))
      (libsource (lib "Miscellaneous Devices") (part "Res3"))
    )
    (comp (ref "R19")
      (value "(OPT)10k")
      (footprint "SMD_0603_RESC1608X55N")
      (description "Resistor")
      (fields (field (name "PUBLISHER") "Altium Limited"))
      (libsource (lib "Miscellaneous Devices") (part "Res3"))
    )
    (comp (ref "R20")
      (value "10k")
      (footprint "SMD_0603_RESC1608X55N")
      (description "Resistor")
      (fields (field (name "PUBLISHER") "Altium Limited"))
      (libsource (lib "Miscellaneous Devices") (part "Res3"))
    )
    (comp (ref "R21")
      (value "10k")
      (footprint "SMD_0603_RESC1608X55N")
      (description "Resistor")
      (fields (field (name "PUBLISHER") "Altium Limited"))
      (libsource (lib "Miscellaneous Devices") (part "Res3"))
    )
    (comp (ref "R22")
      (value "10k")
      (footprint "SMD_0603_RESC1608X55N")
      (description "Resistor")
      (fields (field (name "PUBLISHER") "Altium Limited"))
      (libsource (lib "Miscellaneous Devices") (part "Res3"))
    )
    (comp (ref "R23")
      (value "10k")
      (footprint "SMD_0603_RESC1608X55N")
      (description "Resistor")
      (fields (field (name "PUBLISHER") "Altium Limited"))
      (libsource (lib "Miscellaneous Devices") (part "Res3"))
    )
    (comp (ref "R25")
      (value "0")
      (footprint "SMD_0603_RESC1608X55N")
      (description "Resistor")
      (fields (field (name "PUBLISHER") "Altium Limited"))
      (libsource (lib "Miscellaneous Devices") (part "Res3"))
    )
    (comp (ref "R26")
      (value "2")
      (footprint "SMD_1206_RESC3216X180N")
      (description "Resistor")
      (fields (field (name "PUBLISHER") "Altium Limited"))
      (libsource (lib "Miscellaneous Devices") (part "Res3"))
    )
    (comp (ref "R27")
      (value "(OPT)0")
      (footprint "SMD_0603_RESC1608X55N")
      (description "Resistor")
      (fields (field (name "PUBLISHER") "Altium Limited"))
      (libsource (lib "Miscellaneous Devices") (part "Res3"))
    )
    (comp (ref "R28")
      (value "100")
      (footprint "SMD_1206_RESC3216X180N")
      (description "Resistor")
      (fields (field (name "PUBLISHER") "Altium Limited"))
      (libsource (lib "Miscellaneous Devices") (part "Res3"))
    )
    (comp (ref "R29")
      (value "20")
      (footprint "SMD_0603_RESC1608X55N")
      (description "Resistor")
      (fields (field (name "PUBLISHER") "Altium Limited"))
      (libsource (lib "Miscellaneous Devices") (part "Res3"))
    )
    (comp (ref "R30")
      (value "0")
      (footprint "SMD_0603_RESC1608X55N")
      (description "Resistor")
      (fields (field (name "PUBLISHER") "Altium Limited"))
      (libsource (lib "Miscellaneous Devices") (part "Res3"))
    )
    (comp (ref "R31")
      (value "20")
      (footprint "SMD_0603_RESC1608X55N")
      (description "Resistor")
      (fields (field (name "PUBLISHER") "Altium Limited"))
      (libsource (lib "Miscellaneous Devices") (part "Res3"))
    )
    (comp (ref "U1")
      (value "dsPIC33EP256MU806")
      (footprint "SMD_QFP50P1200X1200X120-64N")
      (libsource (lib "MCU") (part "dsPIC33EP256MU806"))
    )
    (comp (ref "U1P_1")
      (value "LTC 4449")
      (footprint "SMD_DFN16166SON50P161X161X60-9N - LTC4449")
      (description "Mosfet 12V Dual Bootstrapped PWM Sync Buck Optimised")
      (libsource (lib "Devices") (part "DRVFET_LTC4442"))
    )
    (comp (ref "U1P_2")
      (value "LTC 4449")
      (footprint "SMD_DFN16166SON50P161X161X60-9N - LTC4449")
      (description "Mosfet 12V Dual Bootstrapped PWM Sync Buck Optimised")
      (libsource (lib "Devices") (part "DRVFET_LTC4442"))
    )
    (comp (ref "U1P_3")
      (value "LTC 4449")
      (footprint "SMD_DFN16166SON50P161X161X60-9N - LTC4449")
      (description "Mosfet 12V Dual Bootstrapped PWM Sync Buck Optimised")
      (libsource (lib "Devices") (part "DRVFET_LTC4442"))
    )
    (comp (ref "U1_1")
      (value "Hammer")
      (footprint "SMD_QFN50P800X800X80-69N - HAMMER")
      (description "Hammer ASIC")
      (libsource (lib "DevicesA10") (part "HammerQ68"))
    )
    (comp (ref "U1_2")
      (value "Hammer")
      (footprint "SMD_QFN50P800X800X80-69N - HAMMER")
      (description "Hammer ASIC")
      (libsource (lib "DevicesA10") (part "HammerQ68"))
    )
    (comp (ref "U1_3")
      (value "Hammer")
      (footprint "SMD_QFN50P800X800X80-69N - HAMMER")
      (description "Hammer ASIC")
      (libsource (lib "DevicesA10") (part "HammerQ68"))
    )
    (comp (ref "U1_4")
      (value "Hammer")
      (footprint "SMD_QFN50P800X800X80-69N - HAMMER")
      (description "Hammer ASIC")
      (libsource (lib "DevicesA10") (part "HammerQ68"))
    )
    (comp (ref "U1_5")
      (value "Hammer")
      (footprint "SMD_QFN50P800X800X80-69N - HAMMER")
      (description "Hammer ASIC")
      (libsource (lib "DevicesA10") (part "HammerQ68"))
    )
    (comp (ref "U1_6")
      (value "Hammer")
      (footprint "SMD_QFN50P800X800X80-69N - HAMMER")
      (description "Hammer ASIC")
      (libsource (lib "DevicesA10") (part "HammerQ68"))
    )
    (comp (ref "U1_7")
      (value "Hammer")
      (footprint "SMD_QFN50P800X800X80-69N - HAMMER")
      (description "Hammer ASIC")
      (libsource (lib "DevicesA10") (part "HammerQ68"))
    )
    (comp (ref "U1_8")
      (value "Hammer")
      (footprint "SMD_QFN50P800X800X80-69N - HAMMER")
      (description "Hammer ASIC")
      (libsource (lib "DevicesA10") (part "HammerQ68"))
    )
    (comp (ref "U1_9")
      (value "Hammer")
      (footprint "SMD_QFN50P800X800X80-69N - HAMMER")
      (description "Hammer ASIC")
      (libsource (lib "DevicesA10") (part "HammerQ68"))
    )
    (comp (ref "U1_10")
      (value "Hammer")
      (footprint "SMD_QFN50P800X800X80-69N - HAMMER")
      (description "Hammer ASIC")
      (libsource (lib "DevicesA10") (part "HammerQ68"))
    )
    (comp (ref "U1_11")
      (value "Hammer")
      (footprint "SMD_QFN50P800X800X80-69N - HAMMER")
      (description "Hammer ASIC")
      (libsource (lib "DevicesA10") (part "HammerQ68"))
    )
    (comp (ref "U1_12")
      (value "Hammer")
      (footprint "SMD_QFN50P800X800X80-69N - HAMMER")
      (description "Hammer ASIC")
      (libsource (lib "DevicesA10") (part "HammerQ68"))
    )
    (comp (ref "U1_13")
      (value "Hammer")
      (footprint "SMD_QFN50P800X800X80-69N - HAMMER")
      (description "Hammer ASIC")
      (libsource (lib "DevicesA10") (part "HammerQ68"))
    )
    (comp (ref "U1_14")
      (value "Hammer")
      (footprint "SMD_QFN50P800X800X80-69N - HAMMER")
      (description "Hammer ASIC")
      (libsource (lib "DevicesA10") (part "HammerQ68"))
    )
    (comp (ref "U1_15")
      (value "Hammer")
      (footprint "SMD_QFN50P800X800X80-69N - HAMMER")
      (description "Hammer ASIC")
      (libsource (lib "DevicesA10") (part "HammerQ68"))
    )
    (comp (ref "U1_16")
      (value "Hammer")
      (footprint "SMD_QFN50P800X800X80-69N - HAMMER")
      (description "Hammer ASIC")
      (libsource (lib "DevicesA10") (part "HammerQ68"))
    )
    (comp (ref "U2")
      (value "(OPT) LM7805")
      (footprint "SMD_SOIC127P602X173-8N")
      (libsource (lib "EPIQ_DND_CIS_Library") (part "IC_LM2931AD-5.0R2G_SO-8"))
    )
    (comp (ref "U3")
      (value "(OPT)BU33TD3WG-TR")
      (footprint "SMD_SOT26_SOT95P285X140-5N - DLV")
      (libsource (lib "Miscellaneous Devices") (part "VOLTREG LDO"))
    )
    (comp (ref "U4")
      (value "(OPT) L7805CD2T-TR")
      (footprint "SMD_TO254P1524X483-3_4N_D2PAK")
      (libsource (lib "EPIQ_DND_CIS_Library") (part "IC_Vout1GND2Vin3"))
    )
    (comp (ref "U5")
      (value "L78M05CDT-TR")
      (footprint "SMD_TO229P991X239-4AN_DPAK")
      (libsource (lib "EPIQ_DND_CIS_Library") (part "IC_Vout1GND2Vin3"))
    )
    (comp (ref "U6")
      (value "BD18KA5WF")
      (footprint "SMD_SOIC127P602X173-8N")
      (libsource (lib "EPIQ_DND_CIS_Library") (part "IC_LM2931AD-5.0R2G_SO-8"))
    )
    (comp (ref "U7")
      (value "BD33KA5WF")
      (footprint "SMD_SOIC127P602X173-8N")
      (libsource (lib "EPIQ_DND_CIS_Library") (part "IC_LM2931AD-5.0R2G_SO-8"))
    )
    (comp (ref "Y1")
      (value "Q4.000 MHz HC-49SM SMD")
      (footprint "SMD_HC49_XTAL1140X480X420N")
      (description "Crystal")
      (libsource (lib "*") (part "CRYSTAL"))
    )
  )
  (nets
    (net (code "1") (name "/0.8V") (class "Default")
      (node (ref "C10_1") (pin "2") (pinfunction "2_2") (pintype "passive"))
      (node (ref "C10_10") (pin "2") (pinfunction "2_2") (pintype "passive"))
      (node (ref "C10_11") (pin "2") (pinfunction "2_2") (pintype "passive"))
      (node (ref "C10_12") (pin "2") (pinfunction "2_2") (pintype "passive"))
      (node (ref "C10_13") (pin "2") (pinfunction "2_2") (pintype "passive"))
      (node (ref "C10_14") (pin "2") (pinfunction "2_2") (pintype "passive"))
      (node (ref "C10_15") (pin "2") (pinfunction "2_2") (pintype "passive"))
      (node (ref "C10_16") (pin "2") (pinfunction "2_2") (pintype "passive"))
      (node (ref "C10_2") (pin "2") (pinfunction "2_2") (pintype "passive"))
      (node (ref "C10_3") (pin "2") (pinfunction "2_2") (pintype "passive"))
      (node (ref "C10_4") (pin "2") (pinfunction "2_2") (pintype "passive"))
      (node (ref "C10_5") (pin "2") (pinfunction "2_2") (pintype "passive"))
      (node (ref "C10_6") (pin "2") (pinfunction "2_2") (pintype "passive"))
      (node (ref "C10_7") (pin "2") (pinfunction "2_2") (pintype "passive"))
      (node (ref "C10_8") (pin "2") (pinfunction "2_2") (pintype "passive"))
      (node (ref "C10_9") (pin "2") (pinfunction "2_2") (pintype "passive"))
      (node (ref "C11_1") (pin "2") (pinfunction "2_2") (pintype "passive"))
      (node (ref "C11_10") (pin "2") (pinfunction "2_2") (pintype "passive"))
      (node (ref "C11_11") (pin "2") (pinfunction "2_2") (pintype "passive"))
      (node (ref "C11_12") (pin "2") (pinfunction "2_2") (pintype "passive"))
      (node (ref "C11_13") (pin "2") (pinfunction "2_2") (pintype "passive"))
      (node (ref "C11_14") (pin "2") (pinfunction "2_2") (pintype "passive"))
      (node (ref "C11_15") (pin "2") (pinfunction "2_2") (pintype "passive"))
      (node (ref "C11_16") (pin "2") (pinfunction "2_2") (pintype "passive"))
      (node (ref "C11_2") (pin "2") (pinfunction "2_2") (pintype "passive"))
      (node (ref "C11_3") (pin "2") (pinfunction "2_2") (pintype "passive"))
      (node (ref "C11_4") (pin "2") (pinfunction "2_2") (pintype "passive"))
      (node (ref "C11_5") (pin "2") (pinfunction "2_2") (pintype "passive"))
      (node (ref "C11_6") (pin "2") (pinfunction "2_2") (pintype "passive"))
      (node (ref "C11_7") (pin "2") (pinfunction "2_2") (pintype "passive"))
      (node (ref "C11_8") (pin "2") (pinfunction "2_2") (pintype "passive"))
      (node (ref "C11_9") (pin "2") (pinfunction "2_2") (pintype "passive"))
      (node (ref "C12_1") (pin "2") (pinfunction "2_2") (pintype "passive"))
      (node (ref "C12_10") (pin "2") (pinfunction "2_2") (pintype "passive"))
      (node (ref "C12_11") (pin "2") (pinfunction "2_2") (pintype "passive"))
      (node (ref "C12_12") (pin "2") (pinfunction "2_2") (pintype "passive"))
      (node (ref "C12_13") (pin "2") (pinfunction "2_2") (pintype "passive"))
      (node (ref "C12_14") (pin "2") (pinfunction "2_2") (pintype "passive"))
      (node (ref "C12_15") (pin "2") (pinfunction "2_2") (pintype "passive"))
      (node (ref "C12_16") (pin "2") (pinfunction "2_2") (pintype "passive"))
      (node (ref "C12_2") (pin "2") (pinfunction "2_2") (pintype "passive"))
      (node (ref "C12_3") (pin "2") (pinfunction "2_2") (pintype "passive"))
      (node (ref "C12_4") (pin "2") (pinfunction "2_2") (pintype "passive"))
      (node (ref "C12_5") (pin "2") (pinfunction "2_2") (pintype "passive"))
      (node (ref "C12_6") (pin "2") (pinfunction "2_2") (pintype "passive"))
      (node (ref "C12_7") (pin "2") (pinfunction "2_2") (pintype "passive"))
      (node (ref "C12_8") (pin "2") (pinfunction "2_2") (pintype "passive"))
      (node (ref "C12_9") (pin "2") (pinfunction "2_2") (pintype "passive"))
      (node (ref "C13_1") (pin "2") (pinfunction "2_2") (pintype "passive"))
      (node (ref "C13_10") (pin "2") (pinfunction "2_2") (pintype "passive"))
      (node (ref "C13_11") (pin "2") (pinfunction "2_2") (pintype "passive"))
      (node (ref "C13_12") (pin "2") (pinfunction "2_2") (pintype "passive"))
      (node (ref "C13_13") (pin "2") (pinfunction "2_2") (pintype "passive"))
      (node (ref "C13_14") (pin "2") (pinfunction "2_2") (pintype "passive"))
      (node (ref "C13_15") (pin "2") (pinfunction "2_2") (pintype "passive"))
      (node (ref "C13_16") (pin "2") (pinfunction "2_2") (pintype "passive"))
      (node (ref "C13_2") (pin "2") (pinfunction "2_2") (pintype "passive"))
      (node (ref "C13_3") (pin "2") (pinfunction "2_2") (pintype "passive"))
      (node (ref "C13_4") (pin "2") (pinfunction "2_2") (pintype "passive"))
      (node (ref "C13_5") (pin "2") (pinfunction "2_2") (pintype "passive"))
      (node (ref "C13_6") (pin "2") (pinfunction "2_2") (pintype "passive"))
      (node (ref "C13_7") (pin "2") (pinfunction "2_2") (pintype "passive"))
      (node (ref "C13_8") (pin "2") (pinfunction "2_2") (pintype "passive"))
      (node (ref "C13_9") (pin "2") (pinfunction "2_2") (pintype "passive"))
      (node (ref "C14_1") (pin "2") (pinfunction "2_2") (pintype "passive"))
      (node (ref "C14_10") (pin "2") (pinfunction "2_2") (pintype "passive"))
      (node (ref "C14_11") (pin "2") (pinfunction "2_2") (pintype "passive"))
      (node (ref "C14_12") (pin "2") (pinfunction "2_2") (pintype "passive"))
      (node (ref "C14_13") (pin "2") (pinfunction "2_2") (pintype "passive"))
      (node (ref "C14_14") (pin "2") (pinfunction "2_2") (pintype "passive"))
      (node (ref "C14_15") (pin "2") (pinfunction "2_2") (pintype "passive"))
      (node (ref "C14_16") (pin "2") (pinfunction "2_2") (pintype "passive"))
      (node (ref "C14_2") (pin "2") (pinfunction "2_2") (pintype "passive"))
      (node (ref "C14_3") (pin "2") (pinfunction "2_2") (pintype "passive"))
      (node (ref "C14_4") (pin "2") (pinfunction "2_2") (pintype "passive"))
      (node (ref "C14_5") (pin "2") (pinfunction "2_2") (pintype "passive"))
      (node (ref "C14_6") (pin "2") (pinfunction "2_2") (pintype "passive"))
      (node (ref "C14_7") (pin "2") (pinfunction "2_2") (pintype "passive"))
      (node (ref "C14_8") (pin "2") (pinfunction "2_2") (pintype "passive"))
      (node (ref "C14_9") (pin "2") (pinfunction "2_2") (pintype "passive"))
      (node (ref "C15_1") (pin "2") (pinfunction "2_2") (pintype "passive"))
      (node (ref "C15_10") (pin "2") (pinfunction "2_2") (pintype "passive"))
      (node (ref "C15_11") (pin "2") (pinfunction "2_2") (pintype "passive"))
      (node (ref "C15_12") (pin "2") (pinfunction "2_2") (pintype "passive"))
      (node (ref "C15_13") (pin "2") (pinfunction "2_2") (pintype "passive"))
      (node (ref "C15_14") (pin "2") (pinfunction "2_2") (pintype "passive"))
      (node (ref "C15_15") (pin "2") (pinfunction "2_2") (pintype "passive"))
      (node (ref "C15_16") (pin "2") (pinfunction "2_2") (pintype "passive"))
      (node (ref "C15_2") (pin "2") (pinfunction "2_2") (pintype "passive"))
      (node (ref "C15_3") (pin "2") (pinfunction "2_2") (pintype "passive"))
      (node (ref "C15_4") (pin "2") (pinfunction "2_2") (pintype "passive"))
      (node (ref "C15_5") (pin "2") (pinfunction "2_2") (pintype "passive"))
      (node (ref "C15_6") (pin "2") (pinfunction "2_2") (pintype "passive"))
      (node (ref "C15_7") (pin "2") (pinfunction "2_2") (pintype "passive"))
      (node (ref "C15_8") (pin "2") (pinfunction "2_2") (pintype "passive"))
      (node (ref "C15_9") (pin "2") (pinfunction "2_2") (pintype "passive"))
      (node (ref "C16_1") (pin "2") (pinfunction "2_2") (pintype "passive"))
      (node (ref "C16_10") (pin "2") (pinfunction "2_2") (pintype "passive"))
      (node (ref "C16_11") (pin "2") (pinfunction "2_2") (pintype "passive"))
      (node (ref "C16_12") (pin "2") (pinfunction "2_2") (pintype "passive"))
      (node (ref "C16_13") (pin "2") (pinfunction "2_2") (pintype "passive"))
      (node (ref "C16_14") (pin "2") (pinfunction "2_2") (pintype "passive"))
      (node (ref "C16_15") (pin "2") (pinfunction "2_2") (pintype "passive"))
      (node (ref "C16_16") (pin "2") (pinfunction "2_2") (pintype "passive"))
      (node (ref "C16_2") (pin "2") (pinfunction "2_2") (pintype "passive"))
      (node (ref "C16_3") (pin "2") (pinfunction "2_2") (pintype "passive"))
      (node (ref "C16_4") (pin "2") (pinfunction "2_2") (pintype "passive"))
      (node (ref "C16_5") (pin "2") (pinfunction "2_2") (pintype "passive"))
      (node (ref "C16_6") (pin "2") (pinfunction "2_2") (pintype "passive"))
      (node (ref "C16_7") (pin "2") (pinfunction "2_2") (pintype "passive"))
      (node (ref "C16_8") (pin "2") (pinfunction "2_2") (pintype "passive"))
      (node (ref "C16_9") (pin "2") (pinfunction "2_2") (pintype "passive"))
      (node (ref "C1_1") (pin "2") (pinfunction "2_2") (pintype "passive"))
      (node (ref "C1_10") (pin "2") (pinfunction "2_2") (pintype "passive"))
      (node (ref "C1_11") (pin "2") (pinfunction "2_2") (pintype "passive"))
      (node (ref "C1_12") (pin "2") (pinfunction "2_2") (pintype "passive"))
      (node (ref "C1_13") (pin "2") (pinfunction "2_2") (pintype "passive"))
      (node (ref "C1_14") (pin "2") (pinfunction "2_2") (pintype "passive"))
      (node (ref "C1_15") (pin "2") (pinfunction "2_2") (pintype "passive"))
      (node (ref "C1_16") (pin "2") (pinfunction "2_2") (pintype "passive"))
      (node (ref "C1_2") (pin "2") (pinfunction "2_2") (pintype "passive"))
      (node (ref "C1_3") (pin "2") (pinfunction "2_2") (pintype "passive"))
      (node (ref "C1_4") (pin "2") (pinfunction "2_2") (pintype "passive"))
      (node (ref "C1_5") (pin "2") (pinfunction "2_2") (pintype "passive"))
      (node (ref "C1_6") (pin "2") (pinfunction "2_2") (pintype "passive"))
      (node (ref "C1_7") (pin "2") (pinfunction "2_2") (pintype "passive"))
      (node (ref "C1_8") (pin "2") (pinfunction "2_2") (pintype "passive"))
      (node (ref "C1_9") (pin "2") (pinfunction "2_2") (pintype "passive"))
      (node (ref "C2_1") (pin "2") (pinfunction "2_2") (pintype "passive"))
      (node (ref "C2_10") (pin "2") (pinfunction "2_2") (pintype "passive"))
      (node (ref "C2_11") (pin "2") (pinfunction "2_2") (pintype "passive"))
      (node (ref "C2_12") (pin "2") (pinfunction "2_2") (pintype "passive"))
      (node (ref "C2_13") (pin "2") (pinfunction "2_2") (pintype "passive"))
      (node (ref "C2_14") (pin "2") (pinfunction "2_2") (pintype "passive"))
      (node (ref "C2_15") (pin "2") (pinfunction "2_2") (pintype "passive"))
      (node (ref "C2_16") (pin "2") (pinfunction "2_2") (pintype "passive"))
      (node (ref "C2_2") (pin "2") (pinfunction "2_2") (pintype "passive"))
      (node (ref "C2_3") (pin "2") (pinfunction "2_2") (pintype "passive"))
      (node (ref "C2_4") (pin "2") (pinfunction "2_2") (pintype "passive"))
      (node (ref "C2_5") (pin "2") (pinfunction "2_2") (pintype "passive"))
      (node (ref "C2_6") (pin "2") (pinfunction "2_2") (pintype "passive"))
      (node (ref "C2_7") (pin "2") (pinfunction "2_2") (pintype "passive"))
      (node (ref "C2_8") (pin "2") (pinfunction "2_2") (pintype "passive"))
      (node (ref "C2_9") (pin "2") (pinfunction "2_2") (pintype "passive"))
      (node (ref "C3_1") (pin "2") (pinfunction "2_2") (pintype "passive"))
      (node (ref "C3_10") (pin "2") (pinfunction "2_2") (pintype "passive"))
      (node (ref "C3_11") (pin "2") (pinfunction "2_2") (pintype "passive"))
      (node (ref "C3_12") (pin "2") (pinfunction "2_2") (pintype "passive"))
      (node (ref "C3_13") (pin "2") (pinfunction "2_2") (pintype "passive"))
      (node (ref "C3_14") (pin "2") (pinfunction "2_2") (pintype "passive"))
      (node (ref "C3_15") (pin "2") (pinfunction "2_2") (pintype "passive"))
      (node (ref "C3_16") (pin "2") (pinfunction "2_2") (pintype "passive"))
      (node (ref "C3_2") (pin "2") (pinfunction "2_2") (pintype "passive"))
      (node (ref "C3_3") (pin "2") (pinfunction "2_2") (pintype "passive"))
      (node (ref "C3_4") (pin "2") (pinfunction "2_2") (pintype "passive"))
      (node (ref "C3_5") (pin "2") (pinfunction "2_2") (pintype "passive"))
      (node (ref "C3_6") (pin "2") (pinfunction "2_2") (pintype "passive"))
      (node (ref "C3_7") (pin "2") (pinfunction "2_2") (pintype "passive"))
      (node (ref "C3_8") (pin "2") (pinfunction "2_2") (pintype "passive"))
      (node (ref "C3_9") (pin "2") (pinfunction "2_2") (pintype "passive"))
      (node (ref "C4_1") (pin "2") (pinfunction "2_2") (pintype "passive"))
      (node (ref "C4_10") (pin "2") (pinfunction "2_2") (pintype "passive"))
      (node (ref "C4_11") (pin "2") (pinfunction "2_2") (pintype "passive"))
      (node (ref "C4_12") (pin "2") (pinfunction "2_2") (pintype "passive"))
      (node (ref "C4_13") (pin "2") (pinfunction "2_2") (pintype "passive"))
      (node (ref "C4_14") (pin "2") (pinfunction "2_2") (pintype "passive"))
      (node (ref "C4_15") (pin "2") (pinfunction "2_2") (pintype "passive"))
      (node (ref "C4_16") (pin "2") (pinfunction "2_2") (pintype "passive"))
      (node (ref "C4_2") (pin "2") (pinfunction "2_2") (pintype "passive"))
      (node (ref "C4_3") (pin "2") (pinfunction "2_2") (pintype "passive"))
      (node (ref "C4_4") (pin "2") (pinfunction "2_2") (pintype "passive"))
      (node (ref "C4_5") (pin "2") (pinfunction "2_2") (pintype "passive"))
      (node (ref "C4_6") (pin "2") (pinfunction "2_2") (pintype "passive"))
      (node (ref "C4_7") (pin "2") (pinfunction "2_2") (pintype "passive"))
      (node (ref "C4_8") (pin "2") (pinfunction "2_2") (pintype "passive"))
      (node (ref "C4_9") (pin "2") (pinfunction "2_2") (pintype "passive"))
      (node (ref "C5_1") (pin "2") (pinfunction "2_2") (pintype "passive"))
      (node (ref "C5_10") (pin "2") (pinfunction "2_2") (pintype "passive"))
      (node (ref "C5_11") (pin "2") (pinfunction "2_2") (pintype "passive"))
      (node (ref "C5_12") (pin "2") (pinfunction "2_2") (pintype "passive"))
      (node (ref "C5_13") (pin "2") (pinfunction "2_2") (pintype "passive"))
      (node (ref "C5_14") (pin "2") (pinfunction "2_2") (pintype "passive"))
      (node (ref "C5_15") (pin "2") (pinfunction "2_2") (pintype "passive"))
      (node (ref "C5_16") (pin "2") (pinfunction "2_2") (pintype "passive"))
      (node (ref "C5_2") (pin "2") (pinfunction "2_2") (pintype "passive"))
      (node (ref "C5_3") (pin "2") (pinfunction "2_2") (pintype "passive"))
      (node (ref "C5_4") (pin "2") (pinfunction "2_2") (pintype "passive"))
      (node (ref "C5_5") (pin "2") (pinfunction "2_2") (pintype "passive"))
      (node (ref "C5_6") (pin "2") (pinfunction "2_2") (pintype "passive"))
      (node (ref "C5_7") (pin "2") (pinfunction "2_2") (pintype "passive"))
      (node (ref "C5_8") (pin "2") (pinfunction "2_2") (pintype "passive"))
      (node (ref "C5_9") (pin "2") (pinfunction "2_2") (pintype "passive"))
      (node (ref "C6P_1") (pin "1") (pinfunction "1_1") (pintype "passive"))
      (node (ref "C6P_2") (pin "1") (pinfunction "1_1") (pintype "passive"))
      (node (ref "C6P_3") (pin "1") (pinfunction "1_1") (pintype "passive"))
      (node (ref "C6_1") (pin "2") (pinfunction "2_2") (pintype "passive"))
      (node (ref "C6_10") (pin "2") (pinfunction "2_2") (pintype "passive"))
      (node (ref "C6_11") (pin "2") (pinfunction "2_2") (pintype "passive"))
      (node (ref "C6_12") (pin "2") (pinfunction "2_2") (pintype "passive"))
      (node (ref "C6_13") (pin "2") (pinfunction "2_2") (pintype "passive"))
      (node (ref "C6_14") (pin "2") (pinfunction "2_2") (pintype "passive"))
      (node (ref "C6_15") (pin "2") (pinfunction "2_2") (pintype "passive"))
      (node (ref "C6_16") (pin "2") (pinfunction "2_2") (pintype "passive"))
      (node (ref "C6_2") (pin "2") (pinfunction "2_2") (pintype "passive"))
      (node (ref "C6_3") (pin "2") (pinfunction "2_2") (pintype "passive"))
      (node (ref "C6_4") (pin "2") (pinfunction "2_2") (pintype "passive"))
      (node (ref "C6_5") (pin "2") (pinfunction "2_2") (pintype "passive"))
      (node (ref "C6_6") (pin "2") (pinfunction "2_2") (pintype "passive"))
      (node (ref "C6_7") (pin "2") (pinfunction "2_2") (pintype "passive"))
      (node (ref "C6_8") (pin "2") (pinfunction "2_2") (pintype "passive"))
      (node (ref "C6_9") (pin "2") (pinfunction "2_2") (pintype "passive"))
      (node (ref "C7P_1") (pin "1") (pinfunction "1_1") (pintype "passive"))
      (node (ref "C7P_2") (pin "1") (pinfunction "1_1") (pintype "passive"))
      (node (ref "C7P_3") (pin "1") (pinfunction "1_1") (pintype "passive"))
      (node (ref "C7_1") (pin "2") (pinfunction "2_2") (pintype "passive"))
      (node (ref "C7_10") (pin "2") (pinfunction "2_2") (pintype "passive"))
      (node (ref "C7_11") (pin "2") (pinfunction "2_2") (pintype "passive"))
      (node (ref "C7_12") (pin "2") (pinfunction "2_2") (pintype "passive"))
      (node (ref "C7_13") (pin "2") (pinfunction "2_2") (pintype "passive"))
      (node (ref "C7_14") (pin "2") (pinfunction "2_2") (pintype "passive"))
      (node (ref "C7_15") (pin "2") (pinfunction "2_2") (pintype "passive"))
      (node (ref "C7_16") (pin "2") (pinfunction "2_2") (pintype "passive"))
      (node (ref "C7_2") (pin "2") (pinfunction "2_2") (pintype "passive"))
      (node (ref "C7_3") (pin "2") (pinfunction "2_2") (pintype "passive"))
      (node (ref "C7_4") (pin "2") (pinfunction "2_2") (pintype "passive"))
      (node (ref "C7_5") (pin "2") (pinfunction "2_2") (pintype "passive"))
      (node (ref "C7_6") (pin "2") (pinfunction "2_2") (pintype "passive"))
      (node (ref "C7_7") (pin "2") (pinfunction "2_2") (pintype "passive"))
      (node (ref "C7_8") (pin "2") (pinfunction "2_2") (pintype "passive"))
      (node (ref "C7_9") (pin "2") (pinfunction "2_2") (pintype "passive"))
      (node (ref "C8P_1") (pin "1") (pinfunction "1_1") (pintype "passive"))
      (node (ref "C8P_2") (pin "1") (pinfunction "1_1") (pintype "passive"))
      (node (ref "C8P_3") (pin "1") (pinfunction "1_1") (pintype "passive"))
      (node (ref "C8_1") (pin "2") (pinfunction "2_2") (pintype "passive"))
      (node (ref "C8_10") (pin "2") (pinfunction "2_2") (pintype "passive"))
      (node (ref "C8_11") (pin "2") (pinfunction "2_2") (pintype "passive"))
      (node (ref "C8_12") (pin "2") (pinfunction "2_2") (pintype "passive"))
      (node (ref "C8_13") (pin "2") (pinfunction "2_2") (pintype "passive"))
      (node (ref "C8_14") (pin "2") (pinfunction "2_2") (pintype "passive"))
      (node (ref "C8_15") (pin "2") (pinfunction "2_2") (pintype "passive"))
      (node (ref "C8_16") (pin "2") (pinfunction "2_2") (pintype "passive"))
      (node (ref "C8_2") (pin "2") (pinfunction "2_2") (pintype "passive"))
      (node (ref "C8_3") (pin "2") (pinfunction "2_2") (pintype "passive"))
      (node (ref "C8_4") (pin "2") (pinfunction "2_2") (pintype "passive"))
      (node (ref "C8_5") (pin "2") (pinfunction "2_2") (pintype "passive"))
      (node (ref "C8_6") (pin "2") (pinfunction "2_2") (pintype "passive"))
      (node (ref "C8_7") (pin "2") (pinfunction "2_2") (pintype "passive"))
      (node (ref "C8_8") (pin "2") (pinfunction "2_2") (pintype "passive"))
      (node (ref "C8_9") (pin "2") (pinfunction "2_2") (pintype "passive"))
      (node (ref "C9_1") (pin "2") (pinfunction "2_2") (pintype "passive"))
      (node (ref "C9_10") (pin "2") (pinfunction "2_2") (pintype "passive"))
      (node (ref "C9_11") (pin "2") (pinfunction "2_2") (pintype "passive"))
      (node (ref "C9_12") (pin "2") (pinfunction "2_2") (pintype "passive"))
      (node (ref "C9_13") (pin "2") (pinfunction "2_2") (pintype "passive"))
      (node (ref "C9_14") (pin "2") (pinfunction "2_2") (pintype "passive"))
      (node (ref "C9_15") (pin "2") (pinfunction "2_2") (pintype "passive"))
      (node (ref "C9_16") (pin "2") (pinfunction "2_2") (pintype "passive"))
      (node (ref "C9_2") (pin "2") (pinfunction "2_2") (pintype "passive"))
      (node (ref "C9_3") (pin "2") (pinfunction "2_2") (pintype "passive"))
      (node (ref "C9_4") (pin "2") (pinfunction "2_2") (pintype "passive"))
      (node (ref "C9_5") (pin "2") (pinfunction "2_2") (pintype "passive"))
      (node (ref "C9_6") (pin "2") (pinfunction "2_2") (pintype "passive"))
      (node (ref "C9_7") (pin "2") (pinfunction "2_2") (pintype "passive"))
      (node (ref "C9_8") (pin "2") (pinfunction "2_2") (pintype "passive"))
      (node (ref "C9_9") (pin "2") (pinfunction "2_2") (pintype "passive"))
      (node (ref "C_220_1") (pin "1") (pinfunction "1_1") (pintype "passive"))
      (node (ref "C_220_10") (pin "1") (pinfunction "1_1") (pintype "passive"))
      (node (ref "C_220_11") (pin "1") (pinfunction "1_1") (pintype "passive"))
      (node (ref "C_220_12") (pin "1") (pinfunction "1_1") (pintype "passive"))
      (node (ref "C_220_13") (pin "1") (pinfunction "1_1") (pintype "passive"))
      (node (ref "C_220_14") (pin "1") (pinfunction "1_1") (pintype "passive"))
      (node (ref "C_220_15") (pin "1") (pinfunction "1_1") (pintype "passive"))
      (node (ref "C_220_16") (pin "1") (pinfunction "1_1") (pintype "passive"))
      (node (ref "C_220_17") (pin "1") (pinfunction "1_1") (pintype "passive"))
      (node (ref "C_220_18") (pin "1") (pinfunction "1_1") (pintype "passive"))
      (node (ref "C_220_19") (pin "1") (pinfunction "1_1") (pintype "passive"))
      (node (ref "C_220_2") (pin "1") (pinfunction "1_1") (pintype "passive"))
      (node (ref "C_220_20") (pin "1") (pinfunction "1_1") (pintype "passive"))
      (node (ref "C_220_21") (pin "1") (pinfunction "1_1") (pintype "passive"))
      (node (ref "C_220_22") (pin "1") (pinfunction "1_1") (pintype "passive"))
      (node (ref "C_220_23") (pin "1") (pinfunction "1_1") (pintype "passive"))
      (node (ref "C_220_24") (pin "1") (pinfunction "1_1") (pintype "passive"))
      (node (ref "C_220_25") (pin "1") (pinfunction "1_1") (pintype "passive"))
      (node (ref "C_220_26") (pin "1") (pinfunction "1_1") (pintype "passive"))
      (node (ref "C_220_27") (pin "1") (pinfunction "1_1") (pintype "passive"))
      (node (ref "C_220_28") (pin "1") (pinfunction "1_1") (pintype "passive"))
      (node (ref "C_220_29") (pin "1") (pinfunction "1_1") (pintype "passive"))
      (node (ref "C_220_3") (pin "1") (pinfunction "1_1") (pintype "passive"))
      (node (ref "C_220_30") (pin "1") (pinfunction "1_1") (pintype "passive"))
      (node (ref "C_220_31") (pin "1") (pinfunction "1_1") (pintype "passive"))
      (node (ref "C_220_32") (pin "1") (pinfunction "1_1") (pintype "passive"))
      (node (ref "C_220_33") (pin "1") (pinfunction "1_1") (pintype "passive"))
      (node (ref "C_220_34") (pin "1") (pinfunction "1_1") (pintype "passive"))
      (node (ref "C_220_35") (pin "1") (pinfunction "1_1") (pintype "passive"))
      (node (ref "C_220_36") (pin "1") (pinfunction "1_1") (pintype "passive"))
      (node (ref "C_220_37") (pin "1") (pinfunction "1_1") (pintype "passive"))
      (node (ref "C_220_38") (pin "1") (pinfunction "1_1") (pintype "passive"))
      (node (ref "C_220_39") (pin "1") (pinfunction "1_1") (pintype "passive"))
      (node (ref "C_220_4") (pin "1") (pinfunction "1_1") (pintype "passive"))
      (node (ref "C_220_40") (pin "1") (pinfunction "1_1") (pintype "passive"))
      (node (ref "C_220_41") (pin "1") (pinfunction "1_1") (pintype "passive"))
      (node (ref "C_220_42") (pin "1") (pinfunction "1_1") (pintype "passive"))
      (node (ref "C_220_43") (pin "1") (pinfunction "1_1") (pintype "passive"))
      (node (ref "C_220_44") (pin "1") (pinfunction "1_1") (pintype "passive"))
      (node (ref "C_220_45") (pin "1") (pinfunction "1_1") (pintype "passive"))
      (node (ref "C_220_46") (pin "1") (pinfunction "1_1") (pintype "passive"))
      (node (ref "C_220_47") (pin "1") (pinfunction "1_1") (pintype "passive"))
      (node (ref "C_220_48") (pin "1") (pinfunction "1_1") (pintype "passive"))
      (node (ref "C_220_49") (pin "1") (pinfunction "1_1") (pintype "passive"))
      (node (ref "C_220_5") (pin "1") (pinfunction "1_1") (pintype "passive"))
      (node (ref "C_220_50") (pin "1") (pinfunction "1_1") (pintype "passive"))
      (node (ref "C_220_51") (pin "1") (pinfunction "1_1") (pintype "passive"))
      (node (ref "C_220_52") (pin "1") (pinfunction "1_1") (pintype "passive"))
      (node (ref "C_220_53") (pin "1") (pinfunction "1_1") (pintype "passive"))
      (node (ref "C_220_54") (pin "1") (pinfunction "1_1") (pintype "passive"))
      (node (ref "C_220_55") (pin "1") (pinfunction "1_1") (pintype "passive"))
      (node (ref "C_220_56") (pin "1") (pinfunction "1_1") (pintype "passive"))
      (node (ref "C_220_57") (pin "1") (pinfunction "1_1") (pintype "passive"))
      (node (ref "C_220_58") (pin "1") (pinfunction "1_1") (pintype "passive"))
      (node (ref "C_220_59") (pin "1") (pinfunction "1_1") (pintype "passive"))
      (node (ref "C_220_6") (pin "1") (pinfunction "1_1") (pintype "passive"))
      (node (ref "C_220_60") (pin "1") (pinfunction "1_1") (pintype "passive"))
      (node (ref "C_220_61") (pin "1") (pinfunction "1_1") (pintype "passive"))
      (node (ref "C_220_62") (pin "1") (pinfunction "1_1") (pintype "passive"))
      (node (ref "C_220_63") (pin "1") (pinfunction "1_1") (pintype "passive"))
      (node (ref "C_220_64") (pin "1") (pinfunction "1_1") (pintype "passive"))
      (node (ref "C_220_65") (pin "1") (pinfunction "1_1") (pintype "passive"))
      (node (ref "C_220_66") (pin "1") (pinfunction "1_1") (pintype "passive"))
      (node (ref "C_220_67") (pin "1") (pinfunction "1_1") (pintype "passive"))
      (node (ref "C_220_68") (pin "1") (pinfunction "1_1") (pintype "passive"))
      (node (ref "C_220_69") (pin "1") (pinfunction "1_1") (pintype "passive"))
      (node (ref "C_220_7") (pin "1") (pinfunction "1_1") (pintype "passive"))
      (node (ref "C_220_70") (pin "1") (pinfunction "1_1") (pintype "passive"))
      (node (ref "C_220_71") (pin "1") (pinfunction "1_1") (pintype "passive"))
      (node (ref "C_220_73") (pin "1") (pinfunction "1_1") (pintype "passive"))
      (node (ref "C_220_8") (pin "1") (pinfunction "1_1") (pintype "passive"))
      (node (ref "C_220_9") (pin "1") (pinfunction "1_1") (pintype "passive"))
      (node (ref "L1P_1") (pin "2") (pinfunction "2_2") (pintype "passive"))
      (node (ref "L1P_2") (pin "2") (pinfunction "2_2") (pintype "passive"))
      (node (ref "L1P_3") (pin "2") (pinfunction "2_2") (pintype "passive"))
      (node (ref "R18") (pin "2") (pinfunction "2_2") (pintype "passive"))
      (node (ref "R20") (pin "2") (pinfunction "2_2") (pintype "passive"))
      (node (ref "R21") (pin "2") (pinfunction "2_2") (pintype "passive"))
      (node (ref "U1_1") (pin "1") (pinfunction "VDDC1_1") (pintype "passive"))
      (node (ref "U1_1") (pin "14") (pinfunction "VDDC14_14") (pintype "passive"))
      (node (ref "U1_1") (pin "15") (pinfunction "VDDC15_15") (pintype "passive"))
      (node (ref "U1_1") (pin "16") (pinfunction "VDDC16_16") (pintype "passive"))
      (node (ref "U1_1") (pin "17") (pinfunction "VDDC17_17") (pintype "passive"))
      (node (ref "U1_1") (pin "18") (pinfunction "VDDC18_18") (pintype "passive"))
      (node (ref "U1_1") (pin "19") (pinfunction "VDDC19_19") (pintype "passive"))
      (node (ref "U1_1") (pin "2") (pinfunction "VDDC2_2") (pintype "passive"))
      (node (ref "U1_1") (pin "20") (pinfunction "VDDC20_20") (pintype "passive"))
      (node (ref "U1_1") (pin "21") (pinfunction "VDDC21_21") (pintype "passive"))
      (node (ref "U1_1") (pin "22") (pinfunction "VDDC22_22") (pintype "passive"))
      (node (ref "U1_1") (pin "23") (pinfunction "VDDC23_23") (pintype "passive"))
      (node (ref "U1_1") (pin "24") (pinfunction "VDDC24_24") (pintype "passive"))
      (node (ref "U1_1") (pin "25") (pinfunction "VDDC25_25") (pintype "passive"))
      (node (ref "U1_1") (pin "26") (pinfunction "VDDC26_26") (pintype "passive"))
      (node (ref "U1_1") (pin "27") (pinfunction "VDDC27_27") (pintype "passive"))
      (node (ref "U1_1") (pin "28") (pinfunction "VDDC28_28") (pintype "passive"))
      (node (ref "U1_1") (pin "29") (pinfunction "VDDC29_29") (pintype "passive"))
      (node (ref "U1_1") (pin "3") (pinfunction "VDDC3_3") (pintype "passive"))
      (node (ref "U1_1") (pin "30") (pinfunction "VDDC30_30") (pintype "passive"))
      (node (ref "U1_1") (pin "31") (pinfunction "VDDC31_31") (pintype "passive"))
      (node (ref "U1_1") (pin "32") (pinfunction "VDDC32_32") (pintype "passive"))
      (node (ref "U1_1") (pin "33") (pinfunction "VDDC33_33") (pintype "passive"))
      (node (ref "U1_1") (pin "34") (pinfunction "VDDC34_34") (pintype "passive"))
      (node (ref "U1_1") (pin "35") (pinfunction "VDDC35_35") (pintype "passive"))
      (node (ref "U1_1") (pin "36") (pinfunction "VDDC36_36") (pintype "passive"))
      (node (ref "U1_1") (pin "37") (pinfunction "VDDC37_37") (pintype "passive"))
      (node (ref "U1_1") (pin "38") (pinfunction "VDDC38_38") (pintype "passive"))
      (node (ref "U1_1") (pin "4") (pinfunction "VDDC4_4") (pintype "passive"))
      (node (ref "U1_1") (pin "45") (pinfunction "VDDC45_45") (pintype "passive"))
      (node (ref "U1_1") (pin "46") (pinfunction "VDDC46_46") (pintype "passive"))
      (node (ref "U1_1") (pin "47") (pinfunction "VDDC47_47") (pintype "passive"))
      (node (ref "U1_1") (pin "48") (pinfunction "VDDC48_48") (pintype "passive"))
      (node (ref "U1_1") (pin "49") (pinfunction "VDDC49_49") (pintype "passive"))
      (node (ref "U1_1") (pin "5") (pinfunction "VDDC5_5") (pintype "passive"))
      (node (ref "U1_1") (pin "50") (pinfunction "VDDC50_50") (pintype "passive"))
      (node (ref "U1_1") (pin "51") (pinfunction "VDDC51_51") (pintype "passive"))
      (node (ref "U1_1") (pin "52") (pinfunction "VDDC52_52") (pintype "passive"))
      (node (ref "U1_1") (pin "53") (pinfunction "VDDC53_53") (pintype "passive"))
      (node (ref "U1_1") (pin "54") (pinfunction "VDDC54_54") (pintype "passive"))
      (node (ref "U1_1") (pin "55") (pinfunction "VDDC55_55") (pintype "passive"))
      (node (ref "U1_1") (pin "56") (pinfunction "VDDC56_56") (pintype "passive"))
      (node (ref "U1_1") (pin "57") (pinfunction "VDDC57_57") (pintype "passive"))
      (node (ref "U1_1") (pin "58") (pinfunction "VDDC58_58") (pintype "passive"))
      (node (ref "U1_1") (pin "59") (pinfunction "VDDC59_59") (pintype "passive"))
      (node (ref "U1_1") (pin "6") (pinfunction "VDDC6_6") (pintype "passive"))
      (node (ref "U1_1") (pin "60") (pinfunction "VDDC60_60") (pintype "passive"))
      (node (ref "U1_1") (pin "61") (pinfunction "VDDC61_61") (pintype "passive"))
      (node (ref "U1_1") (pin "62") (pinfunction "VDDC62_62") (pintype "passive"))
      (node (ref "U1_1") (pin "63") (pinfunction "VDDC63_63") (pintype "passive"))
      (node (ref "U1_1") (pin "64") (pinfunction "VDDC64_64") (pintype "passive"))
      (node (ref "U1_1") (pin "65") (pinfunction "VDDC65_65") (pintype "passive"))
      (node (ref "U1_1") (pin "66") (pinfunction "VDDC66_66") (pintype "passive"))
      (node (ref "U1_1") (pin "67") (pinfunction "VDDC67_67") (pintype "passive"))
      (node (ref "U1_1") (pin "68") (pinfunction "VDDC68_68") (pintype "passive"))
      (node (ref "U1_1") (pin "7") (pinfunction "VDDC7_7") (pintype "passive"))
      (node (ref "U1_1") (pin "8") (pinfunction "VDDC8_8") (pintype "passive"))
      (node (ref "U1_1") (pin "9") (pinfunction "VDDC9_9") (pintype "passive"))
      (node (ref "U1_10") (pin "1") (pinfunction "VDDC1_1") (pintype "passive"))
      (node (ref "U1_10") (pin "14") (pinfunction "VDDC14_14") (pintype "passive"))
      (node (ref "U1_10") (pin "15") (pinfunction "VDDC15_15") (pintype "passive"))
      (node (ref "U1_10") (pin "16") (pinfunction "VDDC16_16") (pintype "passive"))
      (node (ref "U1_10") (pin "17") (pinfunction "VDDC17_17") (pintype "passive"))
      (node (ref "U1_10") (pin "18") (pinfunction "VDDC18_18") (pintype "passive"))
      (node (ref "U1_10") (pin "19") (pinfunction "VDDC19_19") (pintype "passive"))
      (node (ref "U1_10") (pin "2") (pinfunction "VDDC2_2") (pintype "passive"))
      (node (ref "U1_10") (pin "20") (pinfunction "VDDC20_20") (pintype "passive"))
      (node (ref "U1_10") (pin "21") (pinfunction "VDDC21_21") (pintype "passive"))
      (node (ref "U1_10") (pin "22") (pinfunction "VDDC22_22") (pintype "passive"))
      (node (ref "U1_10") (pin "23") (pinfunction "VDDC23_23") (pintype "passive"))
      (node (ref "U1_10") (pin "24") (pinfunction "VDDC24_24") (pintype "passive"))
      (node (ref "U1_10") (pin "25") (pinfunction "VDDC25_25") (pintype "passive"))
      (node (ref "U1_10") (pin "26") (pinfunction "VDDC26_26") (pintype "passive"))
      (node (ref "U1_10") (pin "27") (pinfunction "VDDC27_27") (pintype "passive"))
      (node (ref "U1_10") (pin "28") (pinfunction "VDDC28_28") (pintype "passive"))
      (node (ref "U1_10") (pin "29") (pinfunction "VDDC29_29") (pintype "passive"))
      (node (ref "U1_10") (pin "3") (pinfunction "VDDC3_3") (pintype "passive"))
      (node (ref "U1_10") (pin "30") (pinfunction "VDDC30_30") (pintype "passive"))
      (node (ref "U1_10") (pin "31") (pinfunction "VDDC31_31") (pintype "passive"))
      (node (ref "U1_10") (pin "32") (pinfunction "VDDC32_32") (pintype "passive"))
      (node (ref "U1_10") (pin "33") (pinfunction "VDDC33_33") (pintype "passive"))
      (node (ref "U1_10") (pin "34") (pinfunction "VDDC34_34") (pintype "passive"))
      (node (ref "U1_10") (pin "35") (pinfunction "VDDC35_35") (pintype "passive"))
      (node (ref "U1_10") (pin "36") (pinfunction "VDDC36_36") (pintype "passive"))
      (node (ref "U1_10") (pin "37") (pinfunction "VDDC37_37") (pintype "passive"))
      (node (ref "U1_10") (pin "38") (pinfunction "VDDC38_38") (pintype "passive"))
      (node (ref "U1_10") (pin "4") (pinfunction "VDDC4_4") (pintype "passive"))
      (node (ref "U1_10") (pin "45") (pinfunction "VDDC45_45") (pintype "passive"))
      (node (ref "U1_10") (pin "46") (pinfunction "VDDC46_46") (pintype "passive"))
      (node (ref "U1_10") (pin "47") (pinfunction "VDDC47_47") (pintype "passive"))
      (node (ref "U1_10") (pin "48") (pinfunction "VDDC48_48") (pintype "passive"))
      (node (ref "U1_10") (pin "49") (pinfunction "VDDC49_49") (pintype "passive"))
      (node (ref "U1_10") (pin "5") (pinfunction "VDDC5_5") (pintype "passive"))
      (node (ref "U1_10") (pin "50") (pinfunction "VDDC50_50") (pintype "passive"))
      (node (ref "U1_10") (pin "51") (pinfunction "VDDC51_51") (pintype "passive"))
      (node (ref "U1_10") (pin "52") (pinfunction "VDDC52_52") (pintype "passive"))
      (node (ref "U1_10") (pin "53") (pinfunction "VDDC53_53") (pintype "passive"))
      (node (ref "U1_10") (pin "54") (pinfunction "VDDC54_54") (pintype "passive"))
      (node (ref "U1_10") (pin "55") (pinfunction "VDDC55_55") (pintype "passive"))
      (node (ref "U1_10") (pin "56") (pinfunction "VDDC56_56") (pintype "passive"))
      (node (ref "U1_10") (pin "57") (pinfunction "VDDC57_57") (pintype "passive"))
      (node (ref "U1_10") (pin "58") (pinfunction "VDDC58_58") (pintype "passive"))
      (node (ref "U1_10") (pin "59") (pinfunction "VDDC59_59") (pintype "passive"))
      (node (ref "U1_10") (pin "6") (pinfunction "VDDC6_6") (pintype "passive"))
      (node (ref "U1_10") (pin "60") (pinfunction "VDDC60_60") (pintype "passive"))
      (node (ref "U1_10") (pin "61") (pinfunction "VDDC61_61") (pintype "passive"))
      (node (ref "U1_10") (pin "62") (pinfunction "VDDC62_62") (pintype "passive"))
      (node (ref "U1_10") (pin "63") (pinfunction "VDDC63_63") (pintype "passive"))
      (node (ref "U1_10") (pin "64") (pinfunction "VDDC64_64") (pintype "passive"))
      (node (ref "U1_10") (pin "65") (pinfunction "VDDC65_65") (pintype "passive"))
      (node (ref "U1_10") (pin "66") (pinfunction "VDDC66_66") (pintype "passive"))
      (node (ref "U1_10") (pin "67") (pinfunction "VDDC67_67") (pintype "passive"))
      (node (ref "U1_10") (pin "68") (pinfunction "VDDC68_68") (pintype "passive"))
      (node (ref "U1_10") (pin "7") (pinfunction "VDDC7_7") (pintype "passive"))
      (node (ref "U1_10") (pin "8") (pinfunction "VDDC8_8") (pintype "passive"))
      (node (ref "U1_10") (pin "9") (pinfunction "VDDC9_9") (pintype "passive"))
      (node (ref "U1_11") (pin "1") (pinfunction "VDDC1_1") (pintype "passive"))
      (node (ref "U1_11") (pin "14") (pinfunction "VDDC14_14") (pintype "passive"))
      (node (ref "U1_11") (pin "15") (pinfunction "VDDC15_15") (pintype "passive"))
      (node (ref "U1_11") (pin "16") (pinfunction "VDDC16_16") (pintype "passive"))
      (node (ref "U1_11") (pin "17") (pinfunction "VDDC17_17") (pintype "passive"))
      (node (ref "U1_11") (pin "18") (pinfunction "VDDC18_18") (pintype "passive"))
      (node (ref "U1_11") (pin "19") (pinfunction "VDDC19_19") (pintype "passive"))
      (node (ref "U1_11") (pin "2") (pinfunction "VDDC2_2") (pintype "passive"))
      (node (ref "U1_11") (pin "20") (pinfunction "VDDC20_20") (pintype "passive"))
      (node (ref "U1_11") (pin "21") (pinfunction "VDDC21_21") (pintype "passive"))
      (node (ref "U1_11") (pin "22") (pinfunction "VDDC22_22") (pintype "passive"))
      (node (ref "U1_11") (pin "23") (pinfunction "VDDC23_23") (pintype "passive"))
      (node (ref "U1_11") (pin "24") (pinfunction "VDDC24_24") (pintype "passive"))
      (node (ref "U1_11") (pin "25") (pinfunction "VDDC25_25") (pintype "passive"))
      (node (ref "U1_11") (pin "26") (pinfunction "VDDC26_26") (pintype "passive"))
      (node (ref "U1_11") (pin "27") (pinfunction "VDDC27_27") (pintype "passive"))
      (node (ref "U1_11") (pin "28") (pinfunction "VDDC28_28") (pintype "passive"))
      (node (ref "U1_11") (pin "29") (pinfunction "VDDC29_29") (pintype "passive"))
      (node (ref "U1_11") (pin "3") (pinfunction "VDDC3_3") (pintype "passive"))
      (node (ref "U1_11") (pin "30") (pinfunction "VDDC30_30") (pintype "passive"))
      (node (ref "U1_11") (pin "31") (pinfunction "VDDC31_31") (pintype "passive"))
      (node (ref "U1_11") (pin "32") (pinfunction "VDDC32_32") (pintype "passive"))
      (node (ref "U1_11") (pin "33") (pinfunction "VDDC33_33") (pintype "passive"))
      (node (ref "U1_11") (pin "34") (pinfunction "VDDC34_34") (pintype "passive"))
      (node (ref "U1_11") (pin "35") (pinfunction "VDDC35_35") (pintype "passive"))
      (node (ref "U1_11") (pin "36") (pinfunction "VDDC36_36") (pintype "passive"))
      (node (ref "U1_11") (pin "37") (pinfunction "VDDC37_37") (pintype "passive"))
      (node (ref "U1_11") (pin "38") (pinfunction "VDDC38_38") (pintype "passive"))
      (node (ref "U1_11") (pin "4") (pinfunction "VDDC4_4") (pintype "passive"))
      (node (ref "U1_11") (pin "45") (pinfunction "VDDC45_45") (pintype "passive"))
      (node (ref "U1_11") (pin "46") (pinfunction "VDDC46_46") (pintype "passive"))
      (node (ref "U1_11") (pin "47") (pinfunction "VDDC47_47") (pintype "passive"))
      (node (ref "U1_11") (pin "48") (pinfunction "VDDC48_48") (pintype "passive"))
      (node (ref "U1_11") (pin "49") (pinfunction "VDDC49_49") (pintype "passive"))
      (node (ref "U1_11") (pin "5") (pinfunction "VDDC5_5") (pintype "passive"))
      (node (ref "U1_11") (pin "50") (pinfunction "VDDC50_50") (pintype "passive"))
      (node (ref "U1_11") (pin "51") (pinfunction "VDDC51_51") (pintype "passive"))
      (node (ref "U1_11") (pin "52") (pinfunction "VDDC52_52") (pintype "passive"))
      (node (ref "U1_11") (pin "53") (pinfunction "VDDC53_53") (pintype "passive"))
      (node (ref "U1_11") (pin "54") (pinfunction "VDDC54_54") (pintype "passive"))
      (node (ref "U1_11") (pin "55") (pinfunction "VDDC55_55") (pintype "passive"))
      (node (ref "U1_11") (pin "56") (pinfunction "VDDC56_56") (pintype "passive"))
      (node (ref "U1_11") (pin "57") (pinfunction "VDDC57_57") (pintype "passive"))
      (node (ref "U1_11") (pin "58") (pinfunction "VDDC58_58") (pintype "passive"))
      (node (ref "U1_11") (pin "59") (pinfunction "VDDC59_59") (pintype "passive"))
      (node (ref "U1_11") (pin "6") (pinfunction "VDDC6_6") (pintype "passive"))
      (node (ref "U1_11") (pin "60") (pinfunction "VDDC60_60") (pintype "passive"))
      (node (ref "U1_11") (pin "61") (pinfunction "VDDC61_61") (pintype "passive"))
      (node (ref "U1_11") (pin "62") (pinfunction "VDDC62_62") (pintype "passive"))
      (node (ref "U1_11") (pin "63") (pinfunction "VDDC63_63") (pintype "passive"))
      (node (ref "U1_11") (pin "64") (pinfunction "VDDC64_64") (pintype "passive"))
      (node (ref "U1_11") (pin "65") (pinfunction "VDDC65_65") (pintype "passive"))
      (node (ref "U1_11") (pin "66") (pinfunction "VDDC66_66") (pintype "passive"))
      (node (ref "U1_11") (pin "67") (pinfunction "VDDC67_67") (pintype "passive"))
      (node (ref "U1_11") (pin "68") (pinfunction "VDDC68_68") (pintype "passive"))
      (node (ref "U1_11") (pin "7") (pinfunction "VDDC7_7") (pintype "passive"))
      (node (ref "U1_11") (pin "8") (pinfunction "VDDC8_8") (pintype "passive"))
      (node (ref "U1_11") (pin "9") (pinfunction "VDDC9_9") (pintype "passive"))
      (node (ref "U1_12") (pin "1") (pinfunction "VDDC1_1") (pintype "passive"))
      (node (ref "U1_12") (pin "14") (pinfunction "VDDC14_14") (pintype "passive"))
      (node (ref "U1_12") (pin "15") (pinfunction "VDDC15_15") (pintype "passive"))
      (node (ref "U1_12") (pin "16") (pinfunction "VDDC16_16") (pintype "passive"))
      (node (ref "U1_12") (pin "17") (pinfunction "VDDC17_17") (pintype "passive"))
      (node (ref "U1_12") (pin "18") (pinfunction "VDDC18_18") (pintype "passive"))
      (node (ref "U1_12") (pin "19") (pinfunction "VDDC19_19") (pintype "passive"))
      (node (ref "U1_12") (pin "2") (pinfunction "VDDC2_2") (pintype "passive"))
      (node (ref "U1_12") (pin "20") (pinfunction "VDDC20_20") (pintype "passive"))
      (node (ref "U1_12") (pin "21") (pinfunction "VDDC21_21") (pintype "passive"))
      (node (ref "U1_12") (pin "22") (pinfunction "VDDC22_22") (pintype "passive"))
      (node (ref "U1_12") (pin "23") (pinfunction "VDDC23_23") (pintype "passive"))
      (node (ref "U1_12") (pin "24") (pinfunction "VDDC24_24") (pintype "passive"))
      (node (ref "U1_12") (pin "25") (pinfunction "VDDC25_25") (pintype "passive"))
      (node (ref "U1_12") (pin "26") (pinfunction "VDDC26_26") (pintype "passive"))
      (node (ref "U1_12") (pin "27") (pinfunction "VDDC27_27") (pintype "passive"))
      (node (ref "U1_12") (pin "28") (pinfunction "VDDC28_28") (pintype "passive"))
      (node (ref "U1_12") (pin "29") (pinfunction "VDDC29_29") (pintype "passive"))
      (node (ref "U1_12") (pin "3") (pinfunction "VDDC3_3") (pintype "passive"))
      (node (ref "U1_12") (pin "30") (pinfunction "VDDC30_30") (pintype "passive"))
      (node (ref "U1_12") (pin "31") (pinfunction "VDDC31_31") (pintype "passive"))
      (node (ref "U1_12") (pin "32") (pinfunction "VDDC32_32") (pintype "passive"))
      (node (ref "U1_12") (pin "33") (pinfunction "VDDC33_33") (pintype "passive"))
      (node (ref "U1_12") (pin "34") (pinfunction "VDDC34_34") (pintype "passive"))
      (node (ref "U1_12") (pin "35") (pinfunction "VDDC35_35") (pintype "passive"))
      (node (ref "U1_12") (pin "36") (pinfunction "VDDC36_36") (pintype "passive"))
      (node (ref "U1_12") (pin "37") (pinfunction "VDDC37_37") (pintype "passive"))
      (node (ref "U1_12") (pin "38") (pinfunction "VDDC38_38") (pintype "passive"))
      (node (ref "U1_12") (pin "4") (pinfunction "VDDC4_4") (pintype "passive"))
      (node (ref "U1_12") (pin "45") (pinfunction "VDDC45_45") (pintype "passive"))
      (node (ref "U1_12") (pin "46") (pinfunction "VDDC46_46") (pintype "passive"))
      (node (ref "U1_12") (pin "47") (pinfunction "VDDC47_47") (pintype "passive"))
      (node (ref "U1_12") (pin "48") (pinfunction "VDDC48_48") (pintype "passive"))
      (node (ref "U1_12") (pin "49") (pinfunction "VDDC49_49") (pintype "passive"))
      (node (ref "U1_12") (pin "5") (pinfunction "VDDC5_5") (pintype "passive"))
      (node (ref "U1_12") (pin "50") (pinfunction "VDDC50_50") (pintype "passive"))
      (node (ref "U1_12") (pin "51") (pinfunction "VDDC51_51") (pintype "passive"))
      (node (ref "U1_12") (pin "52") (pinfunction "VDDC52_52") (pintype "passive"))
      (node (ref "U1_12") (pin "53") (pinfunction "VDDC53_53") (pintype "passive"))
      (node (ref "U1_12") (pin "54") (pinfunction "VDDC54_54") (pintype "passive"))
      (node (ref "U1_12") (pin "55") (pinfunction "VDDC55_55") (pintype "passive"))
      (node (ref "U1_12") (pin "56") (pinfunction "VDDC56_56") (pintype "passive"))
      (node (ref "U1_12") (pin "57") (pinfunction "VDDC57_57") (pintype "passive"))
      (node (ref "U1_12") (pin "58") (pinfunction "VDDC58_58") (pintype "passive"))
      (node (ref "U1_12") (pin "59") (pinfunction "VDDC59_59") (pintype "passive"))
      (node (ref "U1_12") (pin "6") (pinfunction "VDDC6_6") (pintype "passive"))
      (node (ref "U1_12") (pin "60") (pinfunction "VDDC60_60") (pintype "passive"))
      (node (ref "U1_12") (pin "61") (pinfunction "VDDC61_61") (pintype "passive"))
      (node (ref "U1_12") (pin "62") (pinfunction "VDDC62_62") (pintype "passive"))
      (node (ref "U1_12") (pin "63") (pinfunction "VDDC63_63") (pintype "passive"))
      (node (ref "U1_12") (pin "64") (pinfunction "VDDC64_64") (pintype "passive"))
      (node (ref "U1_12") (pin "65") (pinfunction "VDDC65_65") (pintype "passive"))
      (node (ref "U1_12") (pin "66") (pinfunction "VDDC66_66") (pintype "passive"))
      (node (ref "U1_12") (pin "67") (pinfunction "VDDC67_67") (pintype "passive"))
      (node (ref "U1_12") (pin "68") (pinfunction "VDDC68_68") (pintype "passive"))
      (node (ref "U1_12") (pin "7") (pinfunction "VDDC7_7") (pintype "passive"))
      (node (ref "U1_12") (pin "8") (pinfunction "VDDC8_8") (pintype "passive"))
      (node (ref "U1_12") (pin "9") (pinfunction "VDDC9_9") (pintype "passive"))
      (node (ref "U1_13") (pin "1") (pinfunction "VDDC1_1") (pintype "passive"))
      (node (ref "U1_13") (pin "14") (pinfunction "VDDC14_14") (pintype "passive"))
      (node (ref "U1_13") (pin "15") (pinfunction "VDDC15_15") (pintype "passive"))
      (node (ref "U1_13") (pin "16") (pinfunction "VDDC16_16") (pintype "passive"))
      (node (ref "U1_13") (pin "17") (pinfunction "VDDC17_17") (pintype "passive"))
      (node (ref "U1_13") (pin "18") (pinfunction "VDDC18_18") (pintype "passive"))
      (node (ref "U1_13") (pin "19") (pinfunction "VDDC19_19") (pintype "passive"))
      (node (ref "U1_13") (pin "2") (pinfunction "VDDC2_2") (pintype "passive"))
      (node (ref "U1_13") (pin "20") (pinfunction "VDDC20_20") (pintype "passive"))
      (node (ref "U1_13") (pin "21") (pinfunction "VDDC21_21") (pintype "passive"))
      (node (ref "U1_13") (pin "22") (pinfunction "VDDC22_22") (pintype "passive"))
      (node (ref "U1_13") (pin "23") (pinfunction "VDDC23_23") (pintype "passive"))
      (node (ref "U1_13") (pin "24") (pinfunction "VDDC24_24") (pintype "passive"))
      (node (ref "U1_13") (pin "25") (pinfunction "VDDC25_25") (pintype "passive"))
      (node (ref "U1_13") (pin "26") (pinfunction "VDDC26_26") (pintype "passive"))
      (node (ref "U1_13") (pin "27") (pinfunction "VDDC27_27") (pintype "passive"))
      (node (ref "U1_13") (pin "28") (pinfunction "VDDC28_28") (pintype "passive"))
      (node (ref "U1_13") (pin "29") (pinfunction "VDDC29_29") (pintype "passive"))
      (node (ref "U1_13") (pin "3") (pinfunction "VDDC3_3") (pintype "passive"))
      (node (ref "U1_13") (pin "30") (pinfunction "VDDC30_30") (pintype "passive"))
      (node (ref "U1_13") (pin "31") (pinfunction "VDDC31_31") (pintype "passive"))
      (node (ref "U1_13") (pin "32") (pinfunction "VDDC32_32") (pintype "passive"))
      (node (ref "U1_13") (pin "33") (pinfunction "VDDC33_33") (pintype "passive"))
      (node (ref "U1_13") (pin "34") (pinfunction "VDDC34_34") (pintype "passive"))
      (node (ref "U1_13") (pin "35") (pinfunction "VDDC35_35") (pintype "passive"))
      (node (ref "U1_13") (pin "36") (pinfunction "VDDC36_36") (pintype "passive"))
      (node (ref "U1_13") (pin "37") (pinfunction "VDDC37_37") (pintype "passive"))
      (node (ref "U1_13") (pin "38") (pinfunction "VDDC38_38") (pintype "passive"))
      (node (ref "U1_13") (pin "4") (pinfunction "VDDC4_4") (pintype "passive"))
      (node (ref "U1_13") (pin "45") (pinfunction "VDDC45_45") (pintype "passive"))
      (node (ref "U1_13") (pin "46") (pinfunction "VDDC46_46") (pintype "passive"))
      (node (ref "U1_13") (pin "47") (pinfunction "VDDC47_47") (pintype "passive"))
      (node (ref "U1_13") (pin "48") (pinfunction "VDDC48_48") (pintype "passive"))
      (node (ref "U1_13") (pin "49") (pinfunction "VDDC49_49") (pintype "passive"))
      (node (ref "U1_13") (pin "5") (pinfunction "VDDC5_5") (pintype "passive"))
      (node (ref "U1_13") (pin "50") (pinfunction "VDDC50_50") (pintype "passive"))
      (node (ref "U1_13") (pin "51") (pinfunction "VDDC51_51") (pintype "passive"))
      (node (ref "U1_13") (pin "52") (pinfunction "VDDC52_52") (pintype "passive"))
      (node (ref "U1_13") (pin "53") (pinfunction "VDDC53_53") (pintype "passive"))
      (node (ref "U1_13") (pin "54") (pinfunction "VDDC54_54") (pintype "passive"))
      (node (ref "U1_13") (pin "55") (pinfunction "VDDC55_55") (pintype "passive"))
      (node (ref "U1_13") (pin "56") (pinfunction "VDDC56_56") (pintype "passive"))
      (node (ref "U1_13") (pin "57") (pinfunction "VDDC57_57") (pintype "passive"))
      (node (ref "U1_13") (pin "58") (pinfunction "VDDC58_58") (pintype "passive"))
      (node (ref "U1_13") (pin "59") (pinfunction "VDDC59_59") (pintype "passive"))
      (node (ref "U1_13") (pin "6") (pinfunction "VDDC6_6") (pintype "passive"))
      (node (ref "U1_13") (pin "60") (pinfunction "VDDC60_60") (pintype "passive"))
      (node (ref "U1_13") (pin "61") (pinfunction "VDDC61_61") (pintype "passive"))
      (node (ref "U1_13") (pin "62") (pinfunction "VDDC62_62") (pintype "passive"))
      (node (ref "U1_13") (pin "63") (pinfunction "VDDC63_63") (pintype "passive"))
      (node (ref "U1_13") (pin "64") (pinfunction "VDDC64_64") (pintype "passive"))
      (node (ref "U1_13") (pin "65") (pinfunction "VDDC65_65") (pintype "passive"))
      (node (ref "U1_13") (pin "66") (pinfunction "VDDC66_66") (pintype "passive"))
      (node (ref "U1_13") (pin "67") (pinfunction "VDDC67_67") (pintype "passive"))
      (node (ref "U1_13") (pin "68") (pinfunction "VDDC68_68") (pintype "passive"))
      (node (ref "U1_13") (pin "7") (pinfunction "VDDC7_7") (pintype "passive"))
      (node (ref "U1_13") (pin "8") (pinfunction "VDDC8_8") (pintype "passive"))
      (node (ref "U1_13") (pin "9") (pinfunction "VDDC9_9") (pintype "passive"))
      (node (ref "U1_14") (pin "1") (pinfunction "VDDC1_1") (pintype "passive"))
      (node (ref "U1_14") (pin "14") (pinfunction "VDDC14_14") (pintype "passive"))
      (node (ref "U1_14") (pin "15") (pinfunction "VDDC15_15") (pintype "passive"))
      (node (ref "U1_14") (pin "16") (pinfunction "VDDC16_16") (pintype "passive"))
      (node (ref "U1_14") (pin "17") (pinfunction "VDDC17_17") (pintype "passive"))
      (node (ref "U1_14") (pin "18") (pinfunction "VDDC18_18") (pintype "passive"))
      (node (ref "U1_14") (pin "19") (pinfunction "VDDC19_19") (pintype "passive"))
      (node (ref "U1_14") (pin "2") (pinfunction "VDDC2_2") (pintype "passive"))
      (node (ref "U1_14") (pin "20") (pinfunction "VDDC20_20") (pintype "passive"))
      (node (ref "U1_14") (pin "21") (pinfunction "VDDC21_21") (pintype "passive"))
      (node (ref "U1_14") (pin "22") (pinfunction "VDDC22_22") (pintype "passive"))
      (node (ref "U1_14") (pin "23") (pinfunction "VDDC23_23") (pintype "passive"))
      (node (ref "U1_14") (pin "24") (pinfunction "VDDC24_24") (pintype "passive"))
      (node (ref "U1_14") (pin "25") (pinfunction "VDDC25_25") (pintype "passive"))
      (node (ref "U1_14") (pin "26") (pinfunction "VDDC26_26") (pintype "passive"))
      (node (ref "U1_14") (pin "27") (pinfunction "VDDC27_27") (pintype "passive"))
      (node (ref "U1_14") (pin "28") (pinfunction "VDDC28_28") (pintype "passive"))
      (node (ref "U1_14") (pin "29") (pinfunction "VDDC29_29") (pintype "passive"))
      (node (ref "U1_14") (pin "3") (pinfunction "VDDC3_3") (pintype "passive"))
      (node (ref "U1_14") (pin "30") (pinfunction "VDDC30_30") (pintype "passive"))
      (node (ref "U1_14") (pin "31") (pinfunction "VDDC31_31") (pintype "passive"))
      (node (ref "U1_14") (pin "32") (pinfunction "VDDC32_32") (pintype "passive"))
      (node (ref "U1_14") (pin "33") (pinfunction "VDDC33_33") (pintype "passive"))
      (node (ref "U1_14") (pin "34") (pinfunction "VDDC34_34") (pintype "passive"))
      (node (ref "U1_14") (pin "35") (pinfunction "VDDC35_35") (pintype "passive"))
      (node (ref "U1_14") (pin "36") (pinfunction "VDDC36_36") (pintype "passive"))
      (node (ref "U1_14") (pin "37") (pinfunction "VDDC37_37") (pintype "passive"))
      (node (ref "U1_14") (pin "38") (pinfunction "VDDC38_38") (pintype "passive"))
      (node (ref "U1_14") (pin "4") (pinfunction "VDDC4_4") (pintype "passive"))
      (node (ref "U1_14") (pin "45") (pinfunction "VDDC45_45") (pintype "passive"))
      (node (ref "U1_14") (pin "46") (pinfunction "VDDC46_46") (pintype "passive"))
      (node (ref "U1_14") (pin "47") (pinfunction "VDDC47_47") (pintype "passive"))
      (node (ref "U1_14") (pin "48") (pinfunction "VDDC48_48") (pintype "passive"))
      (node (ref "U1_14") (pin "49") (pinfunction "VDDC49_49") (pintype "passive"))
      (node (ref "U1_14") (pin "5") (pinfunction "VDDC5_5") (pintype "passive"))
      (node (ref "U1_14") (pin "50") (pinfunction "VDDC50_50") (pintype "passive"))
      (node (ref "U1_14") (pin "51") (pinfunction "VDDC51_51") (pintype "passive"))
      (node (ref "U1_14") (pin "52") (pinfunction "VDDC52_52") (pintype "passive"))
      (node (ref "U1_14") (pin "53") (pinfunction "VDDC53_53") (pintype "passive"))
      (node (ref "U1_14") (pin "54") (pinfunction "VDDC54_54") (pintype "passive"))
      (node (ref "U1_14") (pin "55") (pinfunction "VDDC55_55") (pintype "passive"))
      (node (ref "U1_14") (pin "56") (pinfunction "VDDC56_56") (pintype "passive"))
      (node (ref "U1_14") (pin "57") (pinfunction "VDDC57_57") (pintype "passive"))
      (node (ref "U1_14") (pin "58") (pinfunction "VDDC58_58") (pintype "passive"))
      (node (ref "U1_14") (pin "59") (pinfunction "VDDC59_59") (pintype "passive"))
      (node (ref "U1_14") (pin "6") (pinfunction "VDDC6_6") (pintype "passive"))
      (node (ref "U1_14") (pin "60") (pinfunction "VDDC60_60") (pintype "passive"))
      (node (ref "U1_14") (pin "61") (pinfunction "VDDC61_61") (pintype "passive"))
      (node (ref "U1_14") (pin "62") (pinfunction "VDDC62_62") (pintype "passive"))
      (node (ref "U1_14") (pin "63") (pinfunction "VDDC63_63") (pintype "passive"))
      (node (ref "U1_14") (pin "64") (pinfunction "VDDC64_64") (pintype "passive"))
      (node (ref "U1_14") (pin "65") (pinfunction "VDDC65_65") (pintype "passive"))
      (node (ref "U1_14") (pin "66") (pinfunction "VDDC66_66") (pintype "passive"))
      (node (ref "U1_14") (pin "67") (pinfunction "VDDC67_67") (pintype "passive"))
      (node (ref "U1_14") (pin "68") (pinfunction "VDDC68_68") (pintype "passive"))
      (node (ref "U1_14") (pin "7") (pinfunction "VDDC7_7") (pintype "passive"))
      (node (ref "U1_14") (pin "8") (pinfunction "VDDC8_8") (pintype "passive"))
      (node (ref "U1_14") (pin "9") (pinfunction "VDDC9_9") (pintype "passive"))
      (node (ref "U1_15") (pin "1") (pinfunction "VDDC1_1") (pintype "passive"))
      (node (ref "U1_15") (pin "14") (pinfunction "VDDC14_14") (pintype "passive"))
      (node (ref "U1_15") (pin "15") (pinfunction "VDDC15_15") (pintype "passive"))
      (node (ref "U1_15") (pin "16") (pinfunction "VDDC16_16") (pintype "passive"))
      (node (ref "U1_15") (pin "17") (pinfunction "VDDC17_17") (pintype "passive"))
      (node (ref "U1_15") (pin "18") (pinfunction "VDDC18_18") (pintype "passive"))
      (node (ref "U1_15") (pin "19") (pinfunction "VDDC19_19") (pintype "passive"))
      (node (ref "U1_15") (pin "2") (pinfunction "VDDC2_2") (pintype "passive"))
      (node (ref "U1_15") (pin "20") (pinfunction "VDDC20_20") (pintype "passive"))
      (node (ref "U1_15") (pin "21") (pinfunction "VDDC21_21") (pintype "passive"))
      (node (ref "U1_15") (pin "22") (pinfunction "VDDC22_22") (pintype "passive"))
      (node (ref "U1_15") (pin "23") (pinfunction "VDDC23_23") (pintype "passive"))
      (node (ref "U1_15") (pin "24") (pinfunction "VDDC24_24") (pintype "passive"))
      (node (ref "U1_15") (pin "25") (pinfunction "VDDC25_25") (pintype "passive"))
      (node (ref "U1_15") (pin "26") (pinfunction "VDDC26_26") (pintype "passive"))
      (node (ref "U1_15") (pin "27") (pinfunction "VDDC27_27") (pintype "passive"))
      (node (ref "U1_15") (pin "28") (pinfunction "VDDC28_28") (pintype "passive"))
      (node (ref "U1_15") (pin "29") (pinfunction "VDDC29_29") (pintype "passive"))
      (node (ref "U1_15") (pin "3") (pinfunction "VDDC3_3") (pintype "passive"))
      (node (ref "U1_15") (pin "30") (pinfunction "VDDC30_30") (pintype "passive"))
      (node (ref "U1_15") (pin "31") (pinfunction "VDDC31_31") (pintype "passive"))
      (node (ref "U1_15") (pin "32") (pinfunction "VDDC32_32") (pintype "passive"))
      (node (ref "U1_15") (pin "33") (pinfunction "VDDC33_33") (pintype "passive"))
      (node (ref "U1_15") (pin "34") (pinfunction "VDDC34_34") (pintype "passive"))
      (node (ref "U1_15") (pin "35") (pinfunction "VDDC35_35") (pintype "passive"))
      (node (ref "U1_15") (pin "36") (pinfunction "VDDC36_36") (pintype "passive"))
      (node (ref "U1_15") (pin "37") (pinfunction "VDDC37_37") (pintype "passive"))
      (node (ref "U1_15") (pin "38") (pinfunction "VDDC38_38") (pintype "passive"))
      (node (ref "U1_15") (pin "4") (pinfunction "VDDC4_4") (pintype "passive"))
      (node (ref "U1_15") (pin "45") (pinfunction "VDDC45_45") (pintype "passive"))
      (node (ref "U1_15") (pin "46") (pinfunction "VDDC46_46") (pintype "passive"))
      (node (ref "U1_15") (pin "47") (pinfunction "VDDC47_47") (pintype "passive"))
      (node (ref "U1_15") (pin "48") (pinfunction "VDDC48_48") (pintype "passive"))
      (node (ref "U1_15") (pin "49") (pinfunction "VDDC49_49") (pintype "passive"))
      (node (ref "U1_15") (pin "5") (pinfunction "VDDC5_5") (pintype "passive"))
      (node (ref "U1_15") (pin "50") (pinfunction "VDDC50_50") (pintype "passive"))
      (node (ref "U1_15") (pin "51") (pinfunction "VDDC51_51") (pintype "passive"))
      (node (ref "U1_15") (pin "52") (pinfunction "VDDC52_52") (pintype "passive"))
      (node (ref "U1_15") (pin "53") (pinfunction "VDDC53_53") (pintype "passive"))
      (node (ref "U1_15") (pin "54") (pinfunction "VDDC54_54") (pintype "passive"))
      (node (ref "U1_15") (pin "55") (pinfunction "VDDC55_55") (pintype "passive"))
      (node (ref "U1_15") (pin "56") (pinfunction "VDDC56_56") (pintype "passive"))
      (node (ref "U1_15") (pin "57") (pinfunction "VDDC57_57") (pintype "passive"))
      (node (ref "U1_15") (pin "58") (pinfunction "VDDC58_58") (pintype "passive"))
      (node (ref "U1_15") (pin "59") (pinfunction "VDDC59_59") (pintype "passive"))
      (node (ref "U1_15") (pin "6") (pinfunction "VDDC6_6") (pintype "passive"))
      (node (ref "U1_15") (pin "60") (pinfunction "VDDC60_60") (pintype "passive"))
      (node (ref "U1_15") (pin "61") (pinfunction "VDDC61_61") (pintype "passive"))
      (node (ref "U1_15") (pin "62") (pinfunction "VDDC62_62") (pintype "passive"))
      (node (ref "U1_15") (pin "63") (pinfunction "VDDC63_63") (pintype "passive"))
      (node (ref "U1_15") (pin "64") (pinfunction "VDDC64_64") (pintype "passive"))
      (node (ref "U1_15") (pin "65") (pinfunction "VDDC65_65") (pintype "passive"))
      (node (ref "U1_15") (pin "66") (pinfunction "VDDC66_66") (pintype "passive"))
      (node (ref "U1_15") (pin "67") (pinfunction "VDDC67_67") (pintype "passive"))
      (node (ref "U1_15") (pin "68") (pinfunction "VDDC68_68") (pintype "passive"))
      (node (ref "U1_15") (pin "7") (pinfunction "VDDC7_7") (pintype "passive"))
      (node (ref "U1_15") (pin "8") (pinfunction "VDDC8_8") (pintype "passive"))
      (node (ref "U1_15") (pin "9") (pinfunction "VDDC9_9") (pintype "passive"))
      (node (ref "U1_16") (pin "1") (pinfunction "VDDC1_1") (pintype "passive"))
      (node (ref "U1_16") (pin "14") (pinfunction "VDDC14_14") (pintype "passive"))
      (node (ref "U1_16") (pin "15") (pinfunction "VDDC15_15") (pintype "passive"))
      (node (ref "U1_16") (pin "16") (pinfunction "VDDC16_16") (pintype "passive"))
      (node (ref "U1_16") (pin "17") (pinfunction "VDDC17_17") (pintype "passive"))
      (node (ref "U1_16") (pin "18") (pinfunction "VDDC18_18") (pintype "passive"))
      (node (ref "U1_16") (pin "19") (pinfunction "VDDC19_19") (pintype "passive"))
      (node (ref "U1_16") (pin "2") (pinfunction "VDDC2_2") (pintype "passive"))
      (node (ref "U1_16") (pin "20") (pinfunction "VDDC20_20") (pintype "passive"))
      (node (ref "U1_16") (pin "21") (pinfunction "VDDC21_21") (pintype "passive"))
      (node (ref "U1_16") (pin "22") (pinfunction "VDDC22_22") (pintype "passive"))
      (node (ref "U1_16") (pin "23") (pinfunction "VDDC23_23") (pintype "passive"))
      (node (ref "U1_16") (pin "24") (pinfunction "VDDC24_24") (pintype "passive"))
      (node (ref "U1_16") (pin "25") (pinfunction "VDDC25_25") (pintype "passive"))
      (node (ref "U1_16") (pin "26") (pinfunction "VDDC26_26") (pintype "passive"))
      (node (ref "U1_16") (pin "27") (pinfunction "VDDC27_27") (pintype "passive"))
      (node (ref "U1_16") (pin "28") (pinfunction "VDDC28_28") (pintype "passive"))
      (node (ref "U1_16") (pin "29") (pinfunction "VDDC29_29") (pintype "passive"))
      (node (ref "U1_16") (pin "3") (pinfunction "VDDC3_3") (pintype "passive"))
      (node (ref "U1_16") (pin "30") (pinfunction "VDDC30_30") (pintype "passive"))
      (node (ref "U1_16") (pin "31") (pinfunction "VDDC31_31") (pintype "passive"))
      (node (ref "U1_16") (pin "32") (pinfunction "VDDC32_32") (pintype "passive"))
      (node (ref "U1_16") (pin "33") (pinfunction "VDDC33_33") (pintype "passive"))
      (node (ref "U1_16") (pin "34") (pinfunction "VDDC34_34") (pintype "passive"))
      (node (ref "U1_16") (pin "35") (pinfunction "VDDC35_35") (pintype "passive"))
      (node (ref "U1_16") (pin "36") (pinfunction "VDDC36_36") (pintype "passive"))
      (node (ref "U1_16") (pin "37") (pinfunction "VDDC37_37") (pintype "passive"))
      (node (ref "U1_16") (pin "38") (pinfunction "VDDC38_38") (pintype "passive"))
      (node (ref "U1_16") (pin "4") (pinfunction "VDDC4_4") (pintype "passive"))
      (node (ref "U1_16") (pin "45") (pinfunction "VDDC45_45") (pintype "passive"))
      (node (ref "U1_16") (pin "46") (pinfunction "VDDC46_46") (pintype "passive"))
      (node (ref "U1_16") (pin "47") (pinfunction "VDDC47_47") (pintype "passive"))
      (node (ref "U1_16") (pin "48") (pinfunction "VDDC48_48") (pintype "passive"))
      (node (ref "U1_16") (pin "49") (pinfunction "VDDC49_49") (pintype "passive"))
      (node (ref "U1_16") (pin "5") (pinfunction "VDDC5_5") (pintype "passive"))
      (node (ref "U1_16") (pin "50") (pinfunction "VDDC50_50") (pintype "passive"))
      (node (ref "U1_16") (pin "51") (pinfunction "VDDC51_51") (pintype "passive"))
      (node (ref "U1_16") (pin "52") (pinfunction "VDDC52_52") (pintype "passive"))
      (node (ref "U1_16") (pin "53") (pinfunction "VDDC53_53") (pintype "passive"))
      (node (ref "U1_16") (pin "54") (pinfunction "VDDC54_54") (pintype "passive"))
      (node (ref "U1_16") (pin "55") (pinfunction "VDDC55_55") (pintype "passive"))
      (node (ref "U1_16") (pin "56") (pinfunction "VDDC56_56") (pintype "passive"))
      (node (ref "U1_16") (pin "57") (pinfunction "VDDC57_57") (pintype "passive"))
      (node (ref "U1_16") (pin "58") (pinfunction "VDDC58_58") (pintype "passive"))
      (node (ref "U1_16") (pin "59") (pinfunction "VDDC59_59") (pintype "passive"))
      (node (ref "U1_16") (pin "6") (pinfunction "VDDC6_6") (pintype "passive"))
      (node (ref "U1_16") (pin "60") (pinfunction "VDDC60_60") (pintype "passive"))
      (node (ref "U1_16") (pin "61") (pinfunction "VDDC61_61") (pintype "passive"))
      (node (ref "U1_16") (pin "62") (pinfunction "VDDC62_62") (pintype "passive"))
      (node (ref "U1_16") (pin "63") (pinfunction "VDDC63_63") (pintype "passive"))
      (node (ref "U1_16") (pin "64") (pinfunction "VDDC64_64") (pintype "passive"))
      (node (ref "U1_16") (pin "65") (pinfunction "VDDC65_65") (pintype "passive"))
      (node (ref "U1_16") (pin "66") (pinfunction "VDDC66_66") (pintype "passive"))
      (node (ref "U1_16") (pin "67") (pinfunction "VDDC67_67") (pintype "passive"))
      (node (ref "U1_16") (pin "68") (pinfunction "VDDC68_68") (pintype "passive"))
      (node (ref "U1_16") (pin "7") (pinfunction "VDDC7_7") (pintype "passive"))
      (node (ref "U1_16") (pin "8") (pinfunction "VDDC8_8") (pintype "passive"))
      (node (ref "U1_16") (pin "9") (pinfunction "VDDC9_9") (pintype "passive"))
      (node (ref "U1_2") (pin "1") (pinfunction "VDDC1_1") (pintype "passive"))
      (node (ref "U1_2") (pin "14") (pinfunction "VDDC14_14") (pintype "passive"))
      (node (ref "U1_2") (pin "15") (pinfunction "VDDC15_15") (pintype "passive"))
      (node (ref "U1_2") (pin "16") (pinfunction "VDDC16_16") (pintype "passive"))
      (node (ref "U1_2") (pin "17") (pinfunction "VDDC17_17") (pintype "passive"))
      (node (ref "U1_2") (pin "18") (pinfunction "VDDC18_18") (pintype "passive"))
      (node (ref "U1_2") (pin "19") (pinfunction "VDDC19_19") (pintype "passive"))
      (node (ref "U1_2") (pin "2") (pinfunction "VDDC2_2") (pintype "passive"))
      (node (ref "U1_2") (pin "20") (pinfunction "VDDC20_20") (pintype "passive"))
      (node (ref "U1_2") (pin "21") (pinfunction "VDDC21_21") (pintype "passive"))
      (node (ref "U1_2") (pin "22") (pinfunction "VDDC22_22") (pintype "passive"))
      (node (ref "U1_2") (pin "23") (pinfunction "VDDC23_23") (pintype "passive"))
      (node (ref "U1_2") (pin "24") (pinfunction "VDDC24_24") (pintype "passive"))
      (node (ref "U1_2") (pin "25") (pinfunction "VDDC25_25") (pintype "passive"))
      (node (ref "U1_2") (pin "26") (pinfunction "VDDC26_26") (pintype "passive"))
      (node (ref "U1_2") (pin "27") (pinfunction "VDDC27_27") (pintype "passive"))
      (node (ref "U1_2") (pin "28") (pinfunction "VDDC28_28") (pintype "passive"))
      (node (ref "U1_2") (pin "29") (pinfunction "VDDC29_29") (pintype "passive"))
      (node (ref "U1_2") (pin "3") (pinfunction "VDDC3_3") (pintype "passive"))
      (node (ref "U1_2") (pin "30") (pinfunction "VDDC30_30") (pintype "passive"))
      (node (ref "U1_2") (pin "31") (pinfunction "VDDC31_31") (pintype "passive"))
      (node (ref "U1_2") (pin "32") (pinfunction "VDDC32_32") (pintype "passive"))
      (node (ref "U1_2") (pin "33") (pinfunction "VDDC33_33") (pintype "passive"))
      (node (ref "U1_2") (pin "34") (pinfunction "VDDC34_34") (pintype "passive"))
      (node (ref "U1_2") (pin "35") (pinfunction "VDDC35_35") (pintype "passive"))
      (node (ref "U1_2") (pin "36") (pinfunction "VDDC36_36") (pintype "passive"))
      (node (ref "U1_2") (pin "37") (pinfunction "VDDC37_37") (pintype "passive"))
      (node (ref "U1_2") (pin "38") (pinfunction "VDDC38_38") (pintype "passive"))
      (node (ref "U1_2") (pin "4") (pinfunction "VDDC4_4") (pintype "passive"))
      (node (ref "U1_2") (pin "45") (pinfunction "VDDC45_45") (pintype "passive"))
      (node (ref "U1_2") (pin "46") (pinfunction "VDDC46_46") (pintype "passive"))
      (node (ref "U1_2") (pin "47") (pinfunction "VDDC47_47") (pintype "passive"))
      (node (ref "U1_2") (pin "48") (pinfunction "VDDC48_48") (pintype "passive"))
      (node (ref "U1_2") (pin "49") (pinfunction "VDDC49_49") (pintype "passive"))
      (node (ref "U1_2") (pin "5") (pinfunction "VDDC5_5") (pintype "passive"))
      (node (ref "U1_2") (pin "50") (pinfunction "VDDC50_50") (pintype "passive"))
      (node (ref "U1_2") (pin "51") (pinfunction "VDDC51_51") (pintype "passive"))
      (node (ref "U1_2") (pin "52") (pinfunction "VDDC52_52") (pintype "passive"))
      (node (ref "U1_2") (pin "53") (pinfunction "VDDC53_53") (pintype "passive"))
      (node (ref "U1_2") (pin "54") (pinfunction "VDDC54_54") (pintype "passive"))
      (node (ref "U1_2") (pin "55") (pinfunction "VDDC55_55") (pintype "passive"))
      (node (ref "U1_2") (pin "56") (pinfunction "VDDC56_56") (pintype "passive"))
      (node (ref "U1_2") (pin "57") (pinfunction "VDDC57_57") (pintype "passive"))
      (node (ref "U1_2") (pin "58") (pinfunction "VDDC58_58") (pintype "passive"))
      (node (ref "U1_2") (pin "59") (pinfunction "VDDC59_59") (pintype "passive"))
      (node (ref "U1_2") (pin "6") (pinfunction "VDDC6_6") (pintype "passive"))
      (node (ref "U1_2") (pin "60") (pinfunction "VDDC60_60") (pintype "passive"))
      (node (ref "U1_2") (pin "61") (pinfunction "VDDC61_61") (pintype "passive"))
      (node (ref "U1_2") (pin "62") (pinfunction "VDDC62_62") (pintype "passive"))
      (node (ref "U1_2") (pin "63") (pinfunction "VDDC63_63") (pintype "passive"))
      (node (ref "U1_2") (pin "64") (pinfunction "VDDC64_64") (pintype "passive"))
      (node (ref "U1_2") (pin "65") (pinfunction "VDDC65_65") (pintype "passive"))
      (node (ref "U1_2") (pin "66") (pinfunction "VDDC66_66") (pintype "passive"))
      (node (ref "U1_2") (pin "67") (pinfunction "VDDC67_67") (pintype "passive"))
      (node (ref "U1_2") (pin "68") (pinfunction "VDDC68_68") (pintype "passive"))
      (node (ref "U1_2") (pin "7") (pinfunction "VDDC7_7") (pintype "passive"))
      (node (ref "U1_2") (pin "8") (pinfunction "VDDC8_8") (pintype "passive"))
      (node (ref "U1_2") (pin "9") (pinfunction "VDDC9_9") (pintype "passive"))
      (node (ref "U1_3") (pin "1") (pinfunction "VDDC1_1") (pintype "passive"))
      (node (ref "U1_3") (pin "14") (pinfunction "VDDC14_14") (pintype "passive"))
      (node (ref "U1_3") (pin "15") (pinfunction "VDDC15_15") (pintype "passive"))
      (node (ref "U1_3") (pin "16") (pinfunction "VDDC16_16") (pintype "passive"))
      (node (ref "U1_3") (pin "17") (pinfunction "VDDC17_17") (pintype "passive"))
      (node (ref "U1_3") (pin "18") (pinfunction "VDDC18_18") (pintype "passive"))
      (node (ref "U1_3") (pin "19") (pinfunction "VDDC19_19") (pintype "passive"))
      (node (ref "U1_3") (pin "2") (pinfunction "VDDC2_2") (pintype "passive"))
      (node (ref "U1_3") (pin "20") (pinfunction "VDDC20_20") (pintype "passive"))
      (node (ref "U1_3") (pin "21") (pinfunction "VDDC21_21") (pintype "passive"))
      (node (ref "U1_3") (pin "22") (pinfunction "VDDC22_22") (pintype "passive"))
      (node (ref "U1_3") (pin "23") (pinfunction "VDDC23_23") (pintype "passive"))
      (node (ref "U1_3") (pin "24") (pinfunction "VDDC24_24") (pintype "passive"))
      (node (ref "U1_3") (pin "25") (pinfunction "VDDC25_25") (pintype "passive"))
      (node (ref "U1_3") (pin "26") (pinfunction "VDDC26_26") (pintype "passive"))
      (node (ref "U1_3") (pin "27") (pinfunction "VDDC27_27") (pintype "passive"))
      (node (ref "U1_3") (pin "28") (pinfunction "VDDC28_28") (pintype "passive"))
      (node (ref "U1_3") (pin "29") (pinfunction "VDDC29_29") (pintype "passive"))
      (node (ref "U1_3") (pin "3") (pinfunction "VDDC3_3") (pintype "passive"))
      (node (ref "U1_3") (pin "30") (pinfunction "VDDC30_30") (pintype "passive"))
      (node (ref "U1_3") (pin "31") (pinfunction "VDDC31_31") (pintype "passive"))
      (node (ref "U1_3") (pin "32") (pinfunction "VDDC32_32") (pintype "passive"))
      (node (ref "U1_3") (pin "33") (pinfunction "VDDC33_33") (pintype "passive"))
      (node (ref "U1_3") (pin "34") (pinfunction "VDDC34_34") (pintype "passive"))
      (node (ref "U1_3") (pin "35") (pinfunction "VDDC35_35") (pintype "passive"))
      (node (ref "U1_3") (pin "36") (pinfunction "VDDC36_36") (pintype "passive"))
      (node (ref "U1_3") (pin "37") (pinfunction "VDDC37_37") (pintype "passive"))
      (node (ref "U1_3") (pin "38") (pinfunction "VDDC38_38") (pintype "passive"))
      (node (ref "U1_3") (pin "4") (pinfunction "VDDC4_4") (pintype "passive"))
      (node (ref "U1_3") (pin "45") (pinfunction "VDDC45_45") (pintype "passive"))
      (node (ref "U1_3") (pin "46") (pinfunction "VDDC46_46") (pintype "passive"))
      (node (ref "U1_3") (pin "47") (pinfunction "VDDC47_47") (pintype "passive"))
      (node (ref "U1_3") (pin "48") (pinfunction "VDDC48_48") (pintype "passive"))
      (node (ref "U1_3") (pin "49") (pinfunction "VDDC49_49") (pintype "passive"))
      (node (ref "U1_3") (pin "5") (pinfunction "VDDC5_5") (pintype "passive"))
      (node (ref "U1_3") (pin "50") (pinfunction "VDDC50_50") (pintype "passive"))
      (node (ref "U1_3") (pin "51") (pinfunction "VDDC51_51") (pintype "passive"))
      (node (ref "U1_3") (pin "52") (pinfunction "VDDC52_52") (pintype "passive"))
      (node (ref "U1_3") (pin "53") (pinfunction "VDDC53_53") (pintype "passive"))
      (node (ref "U1_3") (pin "54") (pinfunction "VDDC54_54") (pintype "passive"))
      (node (ref "U1_3") (pin "55") (pinfunction "VDDC55_55") (pintype "passive"))
      (node (ref "U1_3") (pin "56") (pinfunction "VDDC56_56") (pintype "passive"))
      (node (ref "U1_3") (pin "57") (pinfunction "VDDC57_57") (pintype "passive"))
      (node (ref "U1_3") (pin "58") (pinfunction "VDDC58_58") (pintype "passive"))
      (node (ref "U1_3") (pin "59") (pinfunction "VDDC59_59") (pintype "passive"))
      (node (ref "U1_3") (pin "6") (pinfunction "VDDC6_6") (pintype "passive"))
      (node (ref "U1_3") (pin "60") (pinfunction "VDDC60_60") (pintype "passive"))
      (node (ref "U1_3") (pin "61") (pinfunction "VDDC61_61") (pintype "passive"))
      (node (ref "U1_3") (pin "62") (pinfunction "VDDC62_62") (pintype "passive"))
      (node (ref "U1_3") (pin "63") (pinfunction "VDDC63_63") (pintype "passive"))
      (node (ref "U1_3") (pin "64") (pinfunction "VDDC64_64") (pintype "passive"))
      (node (ref "U1_3") (pin "65") (pinfunction "VDDC65_65") (pintype "passive"))
      (node (ref "U1_3") (pin "66") (pinfunction "VDDC66_66") (pintype "passive"))
      (node (ref "U1_3") (pin "67") (pinfunction "VDDC67_67") (pintype "passive"))
      (node (ref "U1_3") (pin "68") (pinfunction "VDDC68_68") (pintype "passive"))
      (node (ref "U1_3") (pin "7") (pinfunction "VDDC7_7") (pintype "passive"))
      (node (ref "U1_3") (pin "8") (pinfunction "VDDC8_8") (pintype "passive"))
      (node (ref "U1_3") (pin "9") (pinfunction "VDDC9_9") (pintype "passive"))
      (node (ref "U1_4") (pin "1") (pinfunction "VDDC1_1") (pintype "passive"))
      (node (ref "U1_4") (pin "14") (pinfunction "VDDC14_14") (pintype "passive"))
      (node (ref "U1_4") (pin "15") (pinfunction "VDDC15_15") (pintype "passive"))
      (node (ref "U1_4") (pin "16") (pinfunction "VDDC16_16") (pintype "passive"))
      (node (ref "U1_4") (pin "17") (pinfunction "VDDC17_17") (pintype "passive"))
      (node (ref "U1_4") (pin "18") (pinfunction "VDDC18_18") (pintype "passive"))
      (node (ref "U1_4") (pin "19") (pinfunction "VDDC19_19") (pintype "passive"))
      (node (ref "U1_4") (pin "2") (pinfunction "VDDC2_2") (pintype "passive"))
      (node (ref "U1_4") (pin "20") (pinfunction "VDDC20_20") (pintype "passive"))
      (node (ref "U1_4") (pin "21") (pinfunction "VDDC21_21") (pintype "passive"))
      (node (ref "U1_4") (pin "22") (pinfunction "VDDC22_22") (pintype "passive"))
      (node (ref "U1_4") (pin "23") (pinfunction "VDDC23_23") (pintype "passive"))
      (node (ref "U1_4") (pin "24") (pinfunction "VDDC24_24") (pintype "passive"))
      (node (ref "U1_4") (pin "25") (pinfunction "VDDC25_25") (pintype "passive"))
      (node (ref "U1_4") (pin "26") (pinfunction "VDDC26_26") (pintype "passive"))
      (node (ref "U1_4") (pin "27") (pinfunction "VDDC27_27") (pintype "passive"))
      (node (ref "U1_4") (pin "28") (pinfunction "VDDC28_28") (pintype "passive"))
      (node (ref "U1_4") (pin "29") (pinfunction "VDDC29_29") (pintype "passive"))
      (node (ref "U1_4") (pin "3") (pinfunction "VDDC3_3") (pintype "passive"))
      (node (ref "U1_4") (pin "30") (pinfunction "VDDC30_30") (pintype "passive"))
      (node (ref "U1_4") (pin "31") (pinfunction "VDDC31_31") (pintype "passive"))
      (node (ref "U1_4") (pin "32") (pinfunction "VDDC32_32") (pintype "passive"))
      (node (ref "U1_4") (pin "33") (pinfunction "VDDC33_33") (pintype "passive"))
      (node (ref "U1_4") (pin "34") (pinfunction "VDDC34_34") (pintype "passive"))
      (node (ref "U1_4") (pin "35") (pinfunction "VDDC35_35") (pintype "passive"))
      (node (ref "U1_4") (pin "36") (pinfunction "VDDC36_36") (pintype "passive"))
      (node (ref "U1_4") (pin "37") (pinfunction "VDDC37_37") (pintype "passive"))
      (node (ref "U1_4") (pin "38") (pinfunction "VDDC38_38") (pintype "passive"))
      (node (ref "U1_4") (pin "4") (pinfunction "VDDC4_4") (pintype "passive"))
      (node (ref "U1_4") (pin "45") (pinfunction "VDDC45_45") (pintype "passive"))
      (node (ref "U1_4") (pin "46") (pinfunction "VDDC46_46") (pintype "passive"))
      (node (ref "U1_4") (pin "47") (pinfunction "VDDC47_47") (pintype "passive"))
      (node (ref "U1_4") (pin "48") (pinfunction "VDDC48_48") (pintype "passive"))
      (node (ref "U1_4") (pin "49") (pinfunction "VDDC49_49") (pintype "passive"))
      (node (ref "U1_4") (pin "5") (pinfunction "VDDC5_5") (pintype "passive"))
      (node (ref "U1_4") (pin "50") (pinfunction "VDDC50_50") (pintype "passive"))
      (node (ref "U1_4") (pin "51") (pinfunction "VDDC51_51") (pintype "passive"))
      (node (ref "U1_4") (pin "52") (pinfunction "VDDC52_52") (pintype "passive"))
      (node (ref "U1_4") (pin "53") (pinfunction "VDDC53_53") (pintype "passive"))
      (node (ref "U1_4") (pin "54") (pinfunction "VDDC54_54") (pintype "passive"))
      (node (ref "U1_4") (pin "55") (pinfunction "VDDC55_55") (pintype "passive"))
      (node (ref "U1_4") (pin "56") (pinfunction "VDDC56_56") (pintype "passive"))
      (node (ref "U1_4") (pin "57") (pinfunction "VDDC57_57") (pintype "passive"))
      (node (ref "U1_4") (pin "58") (pinfunction "VDDC58_58") (pintype "passive"))
      (node (ref "U1_4") (pin "59") (pinfunction "VDDC59_59") (pintype "passive"))
      (node (ref "U1_4") (pin "6") (pinfunction "VDDC6_6") (pintype "passive"))
      (node (ref "U1_4") (pin "60") (pinfunction "VDDC60_60") (pintype "passive"))
      (node (ref "U1_4") (pin "61") (pinfunction "VDDC61_61") (pintype "passive"))
      (node (ref "U1_4") (pin "62") (pinfunction "VDDC62_62") (pintype "passive"))
      (node (ref "U1_4") (pin "63") (pinfunction "VDDC63_63") (pintype "passive"))
      (node (ref "U1_4") (pin "64") (pinfunction "VDDC64_64") (pintype "passive"))
      (node (ref "U1_4") (pin "65") (pinfunction "VDDC65_65") (pintype "passive"))
      (node (ref "U1_4") (pin "66") (pinfunction "VDDC66_66") (pintype "passive"))
      (node (ref "U1_4") (pin "67") (pinfunction "VDDC67_67") (pintype "passive"))
      (node (ref "U1_4") (pin "68") (pinfunction "VDDC68_68") (pintype "passive"))
      (node (ref "U1_4") (pin "7") (pinfunction "VDDC7_7") (pintype "passive"))
      (node (ref "U1_4") (pin "8") (pinfunction "VDDC8_8") (pintype "passive"))
      (node (ref "U1_4") (pin "9") (pinfunction "VDDC9_9") (pintype "passive"))
      (node (ref "U1_5") (pin "1") (pinfunction "VDDC1_1") (pintype "passive"))
      (node (ref "U1_5") (pin "14") (pinfunction "VDDC14_14") (pintype "passive"))
      (node (ref "U1_5") (pin "15") (pinfunction "VDDC15_15") (pintype "passive"))
      (node (ref "U1_5") (pin "16") (pinfunction "VDDC16_16") (pintype "passive"))
      (node (ref "U1_5") (pin "17") (pinfunction "VDDC17_17") (pintype "passive"))
      (node (ref "U1_5") (pin "18") (pinfunction "VDDC18_18") (pintype "passive"))
      (node (ref "U1_5") (pin "19") (pinfunction "VDDC19_19") (pintype "passive"))
      (node (ref "U1_5") (pin "2") (pinfunction "VDDC2_2") (pintype "passive"))
      (node (ref "U1_5") (pin "20") (pinfunction "VDDC20_20") (pintype "passive"))
      (node (ref "U1_5") (pin "21") (pinfunction "VDDC21_21") (pintype "passive"))
      (node (ref "U1_5") (pin "22") (pinfunction "VDDC22_22") (pintype "passive"))
      (node (ref "U1_5") (pin "23") (pinfunction "VDDC23_23") (pintype "passive"))
      (node (ref "U1_5") (pin "24") (pinfunction "VDDC24_24") (pintype "passive"))
      (node (ref "U1_5") (pin "25") (pinfunction "VDDC25_25") (pintype "passive"))
      (node (ref "U1_5") (pin "26") (pinfunction "VDDC26_26") (pintype "passive"))
      (node (ref "U1_5") (pin "27") (pinfunction "VDDC27_27") (pintype "passive"))
      (node (ref "U1_5") (pin "28") (pinfunction "VDDC28_28") (pintype "passive"))
      (node (ref "U1_5") (pin "29") (pinfunction "VDDC29_29") (pintype "passive"))
      (node (ref "U1_5") (pin "3") (pinfunction "VDDC3_3") (pintype "passive"))
      (node (ref "U1_5") (pin "30") (pinfunction "VDDC30_30") (pintype "passive"))
      (node (ref "U1_5") (pin "31") (pinfunction "VDDC31_31") (pintype "passive"))
      (node (ref "U1_5") (pin "32") (pinfunction "VDDC32_32") (pintype "passive"))
      (node (ref "U1_5") (pin "33") (pinfunction "VDDC33_33") (pintype "passive"))
      (node (ref "U1_5") (pin "34") (pinfunction "VDDC34_34") (pintype "passive"))
      (node (ref "U1_5") (pin "35") (pinfunction "VDDC35_35") (pintype "passive"))
      (node (ref "U1_5") (pin "36") (pinfunction "VDDC36_36") (pintype "passive"))
      (node (ref "U1_5") (pin "37") (pinfunction "VDDC37_37") (pintype "passive"))
      (node (ref "U1_5") (pin "38") (pinfunction "VDDC38_38") (pintype "passive"))
      (node (ref "U1_5") (pin "4") (pinfunction "VDDC4_4") (pintype "passive"))
      (node (ref "U1_5") (pin "45") (pinfunction "VDDC45_45") (pintype "passive"))
      (node (ref "U1_5") (pin "46") (pinfunction "VDDC46_46") (pintype "passive"))
      (node (ref "U1_5") (pin "47") (pinfunction "VDDC47_47") (pintype "passive"))
      (node (ref "U1_5") (pin "48") (pinfunction "VDDC48_48") (pintype "passive"))
      (node (ref "U1_5") (pin "49") (pinfunction "VDDC49_49") (pintype "passive"))
      (node (ref "U1_5") (pin "5") (pinfunction "VDDC5_5") (pintype "passive"))
      (node (ref "U1_5") (pin "50") (pinfunction "VDDC50_50") (pintype "passive"))
      (node (ref "U1_5") (pin "51") (pinfunction "VDDC51_51") (pintype "passive"))
      (node (ref "U1_5") (pin "52") (pinfunction "VDDC52_52") (pintype "passive"))
      (node (ref "U1_5") (pin "53") (pinfunction "VDDC53_53") (pintype "passive"))
      (node (ref "U1_5") (pin "54") (pinfunction "VDDC54_54") (pintype "passive"))
      (node (ref "U1_5") (pin "55") (pinfunction "VDDC55_55") (pintype "passive"))
      (node (ref "U1_5") (pin "56") (pinfunction "VDDC56_56") (pintype "passive"))
      (node (ref "U1_5") (pin "57") (pinfunction "VDDC57_57") (pintype "passive"))
      (node (ref "U1_5") (pin "58") (pinfunction "VDDC58_58") (pintype "passive"))
      (node (ref "U1_5") (pin "59") (pinfunction "VDDC59_59") (pintype "passive"))
      (node (ref "U1_5") (pin "6") (pinfunction "VDDC6_6") (pintype "passive"))
      (node (ref "U1_5") (pin "60") (pinfunction "VDDC60_60") (pintype "passive"))
      (node (ref "U1_5") (pin "61") (pinfunction "VDDC61_61") (pintype "passive"))
      (node (ref "U1_5") (pin "62") (pinfunction "VDDC62_62") (pintype "passive"))
      (node (ref "U1_5") (pin "63") (pinfunction "VDDC63_63") (pintype "passive"))
      (node (ref "U1_5") (pin "64") (pinfunction "VDDC64_64") (pintype "passive"))
      (node (ref "U1_5") (pin "65") (pinfunction "VDDC65_65") (pintype "passive"))
      (node (ref "U1_5") (pin "66") (pinfunction "VDDC66_66") (pintype "passive"))
      (node (ref "U1_5") (pin "67") (pinfunction "VDDC67_67") (pintype "passive"))
      (node (ref "U1_5") (pin "68") (pinfunction "VDDC68_68") (pintype "passive"))
      (node (ref "U1_5") (pin "7") (pinfunction "VDDC7_7") (pintype "passive"))
      (node (ref "U1_5") (pin "8") (pinfunction "VDDC8_8") (pintype "passive"))
      (node (ref "U1_5") (pin "9") (pinfunction "VDDC9_9") (pintype "passive"))
      (node (ref "U1_6") (pin "1") (pinfunction "VDDC1_1") (pintype "passive"))
      (node (ref "U1_6") (pin "14") (pinfunction "VDDC14_14") (pintype "passive"))
      (node (ref "U1_6") (pin "15") (pinfunction "VDDC15_15") (pintype "passive"))
      (node (ref "U1_6") (pin "16") (pinfunction "VDDC16_16") (pintype "passive"))
      (node (ref "U1_6") (pin "17") (pinfunction "VDDC17_17") (pintype "passive"))
      (node (ref "U1_6") (pin "18") (pinfunction "VDDC18_18") (pintype "passive"))
      (node (ref "U1_6") (pin "19") (pinfunction "VDDC19_19") (pintype "passive"))
      (node (ref "U1_6") (pin "2") (pinfunction "VDDC2_2") (pintype "passive"))
      (node (ref "U1_6") (pin "20") (pinfunction "VDDC20_20") (pintype "passive"))
      (node (ref "U1_6") (pin "21") (pinfunction "VDDC21_21") (pintype "passive"))
      (node (ref "U1_6") (pin "22") (pinfunction "VDDC22_22") (pintype "passive"))
      (node (ref "U1_6") (pin "23") (pinfunction "VDDC23_23") (pintype "passive"))
      (node (ref "U1_6") (pin "24") (pinfunction "VDDC24_24") (pintype "passive"))
      (node (ref "U1_6") (pin "25") (pinfunction "VDDC25_25") (pintype "passive"))
      (node (ref "U1_6") (pin "26") (pinfunction "VDDC26_26") (pintype "passive"))
      (node (ref "U1_6") (pin "27") (pinfunction "VDDC27_27") (pintype "passive"))
      (node (ref "U1_6") (pin "28") (pinfunction "VDDC28_28") (pintype "passive"))
      (node (ref "U1_6") (pin "29") (pinfunction "VDDC29_29") (pintype "passive"))
      (node (ref "U1_6") (pin "3") (pinfunction "VDDC3_3") (pintype "passive"))
      (node (ref "U1_6") (pin "30") (pinfunction "VDDC30_30") (pintype "passive"))
      (node (ref "U1_6") (pin "31") (pinfunction "VDDC31_31") (pintype "passive"))
      (node (ref "U1_6") (pin "32") (pinfunction "VDDC32_32") (pintype "passive"))
      (node (ref "U1_6") (pin "33") (pinfunction "VDDC33_33") (pintype "passive"))
      (node (ref "U1_6") (pin "34") (pinfunction "VDDC34_34") (pintype "passive"))
      (node (ref "U1_6") (pin "35") (pinfunction "VDDC35_35") (pintype "passive"))
      (node (ref "U1_6") (pin "36") (pinfunction "VDDC36_36") (pintype "passive"))
      (node (ref "U1_6") (pin "37") (pinfunction "VDDC37_37") (pintype "passive"))
      (node (ref "U1_6") (pin "38") (pinfunction "VDDC38_38") (pintype "passive"))
      (node (ref "U1_6") (pin "4") (pinfunction "VDDC4_4") (pintype "passive"))
      (node (ref "U1_6") (pin "45") (pinfunction "VDDC45_45") (pintype "passive"))
      (node (ref "U1_6") (pin "46") (pinfunction "VDDC46_46") (pintype "passive"))
      (node (ref "U1_6") (pin "47") (pinfunction "VDDC47_47") (pintype "passive"))
      (node (ref "U1_6") (pin "48") (pinfunction "VDDC48_48") (pintype "passive"))
      (node (ref "U1_6") (pin "49") (pinfunction "VDDC49_49") (pintype "passive"))
      (node (ref "U1_6") (pin "5") (pinfunction "VDDC5_5") (pintype "passive"))
      (node (ref "U1_6") (pin "50") (pinfunction "VDDC50_50") (pintype "passive"))
      (node (ref "U1_6") (pin "51") (pinfunction "VDDC51_51") (pintype "passive"))
      (node (ref "U1_6") (pin "52") (pinfunction "VDDC52_52") (pintype "passive"))
      (node (ref "U1_6") (pin "53") (pinfunction "VDDC53_53") (pintype "passive"))
      (node (ref "U1_6") (pin "54") (pinfunction "VDDC54_54") (pintype "passive"))
      (node (ref "U1_6") (pin "55") (pinfunction "VDDC55_55") (pintype "passive"))
      (node (ref "U1_6") (pin "56") (pinfunction "VDDC56_56") (pintype "passive"))
      (node (ref "U1_6") (pin "57") (pinfunction "VDDC57_57") (pintype "passive"))
      (node (ref "U1_6") (pin "58") (pinfunction "VDDC58_58") (pintype "passive"))
      (node (ref "U1_6") (pin "59") (pinfunction "VDDC59_59") (pintype "passive"))
      (node (ref "U1_6") (pin "6") (pinfunction "VDDC6_6") (pintype "passive"))
      (node (ref "U1_6") (pin "60") (pinfunction "VDDC60_60") (pintype "passive"))
      (node (ref "U1_6") (pin "61") (pinfunction "VDDC61_61") (pintype "passive"))
      (node (ref "U1_6") (pin "62") (pinfunction "VDDC62_62") (pintype "passive"))
      (node (ref "U1_6") (pin "63") (pinfunction "VDDC63_63") (pintype "passive"))
      (node (ref "U1_6") (pin "64") (pinfunction "VDDC64_64") (pintype "passive"))
      (node (ref "U1_6") (pin "65") (pinfunction "VDDC65_65") (pintype "passive"))
      (node (ref "U1_6") (pin "66") (pinfunction "VDDC66_66") (pintype "passive"))
      (node (ref "U1_6") (pin "67") (pinfunction "VDDC67_67") (pintype "passive"))
      (node (ref "U1_6") (pin "68") (pinfunction "VDDC68_68") (pintype "passive"))
      (node (ref "U1_6") (pin "7") (pinfunction "VDDC7_7") (pintype "passive"))
      (node (ref "U1_6") (pin "8") (pinfunction "VDDC8_8") (pintype "passive"))
      (node (ref "U1_6") (pin "9") (pinfunction "VDDC9_9") (pintype "passive"))
      (node (ref "U1_7") (pin "1") (pinfunction "VDDC1_1") (pintype "passive"))
      (node (ref "U1_7") (pin "14") (pinfunction "VDDC14_14") (pintype "passive"))
      (node (ref "U1_7") (pin "15") (pinfunction "VDDC15_15") (pintype "passive"))
      (node (ref "U1_7") (pin "16") (pinfunction "VDDC16_16") (pintype "passive"))
      (node (ref "U1_7") (pin "17") (pinfunction "VDDC17_17") (pintype "passive"))
      (node (ref "U1_7") (pin "18") (pinfunction "VDDC18_18") (pintype "passive"))
      (node (ref "U1_7") (pin "19") (pinfunction "VDDC19_19") (pintype "passive"))
      (node (ref "U1_7") (pin "2") (pinfunction "VDDC2_2") (pintype "passive"))
      (node (ref "U1_7") (pin "20") (pinfunction "VDDC20_20") (pintype "passive"))
      (node (ref "U1_7") (pin "21") (pinfunction "VDDC21_21") (pintype "passive"))
      (node (ref "U1_7") (pin "22") (pinfunction "VDDC22_22") (pintype "passive"))
      (node (ref "U1_7") (pin "23") (pinfunction "VDDC23_23") (pintype "passive"))
      (node (ref "U1_7") (pin "24") (pinfunction "VDDC24_24") (pintype "passive"))
      (node (ref "U1_7") (pin "25") (pinfunction "VDDC25_25") (pintype "passive"))
      (node (ref "U1_7") (pin "26") (pinfunction "VDDC26_26") (pintype "passive"))
      (node (ref "U1_7") (pin "27") (pinfunction "VDDC27_27") (pintype "passive"))
      (node (ref "U1_7") (pin "28") (pinfunction "VDDC28_28") (pintype "passive"))
      (node (ref "U1_7") (pin "29") (pinfunction "VDDC29_29") (pintype "passive"))
      (node (ref "U1_7") (pin "3") (pinfunction "VDDC3_3") (pintype "passive"))
      (node (ref "U1_7") (pin "30") (pinfunction "VDDC30_30") (pintype "passive"))
      (node (ref "U1_7") (pin "31") (pinfunction "VDDC31_31") (pintype "passive"))
      (node (ref "U1_7") (pin "32") (pinfunction "VDDC32_32") (pintype "passive"))
      (node (ref "U1_7") (pin "33") (pinfunction "VDDC33_33") (pintype "passive"))
      (node (ref "U1_7") (pin "34") (pinfunction "VDDC34_34") (pintype "passive"))
      (node (ref "U1_7") (pin "35") (pinfunction "VDDC35_35") (pintype "passive"))
      (node (ref "U1_7") (pin "36") (pinfunction "VDDC36_36") (pintype "passive"))
      (node (ref "U1_7") (pin "37") (pinfunction "VDDC37_37") (pintype "passive"))
      (node (ref "U1_7") (pin "38") (pinfunction "VDDC38_38") (pintype "passive"))
      (node (ref "U1_7") (pin "4") (pinfunction "VDDC4_4") (pintype "passive"))
      (node (ref "U1_7") (pin "45") (pinfunction "VDDC45_45") (pintype "passive"))
      (node (ref "U1_7") (pin "46") (pinfunction "VDDC46_46") (pintype "passive"))
      (node (ref "U1_7") (pin "47") (pinfunction "VDDC47_47") (pintype "passive"))
      (node (ref "U1_7") (pin "48") (pinfunction "VDDC48_48") (pintype "passive"))
      (node (ref "U1_7") (pin "49") (pinfunction "VDDC49_49") (pintype "passive"))
      (node (ref "U1_7") (pin "5") (pinfunction "VDDC5_5") (pintype "passive"))
      (node (ref "U1_7") (pin "50") (pinfunction "VDDC50_50") (pintype "passive"))
      (node (ref "U1_7") (pin "51") (pinfunction "VDDC51_51") (pintype "passive"))
      (node (ref "U1_7") (pin "52") (pinfunction "VDDC52_52") (pintype "passive"))
      (node (ref "U1_7") (pin "53") (pinfunction "VDDC53_53") (pintype "passive"))
      (node (ref "U1_7") (pin "54") (pinfunction "VDDC54_54") (pintype "passive"))
      (node (ref "U1_7") (pin "55") (pinfunction "VDDC55_55") (pintype "passive"))
      (node (ref "U1_7") (pin "56") (pinfunction "VDDC56_56") (pintype "passive"))
      (node (ref "U1_7") (pin "57") (pinfunction "VDDC57_57") (pintype "passive"))
      (node (ref "U1_7") (pin "58") (pinfunction "VDDC58_58") (pintype "passive"))
      (node (ref "U1_7") (pin "59") (pinfunction "VDDC59_59") (pintype "passive"))
      (node (ref "U1_7") (pin "6") (pinfunction "VDDC6_6") (pintype "passive"))
      (node (ref "U1_7") (pin "60") (pinfunction "VDDC60_60") (pintype "passive"))
      (node (ref "U1_7") (pin "61") (pinfunction "VDDC61_61") (pintype "passive"))
      (node (ref "U1_7") (pin "62") (pinfunction "VDDC62_62") (pintype "passive"))
      (node (ref "U1_7") (pin "63") (pinfunction "VDDC63_63") (pintype "passive"))
      (node (ref "U1_7") (pin "64") (pinfunction "VDDC64_64") (pintype "passive"))
      (node (ref "U1_7") (pin "65") (pinfunction "VDDC65_65") (pintype "passive"))
      (node (ref "U1_7") (pin "66") (pinfunction "VDDC66_66") (pintype "passive"))
      (node (ref "U1_7") (pin "67") (pinfunction "VDDC67_67") (pintype "passive"))
      (node (ref "U1_7") (pin "68") (pinfunction "VDDC68_68") (pintype "passive"))
      (node (ref "U1_7") (pin "7") (pinfunction "VDDC7_7") (pintype "passive"))
      (node (ref "U1_7") (pin "8") (pinfunction "VDDC8_8") (pintype "passive"))
      (node (ref "U1_7") (pin "9") (pinfunction "VDDC9_9") (pintype "passive"))
      (node (ref "U1_8") (pin "1") (pinfunction "VDDC1_1") (pintype "passive"))
      (node (ref "U1_8") (pin "14") (pinfunction "VDDC14_14") (pintype "passive"))
      (node (ref "U1_8") (pin "15") (pinfunction "VDDC15_15") (pintype "passive"))
      (node (ref "U1_8") (pin "16") (pinfunction "VDDC16_16") (pintype "passive"))
      (node (ref "U1_8") (pin "17") (pinfunction "VDDC17_17") (pintype "passive"))
      (node (ref "U1_8") (pin "18") (pinfunction "VDDC18_18") (pintype "passive"))
      (node (ref "U1_8") (pin "19") (pinfunction "VDDC19_19") (pintype "passive"))
      (node (ref "U1_8") (pin "2") (pinfunction "VDDC2_2") (pintype "passive"))
      (node (ref "U1_8") (pin "20") (pinfunction "VDDC20_20") (pintype "passive"))
      (node (ref "U1_8") (pin "21") (pinfunction "VDDC21_21") (pintype "passive"))
      (node (ref "U1_8") (pin "22") (pinfunction "VDDC22_22") (pintype "passive"))
      (node (ref "U1_8") (pin "23") (pinfunction "VDDC23_23") (pintype "passive"))
      (node (ref "U1_8") (pin "24") (pinfunction "VDDC24_24") (pintype "passive"))
      (node (ref "U1_8") (pin "25") (pinfunction "VDDC25_25") (pintype "passive"))
      (node (ref "U1_8") (pin "26") (pinfunction "VDDC26_26") (pintype "passive"))
      (node (ref "U1_8") (pin "27") (pinfunction "VDDC27_27") (pintype "passive"))
      (node (ref "U1_8") (pin "28") (pinfunction "VDDC28_28") (pintype "passive"))
      (node (ref "U1_8") (pin "29") (pinfunction "VDDC29_29") (pintype "passive"))
      (node (ref "U1_8") (pin "3") (pinfunction "VDDC3_3") (pintype "passive"))
      (node (ref "U1_8") (pin "30") (pinfunction "VDDC30_30") (pintype "passive"))
      (node (ref "U1_8") (pin "31") (pinfunction "VDDC31_31") (pintype "passive"))
      (node (ref "U1_8") (pin "32") (pinfunction "VDDC32_32") (pintype "passive"))
      (node (ref "U1_8") (pin "33") (pinfunction "VDDC33_33") (pintype "passive"))
      (node (ref "U1_8") (pin "34") (pinfunction "VDDC34_34") (pintype "passive"))
      (node (ref "U1_8") (pin "35") (pinfunction "VDDC35_35") (pintype "passive"))
      (node (ref "U1_8") (pin "36") (pinfunction "VDDC36_36") (pintype "passive"))
      (node (ref "U1_8") (pin "37") (pinfunction "VDDC37_37") (pintype "passive"))
      (node (ref "U1_8") (pin "38") (pinfunction "VDDC38_38") (pintype "passive"))
      (node (ref "U1_8") (pin "4") (pinfunction "VDDC4_4") (pintype "passive"))
      (node (ref "U1_8") (pin "45") (pinfunction "VDDC45_45") (pintype "passive"))
      (node (ref "U1_8") (pin "46") (pinfunction "VDDC46_46") (pintype "passive"))
      (node (ref "U1_8") (pin "47") (pinfunction "VDDC47_47") (pintype "passive"))
      (node (ref "U1_8") (pin "48") (pinfunction "VDDC48_48") (pintype "passive"))
      (node (ref "U1_8") (pin "49") (pinfunction "VDDC49_49") (pintype "passive"))
      (node (ref "U1_8") (pin "5") (pinfunction "VDDC5_5") (pintype "passive"))
      (node (ref "U1_8") (pin "50") (pinfunction "VDDC50_50") (pintype "passive"))
      (node (ref "U1_8") (pin "51") (pinfunction "VDDC51_51") (pintype "passive"))
      (node (ref "U1_8") (pin "52") (pinfunction "VDDC52_52") (pintype "passive"))
      (node (ref "U1_8") (pin "53") (pinfunction "VDDC53_53") (pintype "passive"))
      (node (ref "U1_8") (pin "54") (pinfunction "VDDC54_54") (pintype "passive"))
      (node (ref "U1_8") (pin "55") (pinfunction "VDDC55_55") (pintype "passive"))
      (node (ref "U1_8") (pin "56") (pinfunction "VDDC56_56") (pintype "passive"))
      (node (ref "U1_8") (pin "57") (pinfunction "VDDC57_57") (pintype "passive"))
      (node (ref "U1_8") (pin "58") (pinfunction "VDDC58_58") (pintype "passive"))
      (node (ref "U1_8") (pin "59") (pinfunction "VDDC59_59") (pintype "passive"))
      (node (ref "U1_8") (pin "6") (pinfunction "VDDC6_6") (pintype "passive"))
      (node (ref "U1_8") (pin "60") (pinfunction "VDDC60_60") (pintype "passive"))
      (node (ref "U1_8") (pin "61") (pinfunction "VDDC61_61") (pintype "passive"))
      (node (ref "U1_8") (pin "62") (pinfunction "VDDC62_62") (pintype "passive"))
      (node (ref "U1_8") (pin "63") (pinfunction "VDDC63_63") (pintype "passive"))
      (node (ref "U1_8") (pin "64") (pinfunction "VDDC64_64") (pintype "passive"))
      (node (ref "U1_8") (pin "65") (pinfunction "VDDC65_65") (pintype "passive"))
      (node (ref "U1_8") (pin "66") (pinfunction "VDDC66_66") (pintype "passive"))
      (node (ref "U1_8") (pin "67") (pinfunction "VDDC67_67") (pintype "passive"))
      (node (ref "U1_8") (pin "68") (pinfunction "VDDC68_68") (pintype "passive"))
      (node (ref "U1_8") (pin "7") (pinfunction "VDDC7_7") (pintype "passive"))
      (node (ref "U1_8") (pin "8") (pinfunction "VDDC8_8") (pintype "passive"))
      (node (ref "U1_8") (pin "9") (pinfunction "VDDC9_9") (pintype "passive"))
      (node (ref "U1_9") (pin "1") (pinfunction "VDDC1_1") (pintype "passive"))
      (node (ref "U1_9") (pin "14") (pinfunction "VDDC14_14") (pintype "passive"))
      (node (ref "U1_9") (pin "15") (pinfunction "VDDC15_15") (pintype "passive"))
      (node (ref "U1_9") (pin "16") (pinfunction "VDDC16_16") (pintype "passive"))
      (node (ref "U1_9") (pin "17") (pinfunction "VDDC17_17") (pintype "passive"))
      (node (ref "U1_9") (pin "18") (pinfunction "VDDC18_18") (pintype "passive"))
      (node (ref "U1_9") (pin "19") (pinfunction "VDDC19_19") (pintype "passive"))
      (node (ref "U1_9") (pin "2") (pinfunction "VDDC2_2") (pintype "passive"))
      (node (ref "U1_9") (pin "20") (pinfunction "VDDC20_20") (pintype "passive"))
      (node (ref "U1_9") (pin "21") (pinfunction "VDDC21_21") (pintype "passive"))
      (node (ref "U1_9") (pin "22") (pinfunction "VDDC22_22") (pintype "passive"))
      (node (ref "U1_9") (pin "23") (pinfunction "VDDC23_23") (pintype "passive"))
      (node (ref "U1_9") (pin "24") (pinfunction "VDDC24_24") (pintype "passive"))
      (node (ref "U1_9") (pin "25") (pinfunction "VDDC25_25") (pintype "passive"))
      (node (ref "U1_9") (pin "26") (pinfunction "VDDC26_26") (pintype "passive"))
      (node (ref "U1_9") (pin "27") (pinfunction "VDDC27_27") (pintype "passive"))
      (node (ref "U1_9") (pin "28") (pinfunction "VDDC28_28") (pintype "passive"))
      (node (ref "U1_9") (pin "29") (pinfunction "VDDC29_29") (pintype "passive"))
      (node (ref "U1_9") (pin "3") (pinfunction "VDDC3_3") (pintype "passive"))
      (node (ref "U1_9") (pin "30") (pinfunction "VDDC30_30") (pintype "passive"))
      (node (ref "U1_9") (pin "31") (pinfunction "VDDC31_31") (pintype "passive"))
      (node (ref "U1_9") (pin "32") (pinfunction "VDDC32_32") (pintype "passive"))
      (node (ref "U1_9") (pin "33") (pinfunction "VDDC33_33") (pintype "passive"))
      (node (ref "U1_9") (pin "34") (pinfunction "VDDC34_34") (pintype "passive"))
      (node (ref "U1_9") (pin "35") (pinfunction "VDDC35_35") (pintype "passive"))
      (node (ref "U1_9") (pin "36") (pinfunction "VDDC36_36") (pintype "passive"))
      (node (ref "U1_9") (pin "37") (pinfunction "VDDC37_37") (pintype "passive"))
      (node (ref "U1_9") (pin "38") (pinfunction "VDDC38_38") (pintype "passive"))
      (node (ref "U1_9") (pin "4") (pinfunction "VDDC4_4") (pintype "passive"))
      (node (ref "U1_9") (pin "45") (pinfunction "VDDC45_45") (pintype "passive"))
      (node (ref "U1_9") (pin "46") (pinfunction "VDDC46_46") (pintype "passive"))
      (node (ref "U1_9") (pin "47") (pinfunction "VDDC47_47") (pintype "passive"))
      (node (ref "U1_9") (pin "48") (pinfunction "VDDC48_48") (pintype "passive"))
      (node (ref "U1_9") (pin "49") (pinfunction "VDDC49_49") (pintype "passive"))
      (node (ref "U1_9") (pin "5") (pinfunction "VDDC5_5") (pintype "passive"))
      (node (ref "U1_9") (pin "50") (pinfunction "VDDC50_50") (pintype "passive"))
      (node (ref "U1_9") (pin "51") (pinfunction "VDDC51_51") (pintype "passive"))
      (node (ref "U1_9") (pin "52") (pinfunction "VDDC52_52") (pintype "passive"))
      (node (ref "U1_9") (pin "53") (pinfunction "VDDC53_53") (pintype "passive"))
      (node (ref "U1_9") (pin "54") (pinfunction "VDDC54_54") (pintype "passive"))
      (node (ref "U1_9") (pin "55") (pinfunction "VDDC55_55") (pintype "passive"))
      (node (ref "U1_9") (pin "56") (pinfunction "VDDC56_56") (pintype "passive"))
      (node (ref "U1_9") (pin "57") (pinfunction "VDDC57_57") (pintype "passive"))
      (node (ref "U1_9") (pin "58") (pinfunction "VDDC58_58") (pintype "passive"))
      (node (ref "U1_9") (pin "59") (pinfunction "VDDC59_59") (pintype "passive"))
      (node (ref "U1_9") (pin "6") (pinfunction "VDDC6_6") (pintype "passive"))
      (node (ref "U1_9") (pin "60") (pinfunction "VDDC60_60") (pintype "passive"))
      (node (ref "U1_9") (pin "61") (pinfunction "VDDC61_61") (pintype "passive"))
      (node (ref "U1_9") (pin "62") (pinfunction "VDDC62_62") (pintype "passive"))
      (node (ref "U1_9") (pin "63") (pinfunction "VDDC63_63") (pintype "passive"))
      (node (ref "U1_9") (pin "64") (pinfunction "VDDC64_64") (pintype "passive"))
      (node (ref "U1_9") (pin "65") (pinfunction "VDDC65_65") (pintype "passive"))
      (node (ref "U1_9") (pin "66") (pinfunction "VDDC66_66") (pintype "passive"))
      (node (ref "U1_9") (pin "67") (pinfunction "VDDC67_67") (pintype "passive"))
      (node (ref "U1_9") (pin "68") (pinfunction "VDDC68_68") (pintype "passive"))
      (node (ref "U1_9") (pin "7") (pinfunction "VDDC7_7") (pintype "passive"))
      (node (ref "U1_9") (pin "8") (pinfunction "VDDC8_8") (pintype "passive"))
      (node (ref "U1_9") (pin "9") (pinfunction "VDDC9_9") (pintype "passive"))
    )
    (net (code "2") (name "/0.9V") (class "Default")
      (node (ref "C26") (pin "1") (pinfunction "1_1") (pintype "passive"))
      (node (ref "R29") (pin "2") (pinfunction "2_2") (pintype "passive"))
      (node (ref "R31") (pin "2") (pinfunction "2_2") (pintype "passive"))
      (node (ref "U1_1") (pin "10") (pinfunction "VDDPLLC_10") (pintype "passive"))
      (node (ref "U1_10") (pin "10") (pinfunction "VDDPLLC_10") (pintype "passive"))
      (node (ref "U1_11") (pin "10") (pinfunction "VDDPLLC_10") (pintype "passive"))
      (node (ref "U1_12") (pin "10") (pinfunction "VDDPLLC_10") (pintype "passive"))
      (node (ref "U1_13") (pin "10") (pinfunction "VDDPLLC_10") (pintype "passive"))
      (node (ref "U1_14") (pin "10") (pinfunction "VDDPLLC_10") (pintype "passive"))
      (node (ref "U1_15") (pin "10") (pinfunction "VDDPLLC_10") (pintype "passive"))
      (node (ref "U1_16") (pin "10") (pinfunction "VDDPLLC_10") (pintype "passive"))
      (node (ref "U1_2") (pin "10") (pinfunction "VDDPLLC_10") (pintype "passive"))
      (node (ref "U1_3") (pin "10") (pinfunction "VDDPLLC_10") (pintype "passive"))
      (node (ref "U1_4") (pin "10") (pinfunction "VDDPLLC_10") (pintype "passive"))
      (node (ref "U1_5") (pin "10") (pinfunction "VDDPLLC_10") (pintype "passive"))
      (node (ref "U1_6") (pin "10") (pinfunction "VDDPLLC_10") (pintype "passive"))
      (node (ref "U1_7") (pin "10") (pinfunction "VDDPLLC_10") (pintype "passive"))
      (node (ref "U1_8") (pin "10") (pinfunction "VDDPLLC_10") (pintype "passive"))
      (node (ref "U1_9") (pin "10") (pinfunction "VDDPLLC_10") (pintype "passive"))
    )
    (net (code "3") (name "/1.8V") (class "Default")
      (node (ref "C25") (pin "2") (pinfunction "2_2") (pintype "passive"))
      (node (ref "R29") (pin "1") (pinfunction "1_1") (pintype "passive"))
      (node (ref "U1_1") (pin "11") (pinfunction "VDDPLLIO_11") (pintype "passive"))
      (node (ref "U1_1") (pin "39") (pinfunction "VDDIO_39") (pintype "passive"))
      (node (ref "U1_10") (pin "11") (pinfunction "VDDPLLIO_11") (pintype "passive"))
      (node (ref "U1_10") (pin "39") (pinfunction "VDDIO_39") (pintype "passive"))
      (node (ref "U1_11") (pin "11") (pinfunction "VDDPLLIO_11") (pintype "passive"))
      (node (ref "U1_11") (pin "39") (pinfunction "VDDIO_39") (pintype "passive"))
      (node (ref "U1_12") (pin "11") (pinfunction "VDDPLLIO_11") (pintype "passive"))
      (node (ref "U1_12") (pin "39") (pinfunction "VDDIO_39") (pintype "passive"))
      (node (ref "U1_13") (pin "11") (pinfunction "VDDPLLIO_11") (pintype "passive"))
      (node (ref "U1_13") (pin "39") (pinfunction "VDDIO_39") (pintype "passive"))
      (node (ref "U1_14") (pin "11") (pinfunction "VDDPLLIO_11") (pintype "passive"))
      (node (ref "U1_14") (pin "39") (pinfunction "VDDIO_39") (pintype "passive"))
      (node (ref "U1_15") (pin "11") (pinfunction "VDDPLLIO_11") (pintype "passive"))
      (node (ref "U1_15") (pin "39") (pinfunction "VDDIO_39") (pintype "passive"))
      (node (ref "U1_16") (pin "11") (pinfunction "VDDPLLIO_11") (pintype "passive"))
      (node (ref "U1_16") (pin "39") (pinfunction "VDDIO_39") (pintype "passive"))
      (node (ref "U1_2") (pin "11") (pinfunction "VDDPLLIO_11") (pintype "passive"))
      (node (ref "U1_2") (pin "39") (pinfunction "VDDIO_39") (pintype "passive"))
      (node (ref "U1_3") (pin "11") (pinfunction "VDDPLLIO_11") (pintype "passive"))
      (node (ref "U1_3") (pin "39") (pinfunction "VDDIO_39") (pintype "passive"))
      (node (ref "U1_4") (pin "11") (pinfunction "VDDPLLIO_11") (pintype "passive"))
      (node (ref "U1_4") (pin "39") (pinfunction "VDDIO_39") (pintype "passive"))
      (node (ref "U1_5") (pin "11") (pinfunction "VDDPLLIO_11") (pintype "passive"))
      (node (ref "U1_5") (pin "39") (pinfunction "VDDIO_39") (pintype "passive"))
      (node (ref "U1_6") (pin "11") (pinfunction "VDDPLLIO_11") (pintype "passive"))
      (node (ref "U1_6") (pin "39") (pinfunction "VDDIO_39") (pintype "passive"))
      (node (ref "U1_7") (pin "11") (pinfunction "VDDPLLIO_11") (pintype "passive"))
      (node (ref "U1_7") (pin "39") (pinfunction "VDDIO_39") (pintype "passive"))
      (node (ref "U1_8") (pin "11") (pinfunction "VDDPLLIO_11") (pintype "passive"))
      (node (ref "U1_8") (pin "39") (pinfunction "VDDIO_39") (pintype "passive"))
      (node (ref "U1_9") (pin "11") (pinfunction "VDDPLLIO_11") (pintype "passive"))
      (node (ref "U1_9") (pin "39") (pinfunction "VDDIO_39") (pintype "passive"))
      (node (ref "U6") (pin "1") (pinfunction "OUTPUT_1") (pintype "passive"))
    )
    (net (code "4") (name "/3.3V") (class "Default")
      (node (ref "C10") (pin "1") (pinfunction "1_1") (pintype "passive"))
      (node (ref "C11") (pin "1") (pinfunction "1_1") (pintype "passive"))
      (node (ref "C16") (pin "1") (pinfunction "1_1") (pintype "passive"))
      (node (ref "C17") (pin "1") (pinfunction "1_1") (pintype "passive"))
      (node (ref "C4") (pin "1") (pinfunction "1_1") (pintype "passive"))
      (node (ref "C8") (pin "1") (pinfunction "1_1") (pintype "passive"))
      (node (ref "C9") (pin "1") (pinfunction "1_1") (pintype "passive"))
      (node (ref "J1") (pin "2") (pinfunction "2_2") (pintype "passive"))
      (node (ref "R1") (pin "1") (pinfunction "1_1") (pintype "passive"))
      (node (ref "R17") (pin "1") (pinfunction "1_1") (pintype "passive"))
      (node (ref "R22") (pin "2") (pinfunction "2_2") (pintype "passive"))
      (node (ref "R27") (pin "1") (pinfunction "1_1") (pintype "passive"))
      (node (ref "U1") (pin "10") (pinfunction "VDD_10") (pintype "passive"))
      (node (ref "U1") (pin "19") (pinfunction "AVDD_19") (pintype "passive"))
      (node (ref "U1") (pin "26") (pinfunction "VDD_26") (pintype "passive"))
      (node (ref "U1") (pin "35") (pinfunction "VUSB3V3_35") (pintype "passive"))
      (node (ref "U1") (pin "38") (pinfunction "VDD_38") (pintype "passive"))
      (node (ref "U1") (pin "57") (pinfunction "VDD_57") (pintype "passive"))
      (node (ref "U3") (pin "4") (pinfunction "NC_4") (pintype "passive"))
      (node (ref "U3") (pin "5") (pinfunction "Vout_5") (pintype "passive"))
      (node (ref "U7") (pin "1") (pinfunction "OUTPUT_1") (pintype "passive"))
    )
    (net (code "5") (name "/5.0V") (class "Default")
      (node (ref "C14") (pin "1") (pinfunction "1_1") (pintype "passive"))
      (node (ref "C1P_1") (pin "2") (pinfunction "2_2") (pintype "passive"))
      (node (ref "C1P_2") (pin "2") (pinfunction "2_2") (pintype "passive"))
      (node (ref "C1P_3") (pin "2") (pinfunction "2_2") (pintype "passive"))
      (node (ref "D1P_1") (pin "1") (pinfunction "A1_1") (pintype "passive"))
      (node (ref "D1P_1") (pin "2") (pinfunction "A2_2") (pintype "passive"))
      (node (ref "D1P_2") (pin "1") (pinfunction "A1_1") (pintype "passive"))
      (node (ref "D1P_2") (pin "2") (pinfunction "A2_2") (pintype "passive"))
      (node (ref "D1P_3") (pin "1") (pinfunction "A1_1") (pintype "passive"))
      (node (ref "D1P_3") (pin "2") (pinfunction "A2_2") (pintype "passive"))
      (node (ref "D7") (pin "1") (pinfunction "C_1") (pintype "passive"))
      (node (ref "D8") (pin "2") (pinfunction "A_2") (pintype "passive"))
      (node (ref "J3") (pin "1") (pinfunction "1_1") (pintype "passive"))
      (node (ref "R26") (pin "1") (pinfunction "1_1") (pintype "passive"))
      (node (ref "U1P_1") (pin "7") (pinfunction "VCC_7") (pintype "passive"))
      (node (ref "U1P_2") (pin "7") (pinfunction "VCC_7") (pintype "passive"))
      (node (ref "U1P_3") (pin "7") (pinfunction "VCC_7") (pintype "passive"))
      (node (ref "U2") (pin "1") (pinfunction "OUTPUT_1") (pintype "passive"))
      (node (ref "U4") (pin "3") (pinfunction "Vin_3") (pintype "passive"))
      (node (ref "U5") (pin "3") (pinfunction "Vin_3") (pintype "passive"))
    )
    (net (code "6") (name "/12V") (class "Default")
      (node (ref "C4P_1") (pin "1") (pinfunction "1_1") (pintype "passive"))
      (node (ref "C4P_2") (pin "1") (pinfunction "1_1") (pintype "passive"))
      (node (ref "C4P_3") (pin "1") (pinfunction "1_1") (pintype "passive"))
      (node (ref "C5P_1") (pin "1") (pinfunction "1_1") (pintype "passive"))
      (node (ref "C5P_2") (pin "1") (pinfunction "1_1") (pintype "passive"))
      (node (ref "C5P_3") (pin "1") (pinfunction "1_1") (pintype "passive"))
      (node (ref "D10") (pin "1") (pinfunction "C_1") (pintype "passive"))
      (node (ref "D9") (pin "2") (pinfunction "A_2") (pintype "passive"))
      (node (ref "J3") (pin "3") (pinfunction "3_3") (pintype "passive"))
      (node (ref "J4") (pin "2") (pinfunction "2_2") (pintype "passive"))
      (node (ref "J4") (pin "4") (pinfunction "4_4") (pintype "passive"))
      (node (ref "J4") (pin "6") (pinfunction "6_6") (pintype "passive"))
      (node (ref "Q1P_1") (pin "5") (pinfunction "D_5") (pintype "passive"))
      (node (ref "Q1P_1") (pin "6") (pinfunction "D_6") (pintype "passive"))
      (node (ref "Q1P_1") (pin "7") (pinfunction "D_7") (pintype "passive"))
      (node (ref "Q1P_1") (pin "8") (pinfunction "D_8") (pintype "passive"))
      (node (ref "Q1P_2") (pin "5") (pinfunction "D_5") (pintype "passive"))
      (node (ref "Q1P_2") (pin "6") (pinfunction "D_6") (pintype "passive"))
      (node (ref "Q1P_2") (pin "7") (pinfunction "D_7") (pintype "passive"))
      (node (ref "Q1P_2") (pin "8") (pinfunction "D_8") (pintype "passive"))
      (node (ref "Q1P_3") (pin "5") (pinfunction "D_5") (pintype "passive"))
      (node (ref "Q1P_3") (pin "6") (pinfunction "D_6") (pintype "passive"))
      (node (ref "Q1P_3") (pin "7") (pinfunction "D_7") (pintype "passive"))
      (node (ref "Q1P_3") (pin "8") (pinfunction "D_8") (pintype "passive"))
      (node (ref "R15") (pin "1") (pinfunction "1_1") (pintype "passive"))
      (node (ref "R28") (pin "2") (pinfunction "2_2") (pintype "passive"))
    )
    (net (code "7") (name "/BOOT1") (class "Default")
      (node (ref "C3P_1") (pin "1") (pinfunction "1_1") (pintype "passive"))
      (node (ref "D1P_1") (pin "3") (pinfunction "CC_3") (pintype "passive"))
      (node (ref "U1P_1") (pin "8") (pinfunction "BOOT_8") (pintype "passive"))
    )
    (net (code "8") (name "/BOOT2") (class "Default")
      (node (ref "C3P_2") (pin "1") (pinfunction "1_1") (pintype "passive"))
      (node (ref "D1P_2") (pin "3") (pinfunction "CC_3") (pintype "passive"))
      (node (ref "U1P_2") (pin "8") (pinfunction "BOOT_8") (pintype "passive"))
    )
    (net (code "9") (name "/BOOT3") (class "Default")
      (node (ref "C3P_3") (pin "1") (pinfunction "1_1") (pintype "passive"))
      (node (ref "D1P_3") (pin "3") (pinfunction "CC_3") (pintype "passive"))
      (node (ref "U1P_3") (pin "8") (pinfunction "BOOT_8") (pintype "passive"))
    )
    (net (code "10") (name "/CONFIG_N1_MCU") (class "Default")
      (node (ref "U1") (pin "42") (pinfunction "RTCC/DMLN/RPI72/RD8_42") (pintype "passive"))
    )
    (net (code "11") (name "/CONFIG_P1_MCU") (class "Default")
      (node (ref "U1") (pin "43") (pinfunction "ASDA1/DPLN/RPI73/RD9_43") (pintype "passive"))
    )
    (net (code "12") (name "/CSN4") (class "Default")
      (node (ref "U1") (pin "14") (pinfunction "AN2/C2IN2-/VMIO/RPI34/RB2_14") (pintype "passive"))
    )
    (net (code "13") (name "/CSP4") (class "Default")
      (node (ref "U1") (pin "13") (pinfunction "AN3/C2IN1+/VPIO/RPI35/RB3_13") (pintype "passive"))
    )
    (net (code "14") (name "/CompFB+") (class "Default")
      (node (ref "C5") (pin "1") (pinfunction "1_1") (pintype "passive"))
      (node (ref "R20") (pin "1") (pinfunction "1_1") (pintype "passive"))
      (node (ref "U1") (pin "11") (pinfunction "AN5/C1IN1+/VBUSON/VBUSST/RPI37/RB5_11") (pintype "passive"))
    )
    (net (code "15") (name "/CompFB-") (class "Default")
      (node (ref "C6") (pin "1") (pinfunction "1_1") (pintype "passive"))
      (node (ref "R21") (pin "1") (pinfunction "1_1") (pintype "passive"))
      (node (ref "U1") (pin "12") (pinfunction "AN4/C1IN2-/USBOEN/RPI36/RB4_12") (pintype "passive"))
    )
    (net (code "16") (name "/D+") (class "Default")
      (node (ref "D5") (pin "1") (pinfunction "C1_1") (pintype "passive"))
      (node (ref "J2") (pin "3") (pinfunction "3_3") (pintype "passive"))
      (node (ref "U1") (pin "37") (pinfunction "D+/RG2_37") (pintype "passive"))
    )
    (net (code "17") (name "/D-") (class "Default")
      (node (ref "D5") (pin "3") (pinfunction "C2_3") (pintype "passive"))
      (node (ref "J2") (pin "2") (pinfunction "2_2") (pintype "passive"))
      (node (ref "U1") (pin "36") (pinfunction "D-/RG3_36") (pintype "passive"))
    )
    (net (code "18") (name "/DRVLogic") (class "Default")
      (node (ref "C2P_1") (pin "1") (pinfunction "1_1") (pintype "passive"))
      (node (ref "C2P_2") (pin "1") (pinfunction "1_1") (pintype "passive"))
      (node (ref "C2P_3") (pin "1") (pinfunction "1_1") (pintype "passive"))
      (node (ref "R17") (pin "2") (pinfunction "2_2") (pintype "passive"))
      (node (ref "R19") (pin "1") (pinfunction "1_1") (pintype "passive"))
      (node (ref "U1") (pin "2") (pinfunction "AN30/PWM4L/PMD6/RPI86/RE6_2") (pintype "passive"))
      (node (ref "U1P_1") (pin "6") (pinfunction "Vlogic_6") (pintype "passive"))
      (node (ref "U1P_2") (pin "6") (pinfunction "Vlogic_6") (pintype "passive"))
      (node (ref "U1P_3") (pin "6") (pinfunction "Vlogic_6") (pintype "passive"))
    )
    (net (code "19") (name "/FB") (class "Default")
      (node (ref "C3") (pin "1") (pinfunction "1_1") (pintype "passive"))
      (node (ref "R18") (pin "1") (pinfunction "1_1") (pintype "passive"))
      (node (ref "U1") (pin "17") (pinfunction "PGEC1/AN6/RPI38/RB6_17") (pintype "passive"))
    )
    (net (code "20") (name "/GREEN") (class "Default")
      (node (ref "D2") (pin "2") (pinfunction "A_2") (pintype "passive"))
      (node (ref "U1") (pin "47") (pinfunction "PGED2/SOSCI/C3IN3-/RPI61/RC13_47") (pintype "passive"))
    )
    (net (code "21") (name "/HO1") (class "Default")
      (node (ref "Q1P_1") (pin "4") (pinfunction "G_4") (pintype "passive"))
      (node (ref "U1P_1") (pin "1") (pinfunction "HO_1") (pintype "passive"))
    )
    (net (code "22") (name "/HO2") (class "Default")
      (node (ref "Q1P_2") (pin "4") (pinfunction "G_4") (pintype "passive"))
      (node (ref "U1P_2") (pin "1") (pinfunction "HO_1") (pintype "passive"))
    )
    (net (code "23") (name "/HO3") (class "Default")
      (node (ref "Q1P_3") (pin "4") (pinfunction "G_4") (pintype "passive"))
      (node (ref "U1P_3") (pin "1") (pinfunction "HO_1") (pintype "passive"))
    )
    (net (code "24") (name "/LDO3.3V-5.0V") (class "Default")
      (node (ref "R27") (pin "2") (pinfunction "2_2") (pintype "passive"))
      (node (ref "R30") (pin "1") (pinfunction "1_1") (pintype "passive"))
      (node (ref "U6") (pin "5") (pinfunction "N.C._5") (pintype "passive"))
      (node (ref "U6") (pin "8") (pinfunction "INPUT_8") (pintype "passive"))
    )
    (net (code "25") (name "/LDO5.0V") (class "Default")
      (node (ref "C15") (pin "1") (pinfunction "1_1") (pintype "passive"))
      (node (ref "D7") (pin "2") (pinfunction "A_2") (pintype "passive"))
      (node (ref "D8") (pin "1") (pinfunction "C_1") (pintype "passive"))
      (node (ref "R25") (pin "1") (pinfunction "1_1") (pintype "passive"))
      (node (ref "R26") (pin "2") (pinfunction "2_2") (pintype "passive"))
      (node (ref "R30") (pin "2") (pinfunction "2_2") (pintype "passive"))
      (node (ref "U3") (pin "1") (pinfunction "Vin_1") (pintype "passive"))
      (node (ref "U3") (pin "3") (pinfunction "STBY_3") (pintype "passive"))
      (node (ref "U7") (pin "5") (pinfunction "N.C._5") (pintype "passive"))
      (node (ref "U7") (pin "8") (pinfunction "INPUT_8") (pintype "passive"))
    )
    (net (code "26") (name "/LM12V") (class "Default")
      (node (ref "D9") (pin "1") (pinfunction "C_1") (pintype "passive"))
      (node (ref "R28") (pin "1") (pinfunction "1_1") (pintype "passive"))
      (node (ref "U2") (pin "8") (pinfunction "INPUT_8") (pintype "passive"))
      (node (ref "U4") (pin "1") (pinfunction "Vout_1") (pintype "passive"))
      (node (ref "U5") (pin "1") (pinfunction "Vout_1") (pintype "passive"))
    )
    (net (code "27") (name "/LO1") (class "Default")
      (node (ref "Q2P_1") (pin "4") (pinfunction "G_4") (pintype "passive"))
      (node (ref "Q3P_1") (pin "4") (pinfunction "G_4") (pintype "passive"))
      (node (ref "U1P_1") (pin "3") (pinfunction "LO_3") (pintype "passive"))
    )
    (net (code "28") (name "/LO2") (class "Default")
      (node (ref "Q2P_2") (pin "4") (pinfunction "G_4") (pintype "passive"))
      (node (ref "Q3P_2") (pin "4") (pinfunction "G_4") (pintype "passive"))
      (node (ref "U1P_2") (pin "3") (pinfunction "LO_3") (pintype "passive"))
    )
    (net (code "29") (name "/LO3") (class "Default")
      (node (ref "Q2P_3") (pin "4") (pinfunction "G_4") (pintype "passive"))
      (node (ref "Q3P_3") (pin "4") (pinfunction "G_4") (pintype "passive"))
      (node (ref "U1P_3") (pin "3") (pinfunction "LO_3") (pintype "passive"))
    )
    (net (code "30") (name "/MCLR") (class "Default")
      (node (ref "C7") (pin "1") (pinfunction "1_1") (pintype "passive"))
      (node (ref "J1") (pin "1") (pinfunction "1_1") (pintype "passive"))
      (node (ref "R22") (pin "1") (pinfunction "1_1") (pintype "passive"))
      (node (ref "U1") (pin "7") (pinfunction "MCLR_7") (pintype "passive"))
    )
    (net (code "31") (name "/MCU5.0V") (class "Default")
      (node (ref "R23") (pin "2") (pinfunction "2_2") (pintype "passive"))
      (node (ref "U1") (pin "34") (pinfunction "VBUS_34") (pintype "passive"))
    )
    (net (code "32") (name "/MCU_MISO0") (class "Default")
      (node (ref "Q1") (pin "3") (pinfunction "C_3") (pintype "passive"))
      (node (ref "R1") (pin "2") (pinfunction "2_2") (pintype "passive"))
      (node (ref "U1") (pin "5") (pinfunction "C1IN1-/SDI2/PMA4/RPI119/RG7_5") (pintype "passive"))
    )
    (net (code "33") (name "/MCU_MOSI0") (class "Default")
      (node (ref "R6") (pin "2") (pinfunction "2_2") (pintype "passive"))
      (node (ref "U1") (pin "6") (pinfunction "C2IN3-/SDO2/PMA3/RP120/RG8_6") (pintype "passive"))
    )
    (net (code "34") (name "/MCU_SCK0") (class "Default")
      (node (ref "R4") (pin "2") (pinfunction "2_2") (pintype "passive"))
      (node (ref "U1") (pin "4") (pinfunction "C1IN3-/SCK2/PMA5/RP118/RG6_4") (pintype "passive"))
    )
    (net (code "35") (name "/MEAS12") (class "Default")
      (node (ref "C2") (pin "1") (pinfunction "1_1") (pintype "passive"))
      (node (ref "R15") (pin "2") (pinfunction "2_2") (pintype "passive"))
      (node (ref "R16") (pin "2") (pinfunction "2_2") (pintype "passive"))
      (node (ref "U1") (pin "18") (pinfunction "PGED1/AN7/RCV/RPI39/RB7_18") (pintype "passive"))
    )
    (net (code "36") (name "/Main OSC In") (class "Default")
      (node (ref "C12") (pin "1") (pinfunction "1_1") (pintype "passive"))
      (node (ref "U1") (pin "39") (pinfunction "OSC1/RPI60/RC12_39") (pintype "passive"))
      (node (ref "Y1") (pin "1") (pinfunction "1_1") (pintype "passive"))
    )
    (net (code "37") (name "/Main OSC Out") (class "Default")
      (node (ref "C13") (pin "1") (pinfunction "1_1") (pintype "passive"))
      (node (ref "U1") (pin "40") (pinfunction "OSC2/CLKO/RC15_40") (pintype "passive"))
      (node (ref "Y1") (pin "2") (pinfunction "2_2") (pintype "passive"))
    )
    (net (code "38") (name "/ORANGE") (class "Default")
      (node (ref "D4") (pin "2") (pinfunction "A_2") (pintype "passive"))
      (node (ref "U1") (pin "45") (pinfunction "PMCS1/RPI75/RD11_45") (pintype "passive"))
    )
    (net (code "39") (name "/PGC") (class "Default")
      (node (ref "J1") (pin "5") (pinfunction "5_5") (pintype "passive"))
      (node (ref "U1") (pin "15") (pinfunction "PGEC3/AN1/VREF-/RPI33/RB1_15") (pintype "passive"))
    )
    (net (code "40") (name "/PGD") (class "Default")
      (node (ref "J1") (pin "4") (pinfunction "4_4") (pintype "passive"))
      (node (ref "U1") (pin "16") (pinfunction "PGED3/AN0/VREF+/RPI32/RB0_16") (pintype "passive"))
    )
    (net (code "41") (name "/PWM1H") (class "Default")
      (node (ref "U1") (pin "61") (pinfunction "AN25/PWM1H/PMD1/RPI81/RE1_61") (pintype "passive"))
    )
    (net (code "42") (name "/PWM1L") (class "Default")
      (node (ref "U1") (pin "60") (pinfunction "AN24/PWM1L/PMD0/RP80/RE0_60") (pintype "passive"))
    )
    (net (code "43") (name "/PWM2H") (class "Default")
      (node (ref "R10") (pin "1") (pinfunction "1_1") (pintype "passive"))
      (node (ref "U1") (pin "63") (pinfunction "AN27/PWM2H/PMD3/RPI83/RE3_63") (pintype "passive"))
      (node (ref "U1P_2") (pin "5") (pinfunction "IN_5") (pintype "passive"))
    )
    (net (code "44") (name "/PWM2L") (class "Default")
      (node (ref "R11") (pin "1") (pinfunction "1_1") (pintype "passive"))
      (node (ref "U1") (pin "62") (pinfunction "AN26/PWM2L/PMD2/RP82/RE2_62") (pintype "passive"))
      (node (ref "U1P_1") (pin "5") (pinfunction "IN_5") (pintype "passive"))
    )
    (net (code "45") (name "/PWM3H") (class "Default")
      (node (ref "R12") (pin "2") (pinfunction "2_2") (pintype "passive"))
      (node (ref "U1") (pin "1") (pinfunction "AN29/PWM3H/PMD5/RP85/RE5_1") (pintype "passive"))
    )
    (net (code "46") (name "/PWM3L") (class "Default")
      (node (ref "R9") (pin "1") (pinfunction "1_1") (pintype "passive"))
      (node (ref "U1") (pin "64") (pinfunction "AN28/PWM3L/PMD4/RP84/RE4_64") (pintype "passive"))
      (node (ref "U1P_3") (pin "5") (pinfunction "IN_5") (pintype "passive"))
    )
    (net (code "47") (name "/RED") (class "Default")
      (node (ref "D1") (pin "2") (pinfunction "A_2") (pintype "passive"))
      (node (ref "U1") (pin "48") (pinfunction "PGEC2/SOSCO/C3IN1-/T1CK/RPI62/RC14_48") (pintype "passive"))
    )
    (net (code "48") (name "/REPORT_N") (class "Default")
      (node (ref "U1") (pin "51") (pinfunction "PMBE/RP67/RD3_51") (pintype "passive"))
    )
    (net (code "49") (name "/REPORT_P") (class "Default")
      (node (ref "U1") (pin "50") (pinfunction "DPH/RP66/RD2_50") (pintype "passive"))
    )
    (net (code "50") (name "/RESET") (class "Default")
      (node (ref "R13") (pin "2") (pinfunction "2_2") (pintype "passive"))
      (node (ref "R3") (pin "1") (pinfunction "1_1") (pintype "passive"))
      (node (ref "U1_1") (pin "42") (pinfunction "RST_N_42") (pintype "passive"))
      (node (ref "U1_10") (pin "42") (pinfunction "RST_N_42") (pintype "passive"))
      (node (ref "U1_11") (pin "42") (pinfunction "RST_N_42") (pintype "passive"))
      (node (ref "U1_12") (pin "42") (pinfunction "RST_N_42") (pintype "passive"))
      (node (ref "U1_13") (pin "42") (pinfunction "RST_N_42") (pintype "passive"))
      (node (ref "U1_14") (pin "42") (pinfunction "RST_N_42") (pintype "passive"))
      (node (ref "U1_15") (pin "42") (pinfunction "RST_N_42") (pintype "passive"))
      (node (ref "U1_16") (pin "42") (pinfunction "RST_N_42") (pintype "passive"))
      (node (ref "U1_2") (pin "42") (pinfunction "RST_N_42") (pintype "passive"))
      (node (ref "U1_3") (pin "42") (pinfunction "RST_N_42") (pintype "passive"))
      (node (ref "U1_4") (pin "42") (pinfunction "RST_N_42") (pintype "passive"))
      (node (ref "U1_5") (pin "42") (pinfunction "RST_N_42") (pintype "passive"))
      (node (ref "U1_6") (pin "42") (pinfunction "RST_N_42") (pintype "passive"))
      (node (ref "U1_7") (pin "42") (pinfunction "RST_N_42") (pintype "passive"))
      (node (ref "U1_8") (pin "42") (pinfunction "RST_N_42") (pintype "passive"))
      (node (ref "U1_9") (pin "42") (pinfunction "RST_N_42") (pintype "passive"))
    )
    (net (code "51") (name "/RESET_MCU") (class "Default")
      (node (ref "R3") (pin "2") (pinfunction "2_2") (pintype "passive"))
      (node (ref "U1") (pin "3") (pinfunction "AN31/PWM4H/PMD7/RP87/RE7_3") (pintype "passive"))
    )
    (net (code "52") (name "/SPI_CLK") (class "Default")
      (node (ref "R4") (pin "1") (pinfunction "1_1") (pintype "passive"))
      (node (ref "R5") (pin "2") (pinfunction "2_2") (pintype "passive"))
      (node (ref "U1_1") (pin "41") (pinfunction "SER_CLK_41") (pintype "passive"))
      (node (ref "U1_10") (pin "41") (pinfunction "SER_CLK_41") (pintype "passive"))
      (node (ref "U1_11") (pin "41") (pinfunction "SER_CLK_41") (pintype "passive"))
      (node (ref "U1_12") (pin "41") (pinfunction "SER_CLK_41") (pintype "passive"))
      (node (ref "U1_13") (pin "41") (pinfunction "SER_CLK_41") (pintype "passive"))
      (node (ref "U1_14") (pin "41") (pinfunction "SER_CLK_41") (pintype "passive"))
      (node (ref "U1_15") (pin "41") (pinfunction "SER_CLK_41") (pintype "passive"))
      (node (ref "U1_16") (pin "41") (pinfunction "SER_CLK_41") (pintype "passive"))
      (node (ref "U1_2") (pin "41") (pinfunction "SER_CLK_41") (pintype "passive"))
      (node (ref "U1_3") (pin "41") (pinfunction "SER_CLK_41") (pintype "passive"))
      (node (ref "U1_4") (pin "41") (pinfunction "SER_CLK_41") (pintype "passive"))
      (node (ref "U1_5") (pin "41") (pinfunction "SER_CLK_41") (pintype "passive"))
      (node (ref "U1_6") (pin "41") (pinfunction "SER_CLK_41") (pintype "passive"))
      (node (ref "U1_7") (pin "41") (pinfunction "SER_CLK_41") (pintype "passive"))
      (node (ref "U1_8") (pin "41") (pinfunction "SER_CLK_41") (pintype "passive"))
      (node (ref "U1_9") (pin "41") (pinfunction "SER_CLK_41") (pintype "passive"))
    )
    (net (code "53") (name "/SPI_DATA1") (class "Default")
      (node (ref "R6") (pin "1") (pinfunction "1_1") (pintype "passive"))
      (node (ref "R7") (pin "2") (pinfunction "2_2") (pintype "passive"))
      (node (ref "U1_1") (pin "43") (pinfunction "SERIN_43") (pintype "passive"))
    )
    (net (code "54") (name "/SPI_DATA2") (class "Default")
      (node (ref "U1_1") (pin "44") (pinfunction "SEROUT_44") (pintype "passive"))
      (node (ref "U1_2") (pin "43") (pinfunction "SERIN_43") (pintype "passive"))
    )
    (net (code "55") (name "/SPI_DATA3") (class "Default")
      (node (ref "U1_2") (pin "44") (pinfunction "SEROUT_44") (pintype "passive"))
      (node (ref "U1_3") (pin "43") (pinfunction "SERIN_43") (pintype "passive"))
    )
    (net (code "56") (name "/SPI_DATA4") (class "Default")
      (node (ref "U1_3") (pin "44") (pinfunction "SEROUT_44") (pintype "passive"))
      (node (ref "U1_4") (pin "43") (pinfunction "SERIN_43") (pintype "passive"))
    )
    (net (code "57") (name "/SPI_DATA5") (class "Default")
      (node (ref "U1_4") (pin "44") (pinfunction "SEROUT_44") (pintype "passive"))
      (node (ref "U1_5") (pin "43") (pinfunction "SERIN_43") (pintype "passive"))
    )
    (net (code "58") (name "/SPI_DATA6") (class "Default")
      (node (ref "U1_5") (pin "44") (pinfunction "SEROUT_44") (pintype "passive"))
      (node (ref "U1_6") (pin "43") (pinfunction "SERIN_43") (pintype "passive"))
    )
    (net (code "59") (name "/SPI_DATA7") (class "Default")
      (node (ref "U1_6") (pin "44") (pinfunction "SEROUT_44") (pintype "passive"))
      (node (ref "U1_7") (pin "43") (pinfunction "SERIN_43") (pintype "passive"))
    )
    (net (code "60") (name "/SPI_DATA8") (class "Default")
      (node (ref "U1_7") (pin "44") (pinfunction "SEROUT_44") (pintype "passive"))
      (node (ref "U1_8") (pin "43") (pinfunction "SERIN_43") (pintype "passive"))
    )
    (net (code "61") (name "/SPI_DATA9") (class "Default")
      (node (ref "U1_8") (pin "44") (pinfunction "SEROUT_44") (pintype "passive"))
      (node (ref "U1_9") (pin "43") (pinfunction "SERIN_43") (pintype "passive"))
    )
    (net (code "62") (name "/SPI_DATA10") (class "Default")
      (node (ref "U1_10") (pin "43") (pinfunction "SERIN_43") (pintype "passive"))
      (node (ref "U1_9") (pin "44") (pinfunction "SEROUT_44") (pintype "passive"))
    )
    (net (code "63") (name "/SPI_DATA11") (class "Default")
      (node (ref "U1_10") (pin "44") (pinfunction "SEROUT_44") (pintype "passive"))
      (node (ref "U1_11") (pin "43") (pinfunction "SERIN_43") (pintype "passive"))
    )
    (net (code "64") (name "/SPI_DATA12") (class "Default")
      (node (ref "U1_11") (pin "44") (pinfunction "SEROUT_44") (pintype "passive"))
      (node (ref "U1_12") (pin "43") (pinfunction "SERIN_43") (pintype "passive"))
    )
    (net (code "65") (name "/SPI_DATA13") (class "Default")
      (node (ref "U1_12") (pin "44") (pinfunction "SEROUT_44") (pintype "passive"))
      (node (ref "U1_13") (pin "43") (pinfunction "SERIN_43") (pintype "passive"))
    )
    (net (code "66") (name "/SPI_DATA14") (class "Default")
      (node (ref "U1_13") (pin "44") (pinfunction "SEROUT_44") (pintype "passive"))
      (node (ref "U1_14") (pin "43") (pinfunction "SERIN_43") (pintype "passive"))
    )
    (net (code "67") (name "/SPI_DATA15") (class "Default")
      (node (ref "U1_14") (pin "44") (pinfunction "SEROUT_44") (pintype "passive"))
      (node (ref "U1_15") (pin "43") (pinfunction "SERIN_43") (pintype "passive"))
    )
    (net (code "68") (name "/SPI_DATA16") (class "Default")
      (node (ref "U1_15") (pin "44") (pinfunction "SEROUT_44") (pintype "passive"))
      (node (ref "U1_16") (pin "43") (pinfunction "SERIN_43") (pintype "passive"))
    )
    (net (code "69") (name "/SPI_DATA17") (class "Default")
      (node (ref "Q1") (pin "1") (pinfunction "B_1") (pintype "passive"))
      (node (ref "U1_16") (pin "44") (pinfunction "SEROUT_44") (pintype "passive"))
    )
    (net (code "70") (name "/SWN1") (class "Default")
      (node (ref "C3P_1") (pin "2") (pinfunction "2_2") (pintype "passive"))
      (node (ref "L1P_1") (pin "1") (pinfunction "1_1") (pintype "passive"))
      (node (ref "Q1P_1") (pin "1") (pinfunction "S_1") (pintype "passive"))
      (node (ref "Q1P_1") (pin "2") (pinfunction "S_2") (pintype "passive"))
      (node (ref "Q1P_1") (pin "3") (pinfunction "S_3") (pintype "passive"))
      (node (ref "Q2P_1") (pin "5") (pinfunction "D_5") (pintype "passive"))
      (node (ref "Q2P_1") (pin "6") (pinfunction "D_6") (pintype "passive"))
      (node (ref "Q2P_1") (pin "7") (pinfunction "D_7") (pintype "passive"))
      (node (ref "Q2P_1") (pin "8") (pinfunction "D_8") (pintype "passive"))
      (node (ref "Q3P_1") (pin "5") (pinfunction "D_5") (pintype "passive"))
      (node (ref "Q3P_1") (pin "6") (pinfunction "D_6") (pintype "passive"))
      (node (ref "Q3P_1") (pin "7") (pinfunction "D_7") (pintype "passive"))
      (node (ref "Q3P_1") (pin "8") (pinfunction "D_8") (pintype "passive"))
      (node (ref "U1P_1") (pin "2") (pinfunction "SW_2") (pintype "passive"))
    )
    (net (code "71") (name "/SWN2") (class "Default")
      (node (ref "C3P_2") (pin "2") (pinfunction "2_2") (pintype "passive"))
      (node (ref "L1P_2") (pin "1") (pinfunction "1_1") (pintype "passive"))
      (node (ref "Q1P_2") (pin "1") (pinfunction "S_1") (pintype "passive"))
      (node (ref "Q1P_2") (pin "2") (pinfunction "S_2") (pintype "passive"))
      (node (ref "Q1P_2") (pin "3") (pinfunction "S_3") (pintype "passive"))
      (node (ref "Q2P_2") (pin "5") (pinfunction "D_5") (pintype "passive"))
      (node (ref "Q2P_2") (pin "6") (pinfunction "D_6") (pintype "passive"))
      (node (ref "Q2P_2") (pin "7") (pinfunction "D_7") (pintype "passive"))
      (node (ref "Q2P_2") (pin "8") (pinfunction "D_8") (pintype "passive"))
      (node (ref "Q3P_2") (pin "5") (pinfunction "D_5") (pintype "passive"))
      (node (ref "Q3P_2") (pin "6") (pinfunction "D_6") (pintype "passive"))
      (node (ref "Q3P_2") (pin "7") (pinfunction "D_7") (pintype "passive"))
      (node (ref "Q3P_2") (pin "8") (pinfunction "D_8") (pintype "passive"))
      (node (ref "U1P_2") (pin "2") (pinfunction "SW_2") (pintype "passive"))
    )
    (net (code "72") (name "/SWN3") (class "Default")
      (node (ref "C3P_3") (pin "2") (pinfunction "2_2") (pintype "passive"))
      (node (ref "L1P_3") (pin "1") (pinfunction "1_1") (pintype "passive"))
      (node (ref "Q1P_3") (pin "1") (pinfunction "S_1") (pintype "passive"))
      (node (ref "Q1P_3") (pin "2") (pinfunction "S_2") (pintype "passive"))
      (node (ref "Q1P_3") (pin "3") (pinfunction "S_3") (pintype "passive"))
      (node (ref "Q2P_3") (pin "5") (pinfunction "D_5") (pintype "passive"))
      (node (ref "Q2P_3") (pin "6") (pinfunction "D_6") (pintype "passive"))
      (node (ref "Q2P_3") (pin "7") (pinfunction "D_7") (pintype "passive"))
      (node (ref "Q2P_3") (pin "8") (pinfunction "D_8") (pintype "passive"))
      (node (ref "Q3P_3") (pin "5") (pinfunction "D_5") (pintype "passive"))
      (node (ref "Q3P_3") (pin "6") (pinfunction "D_6") (pintype "passive"))
      (node (ref "Q3P_3") (pin "7") (pinfunction "D_7") (pintype "passive"))
      (node (ref "Q3P_3") (pin "8") (pinfunction "D_8") (pintype "passive"))
      (node (ref "U1P_3") (pin "2") (pinfunction "SW_2") (pintype "passive"))
    )
    (net (code "73") (name "/TP1") (class "Default")
      (node (ref "U1") (pin "54") (pinfunction "C3IN2-/RP70/RD6_54") (pintype "passive"))
    )
    (net (code "74") (name "/TP1_1") (class "Default")
      (node (ref "U1") (pin "59") (pinfunction "VCMPST2/RP97/RF1_59") (pintype "passive"))
    )
    (net (code "75") (name "/TP1_2") (class "Default")
      (node (ref "U1") (pin "58") (pinfunction "VCMPST1/RP96/RF0_58") (pintype "passive"))
    )
    (net (code "76") (name "/TP2") (class "Default")
      (node (ref "U1") (pin "55") (pinfunction "C3IN1+/VCMPST3/RP71/RD7_55") (pintype "passive"))
    )
    (net (code "77") (name "/TP8") (class "Default")
      (node (ref "U1") (pin "33") (pinfunction "USBID/RP99/RF3_33") (pintype "passive"))
    )
    (net (code "78") (name "/TP9") (class "Default")
      (node (ref "U1") (pin "30") (pinfunction "AN15/PMA0/RPI47/RB15_30") (pintype "passive"))
    )
    (net (code "79") (name "/TP10") (class "Default")
      (node (ref "U1") (pin "29") (pinfunction "AN14/PMA1/RPI46/RB14_29") (pintype "passive"))
    )
    (net (code "80") (name "/TP11") (class "Default")
      (node (ref "U1") (pin "28") (pinfunction "TDI/AN13/PMA10/RPI45/RB13_28") (pintype "passive"))
    )
    (net (code "81") (name "/TP12") (class "Default")
      (node (ref "U1") (pin "27") (pinfunction "TCK/AN12/PMA11/RPI44/RB12_27") (pintype "passive"))
    )
    (net (code "82") (name "/TP13") (class "Default")
      (node (ref "U1") (pin "24") (pinfunction "TDO/AN11/PMA12/RPI43/RB11_24") (pintype "passive"))
    )
    (net (code "83") (name "/TP14") (class "Default")
      (node (ref "U1") (pin "23") (pinfunction "TMS/AN10/CVREF/PMA13/RPI42/RB10_23") (pintype "passive"))
    )
    (net (code "84") (name "/TP15") (class "Default")
      (node (ref "U1") (pin "22") (pinfunction "AN9/PMA7//RPI41/RB9_22") (pintype "passive"))
    )
    (net (code "85") (name "/TP16") (class "Default")
      (node (ref "U1") (pin "21") (pinfunction "AN8/PMA6/RPI40/RB8_21") (pintype "passive"))
    )
    (net (code "86") (name "/TP17") (class "Default")
      (node (ref "U1") (pin "8") (pinfunction "C2IN1-/PMA2/RPI121/RG9_8") (pintype "passive"))
    )
    (net (code "87") (name "/U2Rx") (class "Default")
      (node (ref "U1") (pin "31") (pinfunction "SDA2/PMA9/RP100/RF4_31") (pintype "passive"))
    )
    (net (code "88") (name "/U2Tx") (class "Default")
      (node (ref "U1") (pin "32") (pinfunction "SCL2/PMA8/RP101/RF5_32") (pintype "passive"))
    )
    (net (code "89") (name "/USB5.0V") (class "Default")
      (node (ref "D5") (pin "4") (pinfunction "C3_4") (pintype "passive"))
      (node (ref "D5") (pin "6") (pinfunction "C4_6") (pintype "passive"))
      (node (ref "J2") (pin "1") (pinfunction "1_1") (pintype "passive"))
      (node (ref "R23") (pin "1") (pinfunction "1_1") (pintype "passive"))
      (node (ref "R25") (pin "2") (pinfunction "2_2") (pintype "passive"))
    )
    (net (code "90") (name "/VCAP") (class "Default")
      (node (ref "C1") (pin "1") (pinfunction "1_1") (pintype "passive"))
      (node (ref "U1") (pin "56") (pinfunction "VCAP_56") (pintype "passive"))
    )
    (net (code "91") (name "/VMK1") (class "Default")
      (node (ref "U1_1") (pin "40") (pinfunction "VMKMODE_40") (pintype "passive"))
    )
    (net (code "92") (name "/VMK2") (class "Default")
      (node (ref "U1_2") (pin "40") (pinfunction "VMKMODE_40") (pintype "passive"))
    )
    (net (code "93") (name "/VMK3") (class "Default")
      (node (ref "U1_3") (pin "40") (pinfunction "VMKMODE_40") (pintype "passive"))
    )
    (net (code "94") (name "/VMK4") (class "Default")
      (node (ref "U1_4") (pin "40") (pinfunction "VMKMODE_40") (pintype "passive"))
    )
    (net (code "95") (name "/VMK5") (class "Default")
      (node (ref "U1_5") (pin "40") (pinfunction "VMKMODE_40") (pintype "passive"))
    )
    (net (code "96") (name "/VMK6") (class "Default")
      (node (ref "U1_6") (pin "40") (pinfunction "VMKMODE_40") (pintype "passive"))
    )
    (net (code "97") (name "/VMK7") (class "Default")
      (node (ref "U1_7") (pin "40") (pinfunction "VMKMODE_40") (pintype "passive"))
    )
    (net (code "98") (name "/VMK8") (class "Default")
      (node (ref "U1_8") (pin "40") (pinfunction "VMKMODE_40") (pintype "passive"))
    )
    (net (code "99") (name "/VMK9") (class "Default")
      (node (ref "U1_9") (pin "40") (pinfunction "VMKMODE_40") (pintype "passive"))
    )
    (net (code "100") (name "/VMK10") (class "Default")
      (node (ref "U1_10") (pin "40") (pinfunction "VMKMODE_40") (pintype "passive"))
    )
    (net (code "101") (name "/VMK11") (class "Default")
      (node (ref "U1_11") (pin "40") (pinfunction "VMKMODE_40") (pintype "passive"))
    )
    (net (code "102") (name "/VMK12") (class "Default")
      (node (ref "U1_12") (pin "40") (pinfunction "VMKMODE_40") (pintype "passive"))
    )
    (net (code "103") (name "/VMK13") (class "Default")
      (node (ref "U1_13") (pin "40") (pinfunction "VMKMODE_40") (pintype "passive"))
    )
    (net (code "104") (name "/VMK14") (class "Default")
      (node (ref "U1_14") (pin "40") (pinfunction "VMKMODE_40") (pintype "passive"))
    )
    (net (code "105") (name "/VMK15") (class "Default")
      (node (ref "U1_15") (pin "40") (pinfunction "VMKMODE_40") (pintype "passive"))
    )
    (net (code "106") (name "/VMK16") (class "Default")
      (node (ref "U1_16") (pin "40") (pinfunction "VMKMODE_40") (pintype "passive"))
    )
    (net (code "107") (name "/XCLK") (class "Default")
      (node (ref "R14") (pin "1") (pinfunction "1_1") (pintype "passive"))
      (node (ref "R8") (pin "1") (pinfunction "1_1") (pintype "passive"))
      (node (ref "U1_1") (pin "12") (pinfunction "REF_CLK_IN_12") (pintype "passive"))
      (node (ref "U1_10") (pin "12") (pinfunction "REF_CLK_IN_12") (pintype "passive"))
      (node (ref "U1_11") (pin "12") (pinfunction "REF_CLK_IN_12") (pintype "passive"))
      (node (ref "U1_12") (pin "12") (pinfunction "REF_CLK_IN_12") (pintype "passive"))
      (node (ref "U1_13") (pin "12") (pinfunction "REF_CLK_IN_12") (pintype "passive"))
      (node (ref "U1_14") (pin "12") (pinfunction "REF_CLK_IN_12") (pintype "passive"))
      (node (ref "U1_15") (pin "12") (pinfunction "REF_CLK_IN_12") (pintype "passive"))
      (node (ref "U1_16") (pin "12") (pinfunction "REF_CLK_IN_12") (pintype "passive"))
      (node (ref "U1_2") (pin "12") (pinfunction "REF_CLK_IN_12") (pintype "passive"))
      (node (ref "U1_3") (pin "12") (pinfunction "REF_CLK_IN_12") (pintype "passive"))
      (node (ref "U1_4") (pin "12") (pinfunction "REF_CLK_IN_12") (pintype "passive"))
      (node (ref "U1_5") (pin "12") (pinfunction "REF_CLK_IN_12") (pintype "passive"))
      (node (ref "U1_6") (pin "12") (pinfunction "REF_CLK_IN_12") (pintype "passive"))
      (node (ref "U1_7") (pin "12") (pinfunction "REF_CLK_IN_12") (pintype "passive"))
      (node (ref "U1_8") (pin "12") (pinfunction "REF_CLK_IN_12") (pintype "passive"))
      (node (ref "U1_9") (pin "12") (pinfunction "REF_CLK_IN_12") (pintype "passive"))
    )
    (net (code "108") (name "/XCLK1") (class "Default")
      (node (ref "R14") (pin "2") (pinfunction "2_2") (pintype "passive"))
      (node (ref "U1") (pin "46") (pinfunction "INT0/DMH/RP64/RD0_46") (pintype "passive"))
      (node (ref "U1") (pin "49") (pinfunction "VCPCON/RP65/RD1_49") (pintype "passive"))
      (node (ref "U1") (pin "52") (pinfunction "PMWR/RP68/RD4_52") (pintype "passive"))
      (node (ref "U1") (pin "53") (pinfunction "PMRD/RP69/RD5_53") (pintype "passive"))
    )
    (net (code "109") (name "/XCLKO1") (class "Default")
      (node (ref "U1_1") (pin "13") (pinfunction "REF_CLK_OUT_13") (pintype "passive"))
    )
    (net (code "110") (name "/XCLKO2") (class "Default")
      (node (ref "U1_2") (pin "13") (pinfunction "REF_CLK_OUT_13") (pintype "passive"))
    )
    (net (code "111") (name "/XCLKO3") (class "Default")
      (node (ref "U1_3") (pin "13") (pinfunction "REF_CLK_OUT_13") (pintype "passive"))
    )
    (net (code "112") (name "/XCLKO4") (class "Default")
      (node (ref "U1_4") (pin "13") (pinfunction "REF_CLK_OUT_13") (pintype "passive"))
    )
    (net (code "113") (name "/XCLKO5") (class "Default")
      (node (ref "U1_5") (pin "13") (pinfunction "REF_CLK_OUT_13") (pintype "passive"))
    )
    (net (code "114") (name "/XCLKO6") (class "Default")
      (node (ref "U1_6") (pin "13") (pinfunction "REF_CLK_OUT_13") (pintype "passive"))
    )
    (net (code "115") (name "/XCLKO7") (class "Default")
      (node (ref "U1_7") (pin "13") (pinfunction "REF_CLK_OUT_13") (pintype "passive"))
    )
    (net (code "116") (name "/XCLKO8") (class "Default")
      (node (ref "U1_8") (pin "13") (pinfunction "REF_CLK_OUT_13") (pintype "passive"))
    )
    (net (code "117") (name "/XCLKO9") (class "Default")
      (node (ref "U1_9") (pin "13") (pinfunction "REF_CLK_OUT_13") (pintype "passive"))
    )
    (net (code "118") (name "/XCLKO10") (class "Default")
      (node (ref "U1_10") (pin "13") (pinfunction "REF_CLK_OUT_13") (pintype "passive"))
    )
    (net (code "119") (name "/XCLKO11") (class "Default")
      (node (ref "U1_11") (pin "13") (pinfunction "REF_CLK_OUT_13") (pintype "passive"))
    )
    (net (code "120") (name "/XCLKO12") (class "Default")
      (node (ref "U1_12") (pin "13") (pinfunction "REF_CLK_OUT_13") (pintype "passive"))
    )
    (net (code "121") (name "/XCLKO13") (class "Default")
      (node (ref "U1_13") (pin "13") (pinfunction "REF_CLK_OUT_13") (pintype "passive"))
    )
    (net (code "122") (name "/XCLKO14") (class "Default")
      (node (ref "U1_14") (pin "13") (pinfunction "REF_CLK_OUT_13") (pintype "passive"))
    )
    (net (code "123") (name "/XCLKO15") (class "Default")
      (node (ref "U1_15") (pin "13") (pinfunction "REF_CLK_OUT_13") (pintype "passive"))
    )
    (net (code "124") (name "/XCLKO16") (class "Default")
      (node (ref "U1_16") (pin "13") (pinfunction "REF_CLK_OUT_13") (pintype "passive"))
    )
    (net (code "125") (name "/YELLOW") (class "Default")
      (node (ref "D3") (pin "2") (pinfunction "A_2") (pintype "passive"))
      (node (ref "U1") (pin "44") (pinfunction "ASCL1/PMCS2/RPI74/RD10_44") (pintype "passive"))
    )
    (net (code "126") (name "GND") (class "Default")
      (node (ref "C1") (pin "2") (pinfunction "2_2") (pintype "passive"))
      (node (ref "C10") (pin "2") (pinfunction "2_2") (pintype "passive"))
      (node (ref "C10_1") (pin "1") (pinfunction "1_1") (pintype "passive"))
      (node (ref "C10_10") (pin "1") (pinfunction "1_1") (pintype "passive"))
      (node (ref "C10_11") (pin "1") (pinfunction "1_1") (pintype "passive"))
      (node (ref "C10_12") (pin "1") (pinfunction "1_1") (pintype "passive"))
      (node (ref "C10_13") (pin "1") (pinfunction "1_1") (pintype "passive"))
      (node (ref "C10_14") (pin "1") (pinfunction "1_1") (pintype "passive"))
      (node (ref "C10_15") (pin "1") (pinfunction "1_1") (pintype "passive"))
      (node (ref "C10_16") (pin "1") (pinfunction "1_1") (pintype "passive"))
      (node (ref "C10_2") (pin "1") (pinfunction "1_1") (pintype "passive"))
      (node (ref "C10_3") (pin "1") (pinfunction "1_1") (pintype "passive"))
      (node (ref "C10_4") (pin "1") (pinfunction "1_1") (pintype "passive"))
      (node (ref "C10_5") (pin "1") (pinfunction "1_1") (pintype "passive"))
      (node (ref "C10_6") (pin "1") (pinfunction "1_1") (pintype "passive"))
      (node (ref "C10_7") (pin "1") (pinfunction "1_1") (pintype "passive"))
      (node (ref "C10_8") (pin "1") (pinfunction "1_1") (pintype "passive"))
      (node (ref "C10_9") (pin "1") (pinfunction "1_1") (pintype "passive"))
      (node (ref "C11") (pin "2") (pinfunction "2_2") (pintype "passive"))
      (node (ref "C11_1") (pin "1") (pinfunction "1_1") (pintype "passive"))
      (node (ref "C11_10") (pin "1") (pinfunction "1_1") (pintype "passive"))
      (node (ref "C11_11") (pin "1") (pinfunction "1_1") (pintype "passive"))
      (node (ref "C11_12") (pin "1") (pinfunction "1_1") (pintype "passive"))
      (node (ref "C11_13") (pin "1") (pinfunction "1_1") (pintype "passive"))
      (node (ref "C11_14") (pin "1") (pinfunction "1_1") (pintype "passive"))
      (node (ref "C11_15") (pin "1") (pinfunction "1_1") (pintype "passive"))
      (node (ref "C11_16") (pin "1") (pinfunction "1_1") (pintype "passive"))
      (node (ref "C11_2") (pin "1") (pinfunction "1_1") (pintype "passive"))
      (node (ref "C11_3") (pin "1") (pinfunction "1_1") (pintype "passive"))
      (node (ref "C11_4") (pin "1") (pinfunction "1_1") (pintype "passive"))
      (node (ref "C11_5") (pin "1") (pinfunction "1_1") (pintype "passive"))
      (node (ref "C11_6") (pin "1") (pinfunction "1_1") (pintype "passive"))
      (node (ref "C11_7") (pin "1") (pinfunction "1_1") (pintype "passive"))
      (node (ref "C11_8") (pin "1") (pinfunction "1_1") (pintype "passive"))
      (node (ref "C11_9") (pin "1") (pinfunction "1_1") (pintype "passive"))
      (node (ref "C12") (pin "2") (pinfunction "2_2") (pintype "passive"))
      (node (ref "C12_1") (pin "1") (pinfunction "1_1") (pintype "passive"))
      (node (ref "C12_10") (pin "1") (pinfunction "1_1") (pintype "passive"))
      (node (ref "C12_11") (pin "1") (pinfunction "1_1") (pintype "passive"))
      (node (ref "C12_12") (pin "1") (pinfunction "1_1") (pintype "passive"))
      (node (ref "C12_13") (pin "1") (pinfunction "1_1") (pintype "passive"))
      (node (ref "C12_14") (pin "1") (pinfunction "1_1") (pintype "passive"))
      (node (ref "C12_15") (pin "1") (pinfunction "1_1") (pintype "passive"))
      (node (ref "C12_16") (pin "1") (pinfunction "1_1") (pintype "passive"))
      (node (ref "C12_2") (pin "1") (pinfunction "1_1") (pintype "passive"))
      (node (ref "C12_3") (pin "1") (pinfunction "1_1") (pintype "passive"))
      (node (ref "C12_4") (pin "1") (pinfunction "1_1") (pintype "passive"))
      (node (ref "C12_5") (pin "1") (pinfunction "1_1") (pintype "passive"))
      (node (ref "C12_6") (pin "1") (pinfunction "1_1") (pintype "passive"))
      (node (ref "C12_7") (pin "1") (pinfunction "1_1") (pintype "passive"))
      (node (ref "C12_8") (pin "1") (pinfunction "1_1") (pintype "passive"))
      (node (ref "C12_9") (pin "1") (pinfunction "1_1") (pintype "passive"))
      (node (ref "C13") (pin "2") (pinfunction "2_2") (pintype "passive"))
      (node (ref "C13_1") (pin "1") (pinfunction "1_1") (pintype "passive"))
      (node (ref "C13_10") (pin "1") (pinfunction "1_1") (pintype "passive"))
      (node (ref "C13_11") (pin "1") (pinfunction "1_1") (pintype "passive"))
      (node (ref "C13_12") (pin "1") (pinfunction "1_1") (pintype "passive"))
      (node (ref "C13_13") (pin "1") (pinfunction "1_1") (pintype "passive"))
      (node (ref "C13_14") (pin "1") (pinfunction "1_1") (pintype "passive"))
      (node (ref "C13_15") (pin "1") (pinfunction "1_1") (pintype "passive"))
      (node (ref "C13_16") (pin "1") (pinfunction "1_1") (pintype "passive"))
      (node (ref "C13_2") (pin "1") (pinfunction "1_1") (pintype "passive"))
      (node (ref "C13_3") (pin "1") (pinfunction "1_1") (pintype "passive"))
      (node (ref "C13_4") (pin "1") (pinfunction "1_1") (pintype "passive"))
      (node (ref "C13_5") (pin "1") (pinfunction "1_1") (pintype "passive"))
      (node (ref "C13_6") (pin "1") (pinfunction "1_1") (pintype "passive"))
      (node (ref "C13_7") (pin "1") (pinfunction "1_1") (pintype "passive"))
      (node (ref "C13_8") (pin "1") (pinfunction "1_1") (pintype "passive"))
      (node (ref "C13_9") (pin "1") (pinfunction "1_1") (pintype "passive"))
      (node (ref "C14") (pin "2") (pinfunction "2_2") (pintype "passive"))
      (node (ref "C14_1") (pin "1") (pinfunction "1_1") (pintype "passive"))
      (node (ref "C14_10") (pin "1") (pinfunction "1_1") (pintype "passive"))
      (node (ref "C14_11") (pin "1") (pinfunction "1_1") (pintype "passive"))
      (node (ref "C14_12") (pin "1") (pinfunction "1_1") (pintype "passive"))
      (node (ref "C14_13") (pin "1") (pinfunction "1_1") (pintype "passive"))
      (node (ref "C14_14") (pin "1") (pinfunction "1_1") (pintype "passive"))
      (node (ref "C14_15") (pin "1") (pinfunction "1_1") (pintype "passive"))
      (node (ref "C14_16") (pin "1") (pinfunction "1_1") (pintype "passive"))
      (node (ref "C14_2") (pin "1") (pinfunction "1_1") (pintype "passive"))
      (node (ref "C14_3") (pin "1") (pinfunction "1_1") (pintype "passive"))
      (node (ref "C14_4") (pin "1") (pinfunction "1_1") (pintype "passive"))
      (node (ref "C14_5") (pin "1") (pinfunction "1_1") (pintype "passive"))
      (node (ref "C14_6") (pin "1") (pinfunction "1_1") (pintype "passive"))
      (node (ref "C14_7") (pin "1") (pinfunction "1_1") (pintype "passive"))
      (node (ref "C14_8") (pin "1") (pinfunction "1_1") (pintype "passive"))
      (node (ref "C14_9") (pin "1") (pinfunction "1_1") (pintype "passive"))
      (node (ref "C15") (pin "2") (pinfunction "2_2") (pintype "passive"))
      (node (ref "C15_1") (pin "1") (pinfunction "1_1") (pintype "passive"))
      (node (ref "C15_10") (pin "1") (pinfunction "1_1") (pintype "passive"))
      (node (ref "C15_11") (pin "1") (pinfunction "1_1") (pintype "passive"))
      (node (ref "C15_12") (pin "1") (pinfunction "1_1") (pintype "passive"))
      (node (ref "C15_13") (pin "1") (pinfunction "1_1") (pintype "passive"))
      (node (ref "C15_14") (pin "1") (pinfunction "1_1") (pintype "passive"))
      (node (ref "C15_15") (pin "1") (pinfunction "1_1") (pintype "passive"))
      (node (ref "C15_16") (pin "1") (pinfunction "1_1") (pintype "passive"))
      (node (ref "C15_2") (pin "1") (pinfunction "1_1") (pintype "passive"))
      (node (ref "C15_3") (pin "1") (pinfunction "1_1") (pintype "passive"))
      (node (ref "C15_4") (pin "1") (pinfunction "1_1") (pintype "passive"))
      (node (ref "C15_5") (pin "1") (pinfunction "1_1") (pintype "passive"))
      (node (ref "C15_6") (pin "1") (pinfunction "1_1") (pintype "passive"))
      (node (ref "C15_7") (pin "1") (pinfunction "1_1") (pintype "passive"))
      (node (ref "C15_8") (pin "1") (pinfunction "1_1") (pintype "passive"))
      (node (ref "C15_9") (pin "1") (pinfunction "1_1") (pintype "passive"))
      (node (ref "C16") (pin "2") (pinfunction "2_2") (pintype "passive"))
      (node (ref "C16_1") (pin "1") (pinfunction "1_1") (pintype "passive"))
      (node (ref "C16_10") (pin "1") (pinfunction "1_1") (pintype "passive"))
      (node (ref "C16_11") (pin "1") (pinfunction "1_1") (pintype "passive"))
      (node (ref "C16_12") (pin "1") (pinfunction "1_1") (pintype "passive"))
      (node (ref "C16_13") (pin "1") (pinfunction "1_1") (pintype "passive"))
      (node (ref "C16_14") (pin "1") (pinfunction "1_1") (pintype "passive"))
      (node (ref "C16_15") (pin "1") (pinfunction "1_1") (pintype "passive"))
      (node (ref "C16_16") (pin "1") (pinfunction "1_1") (pintype "passive"))
      (node (ref "C16_2") (pin "1") (pinfunction "1_1") (pintype "passive"))
      (node (ref "C16_3") (pin "1") (pinfunction "1_1") (pintype "passive"))
      (node (ref "C16_4") (pin "1") (pinfunction "1_1") (pintype "passive"))
      (node (ref "C16_5") (pin "1") (pinfunction "1_1") (pintype "passive"))
      (node (ref "C16_6") (pin "1") (pinfunction "1_1") (pintype "passive"))
      (node (ref "C16_7") (pin "1") (pinfunction "1_1") (pintype "passive"))
      (node (ref "C16_8") (pin "1") (pinfunction "1_1") (pintype "passive"))
      (node (ref "C16_9") (pin "1") (pinfunction "1_1") (pintype "passive"))
      (node (ref "C17") (pin "2") (pinfunction "2_2") (pintype "passive"))
      (node (ref "C1P_1") (pin "1") (pinfunction "1_1") (pintype "passive"))
      (node (ref "C1P_2") (pin "1") (pinfunction "1_1") (pintype "passive"))
      (node (ref "C1P_3") (pin "1") (pinfunction "1_1") (pintype "passive"))
      (node (ref "C1_1") (pin "1") (pinfunction "1_1") (pintype "passive"))
      (node (ref "C1_10") (pin "1") (pinfunction "1_1") (pintype "passive"))
      (node (ref "C1_11") (pin "1") (pinfunction "1_1") (pintype "passive"))
      (node (ref "C1_12") (pin "1") (pinfunction "1_1") (pintype "passive"))
      (node (ref "C1_13") (pin "1") (pinfunction "1_1") (pintype "passive"))
      (node (ref "C1_14") (pin "1") (pinfunction "1_1") (pintype "passive"))
      (node (ref "C1_15") (pin "1") (pinfunction "1_1") (pintype "passive"))
      (node (ref "C1_16") (pin "1") (pinfunction "1_1") (pintype "passive"))
      (node (ref "C1_2") (pin "1") (pinfunction "1_1") (pintype "passive"))
      (node (ref "C1_3") (pin "1") (pinfunction "1_1") (pintype "passive"))
      (node (ref "C1_4") (pin "1") (pinfunction "1_1") (pintype "passive"))
      (node (ref "C1_5") (pin "1") (pinfunction "1_1") (pintype "passive"))
      (node (ref "C1_6") (pin "1") (pinfunction "1_1") (pintype "passive"))
      (node (ref "C1_7") (pin "1") (pinfunction "1_1") (pintype "passive"))
      (node (ref "C1_8") (pin "1") (pinfunction "1_1") (pintype "passive"))
      (node (ref "C1_9") (pin "1") (pinfunction "1_1") (pintype "passive"))
      (node (ref "C2") (pin "2") (pinfunction "2_2") (pintype "passive"))
      (node (ref "C25") (pin "1") (pinfunction "1_1") (pintype "passive"))
      (node (ref "C26") (pin "2") (pinfunction "2_2") (pintype "passive"))
      (node (ref "C2P_1") (pin "2") (pinfunction "2_2") (pintype "passive"))
      (node (ref "C2P_2") (pin "2") (pinfunction "2_2") (pintype "passive"))
      (node (ref "C2P_3") (pin "2") (pinfunction "2_2") (pintype "passive"))
      (node (ref "C2_1") (pin "1") (pinfunction "1_1") (pintype "passive"))
      (node (ref "C2_10") (pin "1") (pinfunction "1_1") (pintype "passive"))
      (node (ref "C2_11") (pin "1") (pinfunction "1_1") (pintype "passive"))
      (node (ref "C2_12") (pin "1") (pinfunction "1_1") (pintype "passive"))
      (node (ref "C2_13") (pin "1") (pinfunction "1_1") (pintype "passive"))
      (node (ref "C2_14") (pin "1") (pinfunction "1_1") (pintype "passive"))
      (node (ref "C2_15") (pin "1") (pinfunction "1_1") (pintype "passive"))
      (node (ref "C2_16") (pin "1") (pinfunction "1_1") (pintype "passive"))
      (node (ref "C2_2") (pin "1") (pinfunction "1_1") (pintype "passive"))
      (node (ref "C2_3") (pin "1") (pinfunction "1_1") (pintype "passive"))
      (node (ref "C2_4") (pin "1") (pinfunction "1_1") (pintype "passive"))
      (node (ref "C2_5") (pin "1") (pinfunction "1_1") (pintype "passive"))
      (node (ref "C2_6") (pin "1") (pinfunction "1_1") (pintype "passive"))
      (node (ref "C2_7") (pin "1") (pinfunction "1_1") (pintype "passive"))
      (node (ref "C2_8") (pin "1") (pinfunction "1_1") (pintype "passive"))
      (node (ref "C2_9") (pin "1") (pinfunction "1_1") (pintype "passive"))
      (node (ref "C3") (pin "2") (pinfunction "2_2") (pintype "passive"))
      (node (ref "C3_1") (pin "1") (pinfunction "1_1") (pintype "passive"))
      (node (ref "C3_10") (pin "1") (pinfunction "1_1") (pintype "passive"))
      (node (ref "C3_11") (pin "1") (pinfunction "1_1") (pintype "passive"))
      (node (ref "C3_12") (pin "1") (pinfunction "1_1") (pintype "passive"))
      (node (ref "C3_13") (pin "1") (pinfunction "1_1") (pintype "passive"))
      (node (ref "C3_14") (pin "1") (pinfunction "1_1") (pintype "passive"))
      (node (ref "C3_15") (pin "1") (pinfunction "1_1") (pintype "passive"))
      (node (ref "C3_16") (pin "1") (pinfunction "1_1") (pintype "passive"))
      (node (ref "C3_2") (pin "1") (pinfunction "1_1") (pintype "passive"))
      (node (ref "C3_3") (pin "1") (pinfunction "1_1") (pintype "passive"))
      (node (ref "C3_4") (pin "1") (pinfunction "1_1") (pintype "passive"))
      (node (ref "C3_5") (pin "1") (pinfunction "1_1") (pintype "passive"))
      (node (ref "C3_6") (pin "1") (pinfunction "1_1") (pintype "passive"))
      (node (ref "C3_7") (pin "1") (pinfunction "1_1") (pintype "passive"))
      (node (ref "C3_8") (pin "1") (pinfunction "1_1") (pintype "passive"))
      (node (ref "C3_9") (pin "1") (pinfunction "1_1") (pintype "passive"))
      (node (ref "C4") (pin "2") (pinfunction "2_2") (pintype "passive"))
      (node (ref "C4P_1") (pin "2") (pinfunction "2_2") (pintype "passive"))
      (node (ref "C4P_2") (pin "2") (pinfunction "2_2") (pintype "passive"))
      (node (ref "C4P_3") (pin "2") (pinfunction "2_2") (pintype "passive"))
      (node (ref "C4_1") (pin "1") (pinfunction "1_1") (pintype "passive"))
      (node (ref "C4_10") (pin "1") (pinfunction "1_1") (pintype "passive"))
      (node (ref "C4_11") (pin "1") (pinfunction "1_1") (pintype "passive"))
      (node (ref "C4_12") (pin "1") (pinfunction "1_1") (pintype "passive"))
      (node (ref "C4_13") (pin "1") (pinfunction "1_1") (pintype "passive"))
      (node (ref "C4_14") (pin "1") (pinfunction "1_1") (pintype "passive"))
      (node (ref "C4_15") (pin "1") (pinfunction "1_1") (pintype "passive"))
      (node (ref "C4_16") (pin "1") (pinfunction "1_1") (pintype "passive"))
      (node (ref "C4_2") (pin "1") (pinfunction "1_1") (pintype "passive"))
      (node (ref "C4_3") (pin "1") (pinfunction "1_1") (pintype "passive"))
      (node (ref "C4_4") (pin "1") (pinfunction "1_1") (pintype "passive"))
      (node (ref "C4_5") (pin "1") (pinfunction "1_1") (pintype "passive"))
      (node (ref "C4_6") (pin "1") (pinfunction "1_1") (pintype "passive"))
      (node (ref "C4_7") (pin "1") (pinfunction "1_1") (pintype "passive"))
      (node (ref "C4_8") (pin "1") (pinfunction "1_1") (pintype "passive"))
      (node (ref "C4_9") (pin "1") (pinfunction "1_1") (pintype "passive"))
      (node (ref "C5") (pin "2") (pinfunction "2_2") (pintype "passive"))
      (node (ref "C5P_1") (pin "2") (pinfunction "2_2") (pintype "passive"))
      (node (ref "C5P_2") (pin "2") (pinfunction "2_2") (pintype "passive"))
      (node (ref "C5P_3") (pin "2") (pinfunction "2_2") (pintype "passive"))
      (node (ref "C5_1") (pin "1") (pinfunction "1_1") (pintype "passive"))
      (node (ref "C5_10") (pin "1") (pinfunction "1_1") (pintype "passive"))
      (node (ref "C5_11") (pin "1") (pinfunction "1_1") (pintype "passive"))
      (node (ref "C5_12") (pin "1") (pinfunction "1_1") (pintype "passive"))
      (node (ref "C5_13") (pin "1") (pinfunction "1_1") (pintype "passive"))
      (node (ref "C5_14") (pin "1") (pinfunction "1_1") (pintype "passive"))
      (node (ref "C5_15") (pin "1") (pinfunction "1_1") (pintype "passive"))
      (node (ref "C5_16") (pin "1") (pinfunction "1_1") (pintype "passive"))
      (node (ref "C5_2") (pin "1") (pinfunction "1_1") (pintype "passive"))
      (node (ref "C5_3") (pin "1") (pinfunction "1_1") (pintype "passive"))
      (node (ref "C5_4") (pin "1") (pinfunction "1_1") (pintype "passive"))
      (node (ref "C5_5") (pin "1") (pinfunction "1_1") (pintype "passive"))
      (node (ref "C5_6") (pin "1") (pinfunction "1_1") (pintype "passive"))
      (node (ref "C5_7") (pin "1") (pinfunction "1_1") (pintype "passive"))
      (node (ref "C5_8") (pin "1") (pinfunction "1_1") (pintype "passive"))
      (node (ref "C5_9") (pin "1") (pinfunction "1_1") (pintype "passive"))
      (node (ref "C6") (pin "2") (pinfunction "2_2") (pintype "passive"))
      (node (ref "C6P_1") (pin "2") (pinfunction "2_2") (pintype "passive"))
      (node (ref "C6P_2") (pin "2") (pinfunction "2_2") (pintype "passive"))
      (node (ref "C6P_3") (pin "2") (pinfunction "2_2") (pintype "passive"))
      (node (ref "C6_1") (pin "1") (pinfunction "1_1") (pintype "passive"))
      (node (ref "C6_10") (pin "1") (pinfunction "1_1") (pintype "passive"))
      (node (ref "C6_11") (pin "1") (pinfunction "1_1") (pintype "passive"))
      (node (ref "C6_12") (pin "1") (pinfunction "1_1") (pintype "passive"))
      (node (ref "C6_13") (pin "1") (pinfunction "1_1") (pintype "passive"))
      (node (ref "C6_14") (pin "1") (pinfunction "1_1") (pintype "passive"))
      (node (ref "C6_15") (pin "1") (pinfunction "1_1") (pintype "passive"))
      (node (ref "C6_16") (pin "1") (pinfunction "1_1") (pintype "passive"))
      (node (ref "C6_2") (pin "1") (pinfunction "1_1") (pintype "passive"))
      (node (ref "C6_3") (pin "1") (pinfunction "1_1") (pintype "passive"))
      (node (ref "C6_4") (pin "1") (pinfunction "1_1") (pintype "passive"))
      (node (ref "C6_5") (pin "1") (pinfunction "1_1") (pintype "passive"))
      (node (ref "C6_6") (pin "1") (pinfunction "1_1") (pintype "passive"))
      (node (ref "C6_7") (pin "1") (pinfunction "1_1") (pintype "passive"))
      (node (ref "C6_8") (pin "1") (pinfunction "1_1") (pintype "passive"))
      (node (ref "C6_9") (pin "1") (pinfunction "1_1") (pintype "passive"))
      (node (ref "C7") (pin "2") (pinfunction "2_2") (pintype "passive"))
      (node (ref "C7P_1") (pin "2") (pinfunction "2_2") (pintype "passive"))
      (node (ref "C7P_2") (pin "2") (pinfunction "2_2") (pintype "passive"))
      (node (ref "C7P_3") (pin "2") (pinfunction "2_2") (pintype "passive"))
      (node (ref "C7_1") (pin "1") (pinfunction "1_1") (pintype "passive"))
      (node (ref "C7_10") (pin "1") (pinfunction "1_1") (pintype "passive"))
      (node (ref "C7_11") (pin "1") (pinfunction "1_1") (pintype "passive"))
      (node (ref "C7_12") (pin "1") (pinfunction "1_1") (pintype "passive"))
      (node (ref "C7_13") (pin "1") (pinfunction "1_1") (pintype "passive"))
      (node (ref "C7_14") (pin "1") (pinfunction "1_1") (pintype "passive"))
      (node (ref "C7_15") (pin "1") (pinfunction "1_1") (pintype "passive"))
      (node (ref "C7_16") (pin "1") (pinfunction "1_1") (pintype "passive"))
      (node (ref "C7_2") (pin "1") (pinfunction "1_1") (pintype "passive"))
      (node (ref "C7_3") (pin "1") (pinfunction "1_1") (pintype "passive"))
      (node (ref "C7_4") (pin "1") (pinfunction "1_1") (pintype "passive"))
      (node (ref "C7_5") (pin "1") (pinfunction "1_1") (pintype "passive"))
      (node (ref "C7_6") (pin "1") (pinfunction "1_1") (pintype "passive"))
      (node (ref "C7_7") (pin "1") (pinfunction "1_1") (pintype "passive"))
      (node (ref "C7_8") (pin "1") (pinfunction "1_1") (pintype "passive"))
      (node (ref "C7_9") (pin "1") (pinfunction "1_1") (pintype "passive"))
      (node (ref "C8") (pin "2") (pinfunction "2_2") (pintype "passive"))
      (node (ref "C8P_1") (pin "2") (pinfunction "2_2") (pintype "passive"))
      (node (ref "C8P_2") (pin "2") (pinfunction "2_2") (pintype "passive"))
      (node (ref "C8P_3") (pin "2") (pinfunction "2_2") (pintype "passive"))
      (node (ref "C8_1") (pin "1") (pinfunction "1_1") (pintype "passive"))
      (node (ref "C8_10") (pin "1") (pinfunction "1_1") (pintype "passive"))
      (node (ref "C8_11") (pin "1") (pinfunction "1_1") (pintype "passive"))
      (node (ref "C8_12") (pin "1") (pinfunction "1_1") (pintype "passive"))
      (node (ref "C8_13") (pin "1") (pinfunction "1_1") (pintype "passive"))
      (node (ref "C8_14") (pin "1") (pinfunction "1_1") (pintype "passive"))
      (node (ref "C8_15") (pin "1") (pinfunction "1_1") (pintype "passive"))
      (node (ref "C8_16") (pin "1") (pinfunction "1_1") (pintype "passive"))
      (node (ref "C8_2") (pin "1") (pinfunction "1_1") (pintype "passive"))
      (node (ref "C8_3") (pin "1") (pinfunction "1_1") (pintype "passive"))
      (node (ref "C8_4") (pin "1") (pinfunction "1_1") (pintype "passive"))
      (node (ref "C8_5") (pin "1") (pinfunction "1_1") (pintype "passive"))
      (node (ref "C8_6") (pin "1") (pinfunction "1_1") (pintype "passive"))
      (node (ref "C8_7") (pin "1") (pinfunction "1_1") (pintype "passive"))
      (node (ref "C8_8") (pin "1") (pinfunction "1_1") (pintype "passive"))
      (node (ref "C8_9") (pin "1") (pinfunction "1_1") (pintype "passive"))
      (node (ref "C9") (pin "2") (pinfunction "2_2") (pintype "passive"))
      (node (ref "C9_1") (pin "1") (pinfunction "1_1") (pintype "passive"))
      (node (ref "C9_10") (pin "1") (pinfunction "1_1") (pintype "passive"))
      (node (ref "C9_11") (pin "1") (pinfunction "1_1") (pintype "passive"))
      (node (ref "C9_12") (pin "1") (pinfunction "1_1") (pintype "passive"))
      (node (ref "C9_13") (pin "1") (pinfunction "1_1") (pintype "passive"))
      (node (ref "C9_14") (pin "1") (pinfunction "1_1") (pintype "passive"))
      (node (ref "C9_15") (pin "1") (pinfunction "1_1") (pintype "passive"))
      (node (ref "C9_16") (pin "1") (pinfunction "1_1") (pintype "passive"))
      (node (ref "C9_2") (pin "1") (pinfunction "1_1") (pintype "passive"))
      (node (ref "C9_3") (pin "1") (pinfunction "1_1") (pintype "passive"))
      (node (ref "C9_4") (pin "1") (pinfunction "1_1") (pintype "passive"))
      (node (ref "C9_5") (pin "1") (pinfunction "1_1") (pintype "passive"))
      (node (ref "C9_6") (pin "1") (pinfunction "1_1") (pintype "passive"))
      (node (ref "C9_7") (pin "1") (pinfunction "1_1") (pintype "passive"))
      (node (ref "C9_8") (pin "1") (pinfunction "1_1") (pintype "passive"))
      (node (ref "C9_9") (pin "1") (pinfunction "1_1") (pintype "passive"))
      (node (ref "C_220_1") (pin "2") (pinfunction "2_2") (pintype "passive"))
      (node (ref "C_220_10") (pin "2") (pinfunction "2_2") (pintype "passive"))
      (node (ref "C_220_11") (pin "2") (pinfunction "2_2") (pintype "passive"))
      (node (ref "C_220_12") (pin "2") (pinfunction "2_2") (pintype "passive"))
      (node (ref "C_220_13") (pin "2") (pinfunction "2_2") (pintype "passive"))
      (node (ref "C_220_14") (pin "2") (pinfunction "2_2") (pintype "passive"))
      (node (ref "C_220_15") (pin "2") (pinfunction "2_2") (pintype "passive"))
      (node (ref "C_220_16") (pin "2") (pinfunction "2_2") (pintype "passive"))
      (node (ref "C_220_17") (pin "2") (pinfunction "2_2") (pintype "passive"))
      (node (ref "C_220_18") (pin "2") (pinfunction "2_2") (pintype "passive"))
      (node (ref "C_220_19") (pin "2") (pinfunction "2_2") (pintype "passive"))
      (node (ref "C_220_2") (pin "2") (pinfunction "2_2") (pintype "passive"))
      (node (ref "C_220_20") (pin "2") (pinfunction "2_2") (pintype "passive"))
      (node (ref "C_220_21") (pin "2") (pinfunction "2_2") (pintype "passive"))
      (node (ref "C_220_22") (pin "2") (pinfunction "2_2") (pintype "passive"))
      (node (ref "C_220_23") (pin "2") (pinfunction "2_2") (pintype "passive"))
      (node (ref "C_220_24") (pin "2") (pinfunction "2_2") (pintype "passive"))
      (node (ref "C_220_25") (pin "2") (pinfunction "2_2") (pintype "passive"))
      (node (ref "C_220_26") (pin "2") (pinfunction "2_2") (pintype "passive"))
      (node (ref "C_220_27") (pin "2") (pinfunction "2_2") (pintype "passive"))
      (node (ref "C_220_28") (pin "2") (pinfunction "2_2") (pintype "passive"))
      (node (ref "C_220_29") (pin "2") (pinfunction "2_2") (pintype "passive"))
      (node (ref "C_220_3") (pin "2") (pinfunction "2_2") (pintype "passive"))
      (node (ref "C_220_30") (pin "2") (pinfunction "2_2") (pintype "passive"))
      (node (ref "C_220_31") (pin "2") (pinfunction "2_2") (pintype "passive"))
      (node (ref "C_220_32") (pin "2") (pinfunction "2_2") (pintype "passive"))
      (node (ref "C_220_33") (pin "2") (pinfunction "2_2") (pintype "passive"))
      (node (ref "C_220_34") (pin "2") (pinfunction "2_2") (pintype "passive"))
      (node (ref "C_220_35") (pin "2") (pinfunction "2_2") (pintype "passive"))
      (node (ref "C_220_36") (pin "2") (pinfunction "2_2") (pintype "passive"))
      (node (ref "C_220_37") (pin "2") (pinfunction "2_2") (pintype "passive"))
      (node (ref "C_220_38") (pin "2") (pinfunction "2_2") (pintype "passive"))
      (node (ref "C_220_39") (pin "2") (pinfunction "2_2") (pintype "passive"))
      (node (ref "C_220_4") (pin "2") (pinfunction "2_2") (pintype "passive"))
      (node (ref "C_220_40") (pin "2") (pinfunction "2_2") (pintype "passive"))
      (node (ref "C_220_41") (pin "2") (pinfunction "2_2") (pintype "passive"))
      (node (ref "C_220_42") (pin "2") (pinfunction "2_2") (pintype "passive"))
      (node (ref "C_220_43") (pin "2") (pinfunction "2_2") (pintype "passive"))
      (node (ref "C_220_44") (pin "2") (pinfunction "2_2") (pintype "passive"))
      (node (ref "C_220_45") (pin "2") (pinfunction "2_2") (pintype "passive"))
      (node (ref "C_220_46") (pin "2") (pinfunction "2_2") (pintype "passive"))
      (node (ref "C_220_47") (pin "2") (pinfunction "2_2") (pintype "passive"))
      (node (ref "C_220_48") (pin "2") (pinfunction "2_2") (pintype "passive"))
      (node (ref "C_220_49") (pin "2") (pinfunction "2_2") (pintype "passive"))
      (node (ref "C_220_5") (pin "2") (pinfunction "2_2") (pintype "passive"))
      (node (ref "C_220_50") (pin "2") (pinfunction "2_2") (pintype "passive"))
      (node (ref "C_220_51") (pin "2") (pinfunction "2_2") (pintype "passive"))
      (node (ref "C_220_52") (pin "2") (pinfunction "2_2") (pintype "passive"))
      (node (ref "C_220_53") (pin "2") (pinfunction "2_2") (pintype "passive"))
      (node (ref "C_220_54") (pin "2") (pinfunction "2_2") (pintype "passive"))
      (node (ref "C_220_55") (pin "2") (pinfunction "2_2") (pintype "passive"))
      (node (ref "C_220_56") (pin "2") (pinfunction "2_2") (pintype "passive"))
      (node (ref "C_220_57") (pin "2") (pinfunction "2_2") (pintype "passive"))
      (node (ref "C_220_58") (pin "2") (pinfunction "2_2") (pintype "passive"))
      (node (ref "C_220_59") (pin "2") (pinfunction "2_2") (pintype "passive"))
      (node (ref "C_220_6") (pin "2") (pinfunction "2_2") (pintype "passive"))
      (node (ref "C_220_60") (pin "2") (pinfunction "2_2") (pintype "passive"))
      (node (ref "C_220_61") (pin "2") (pinfunction "2_2") (pintype "passive"))
      (node (ref "C_220_62") (pin "2") (pinfunction "2_2") (pintype "passive"))
      (node (ref "C_220_63") (pin "2") (pinfunction "2_2") (pintype "passive"))
      (node (ref "C_220_64") (pin "2") (pinfunction "2_2") (pintype "passive"))
      (node (ref "C_220_65") (pin "2") (pinfunction "2_2") (pintype "passive"))
      (node (ref "C_220_66") (pin "2") (pinfunction "2_2") (pintype "passive"))
      (node (ref "C_220_67") (pin "2") (pinfunction "2_2") (pintype "passive"))
      (node (ref "C_220_68") (pin "2") (pinfunction "2_2") (pintype "passive"))
      (node (ref "C_220_69") (pin "2") (pinfunction "2_2") (pintype "passive"))
      (node (ref "C_220_7") (pin "2") (pinfunction "2_2") (pintype "passive"))
      (node (ref "C_220_70") (pin "2") (pinfunction "2_2") (pintype "passive"))
      (node (ref "C_220_71") (pin "2") (pinfunction "2_2") (pintype "passive"))
      (node (ref "C_220_73") (pin "2") (pinfunction "2_2") (pintype "passive"))
      (node (ref "C_220_8") (pin "2") (pinfunction "2_2") (pintype "passive"))
      (node (ref "C_220_9") (pin "2") (pinfunction "2_2") (pintype "passive"))
      (node (ref "D1") (pin "1") (pinfunction "C_1") (pintype "passive"))
      (node (ref "D10") (pin "2") (pinfunction "A_2") (pintype "passive"))
      (node (ref "D2") (pin "1") (pinfunction "C_1") (pintype "passive"))
      (node (ref "D3") (pin "1") (pinfunction "C_1") (pintype "passive"))
      (node (ref "D4") (pin "1") (pinfunction "C_1") (pintype "passive"))
      (node (ref "D5") (pin "2") (pinfunction "AAAA_2") (pintype "passive"))
      (node (ref "D5") (pin "5") (pinfunction "C4_5") (pintype "passive"))
      (node (ref "J1") (pin "3") (pinfunction "3_3") (pintype "passive"))
      (node (ref "J2") (pin "5") (pinfunction "5_5") (pintype "passive"))
      (node (ref "J2") (pin "6") (pinfunction "6_6") (pintype "passive"))
      (node (ref "J2") (pin "7") (pinfunction "7_7") (pintype "passive"))
      (node (ref "J2") (pin "8") (pinfunction "8_8") (pintype "passive"))
      (node (ref "J2") (pin "9") (pinfunction "9_9") (pintype "passive"))
      (node (ref "J3") (pin "2") (pinfunction "2_2") (pintype "passive"))
      (node (ref "J4") (pin "1") (pinfunction "1_1") (pintype "passive"))
      (node (ref "J4") (pin "3") (pinfunction "3_3") (pintype "passive"))
      (node (ref "J4") (pin "5") (pinfunction "5_5") (pintype "passive"))
      (node (ref "Q1") (pin "2") (pinfunction "E_2") (pintype "passive"))
      (node (ref "Q2P_1") (pin "1") (pinfunction "S_1") (pintype "passive"))
      (node (ref "Q2P_1") (pin "2") (pinfunction "S_2") (pintype "passive"))
      (node (ref "Q2P_1") (pin "3") (pinfunction "S_3") (pintype "passive"))
      (node (ref "Q2P_2") (pin "1") (pinfunction "S_1") (pintype "passive"))
      (node (ref "Q2P_2") (pin "2") (pinfunction "S_2") (pintype "passive"))
      (node (ref "Q2P_2") (pin "3") (pinfunction "S_3") (pintype "passive"))
      (node (ref "Q2P_3") (pin "1") (pinfunction "S_1") (pintype "passive"))
      (node (ref "Q2P_3") (pin "2") (pinfunction "S_2") (pintype "passive"))
      (node (ref "Q2P_3") (pin "3") (pinfunction "S_3") (pintype "passive"))
      (node (ref "Q3P_1") (pin "1") (pinfunction "S_1") (pintype "passive"))
      (node (ref "Q3P_1") (pin "2") (pinfunction "S_2") (pintype "passive"))
      (node (ref "Q3P_1") (pin "3") (pinfunction "S_3") (pintype "passive"))
      (node (ref "Q3P_2") (pin "1") (pinfunction "S_1") (pintype "passive"))
      (node (ref "Q3P_2") (pin "2") (pinfunction "S_2") (pintype "passive"))
      (node (ref "Q3P_2") (pin "3") (pinfunction "S_3") (pintype "passive"))
      (node (ref "Q3P_3") (pin "1") (pinfunction "S_1") (pintype "passive"))
      (node (ref "Q3P_3") (pin "2") (pinfunction "S_2") (pintype "passive"))
      (node (ref "Q3P_3") (pin "3") (pinfunction "S_3") (pintype "passive"))
      (node (ref "R10") (pin "2") (pinfunction "2_2") (pintype "passive"))
      (node (ref "R11") (pin "2") (pinfunction "2_2") (pintype "passive"))
      (node (ref "R12") (pin "1") (pinfunction "1_1") (pintype "passive"))
      (node (ref "R13") (pin "1") (pinfunction "1_1") (pintype "passive"))
      (node (ref "R16") (pin "1") (pinfunction "1_1") (pintype "passive"))
      (node (ref "R19") (pin "2") (pinfunction "2_2") (pintype "passive"))
      (node (ref "R31") (pin "1") (pinfunction "1_1") (pintype "passive"))
      (node (ref "R5") (pin "1") (pinfunction "1_1") (pintype "passive"))
      (node (ref "R7") (pin "1") (pinfunction "1_1") (pintype "passive"))
      (node (ref "R8") (pin "2") (pinfunction "2_2") (pintype "passive"))
      (node (ref "R9") (pin "2") (pinfunction "2_2") (pintype "passive"))
      (node (ref "U1") (pin "20") (pinfunction "AVSS_20") (pintype "passive"))
      (node (ref "U1") (pin "25") (pinfunction "VSS_25") (pintype "passive"))
      (node (ref "U1") (pin "41") (pinfunction "VSS_41") (pintype "passive"))
      (node (ref "U1") (pin "9") (pinfunction "VSS_9") (pintype "passive"))
      (node (ref "U1P_1") (pin "4") (pinfunction "GND_4") (pintype "passive"))
      (node (ref "U1P_1") (pin "9") (pinfunction "EP_9") (pintype "passive"))
      (node (ref "U1P_2") (pin "4") (pinfunction "GND_4") (pintype "passive"))
      (node (ref "U1P_2") (pin "9") (pinfunction "EP_9") (pintype "passive"))
      (node (ref "U1P_3") (pin "4") (pinfunction "GND_4") (pintype "passive"))
      (node (ref "U1P_3") (pin "9") (pinfunction "EP_9") (pintype "passive"))
      (node (ref "U1_1") (pin "69") (pinfunction "VSS_EP_69") (pintype "passive"))
      (node (ref "U1_10") (pin "69") (pinfunction "VSS_EP_69") (pintype "passive"))
      (node (ref "U1_11") (pin "69") (pinfunction "VSS_EP_69") (pintype "passive"))
      (node (ref "U1_12") (pin "69") (pinfunction "VSS_EP_69") (pintype "passive"))
      (node (ref "U1_13") (pin "69") (pinfunction "VSS_EP_69") (pintype "passive"))
      (node (ref "U1_14") (pin "69") (pinfunction "VSS_EP_69") (pintype "passive"))
      (node (ref "U1_15") (pin "69") (pinfunction "VSS_EP_69") (pintype "passive"))
      (node (ref "U1_16") (pin "69") (pinfunction "VSS_EP_69") (pintype "passive"))
      (node (ref "U1_2") (pin "69") (pinfunction "VSS_EP_69") (pintype "passive"))
      (node (ref "U1_3") (pin "69") (pinfunction "VSS_EP_69") (pintype "passive"))
      (node (ref "U1_4") (pin "69") (pinfunction "VSS_EP_69") (pintype "passive"))
      (node (ref "U1_5") (pin "69") (pinfunction "VSS_EP_69") (pintype "passive"))
      (node (ref "U1_6") (pin "69") (pinfunction "VSS_EP_69") (pintype "passive"))
      (node (ref "U1_7") (pin "69") (pinfunction "VSS_EP_69") (pintype "passive"))
      (node (ref "U1_8") (pin "69") (pinfunction "VSS_EP_69") (pintype "passive"))
      (node (ref "U1_9") (pin "69") (pinfunction "VSS_EP_69") (pintype "passive"))
      (node (ref "U2") (pin "2") (pinfunction "GND_2") (pintype "passive"))
      (node (ref "U2") (pin "3") (pinfunction "GND_3") (pintype "passive"))
      (node (ref "U2") (pin "4") (pinfunction "N.C._4") (pintype "passive"))
      (node (ref "U2") (pin "5") (pinfunction "N.C._5") (pintype "passive"))
      (node (ref "U2") (pin "6") (pinfunction "GND_6") (pintype "passive"))
      (node (ref "U2") (pin "7") (pinfunction "GND_7") (pintype "passive"))
      (node (ref "U3") (pin "2") (pinfunction "GND_2") (pintype "passive"))
      (node (ref "U4") (pin "2") (pinfunction "GND_2") (pintype "passive"))
      (node (ref "U5") (pin "2") (pinfunction "GND_2") (pintype "passive"))
      (node (ref "U6") (pin "6") (pinfunction "GND_6") (pintype "passive"))
      (node (ref "U6") (pin "7") (pinfunction "GND_7") (pintype "passive"))
      (node (ref "U7") (pin "6") (pinfunction "GND_6") (pintype "passive"))
      (node (ref "U7") (pin "7") (pinfunction "GND_7") (pintype "passive"))
    )
    (net (code "127") (name "unconnected-(J2-Pad4)") (class "Default")
      (node (ref "J2") (pin "4") (pinfunction "4_4") (pintype "passive"))
    )
    (net (code "128") (name "unconnected-(U6-GND-Pad2)") (class "Default")
      (node (ref "U6") (pin "2") (pinfunction "GND_2") (pintype "passive"))
    )
    (net (code "129") (name "unconnected-(U6-GND-Pad3)") (class "Default")
      (node (ref "U6") (pin "3") (pinfunction "GND_3") (pintype "passive"))
    )
    (net (code "130") (name "unconnected-(U6-N.C.-Pad4)") (class "Default")
      (node (ref "U6") (pin "4") (pinfunction "N.C._4") (pintype "passive"))
    )
    (net (code "131") (name "unconnected-(U7-GND-Pad2)") (class "Default")
      (node (ref "U7") (pin "2") (pinfunction "GND_2") (pintype "passive"))
    )
    (net (code "132") (name "unconnected-(U7-GND-Pad3)") (class "Default")
      (node (ref "U7") (pin "3") (pinfunction "GND_3") (pintype "passive"))
    )
    (net (code "133") (name "unconnected-(U7-N.C.-Pad4)") (class "Default")
      (node (ref "U7") (pin "4") (pinfunction "N.C._4") (pintype "passive"))
    )
  )
)
